# interfacez_r2_2.net
KiCad netlist of a schematic drawn in EAGLE
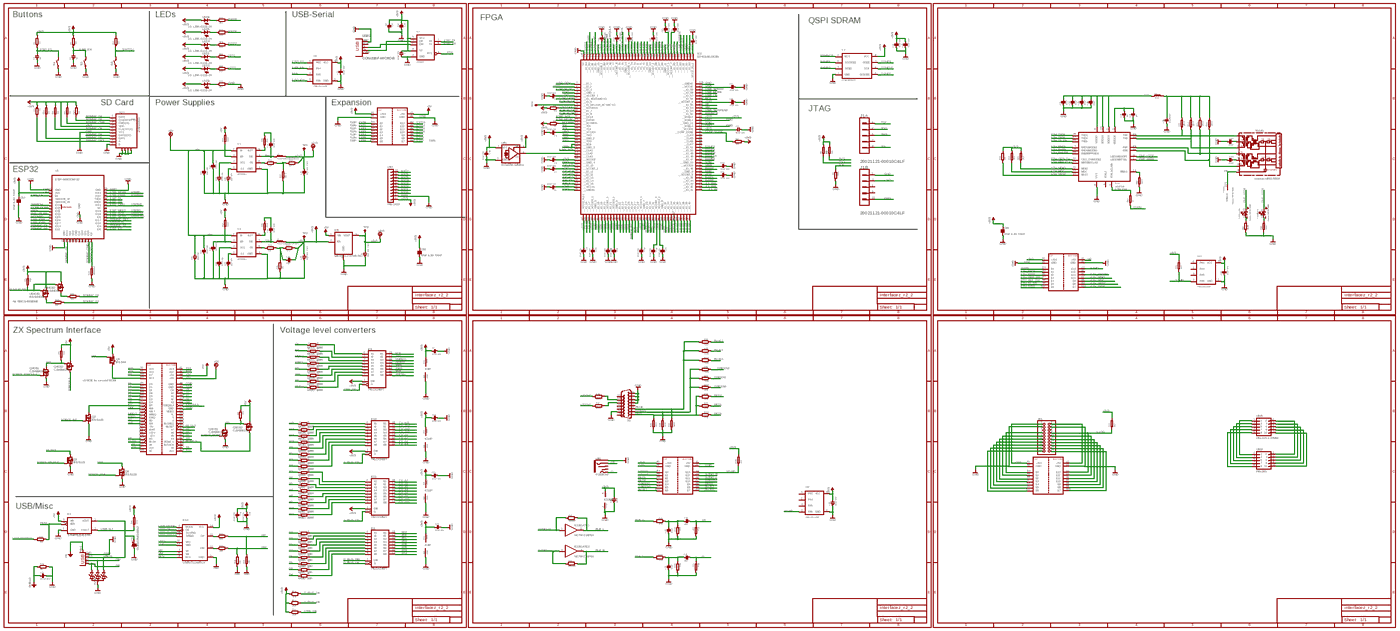
[diagram p0: schematic, sheet 1, overview]
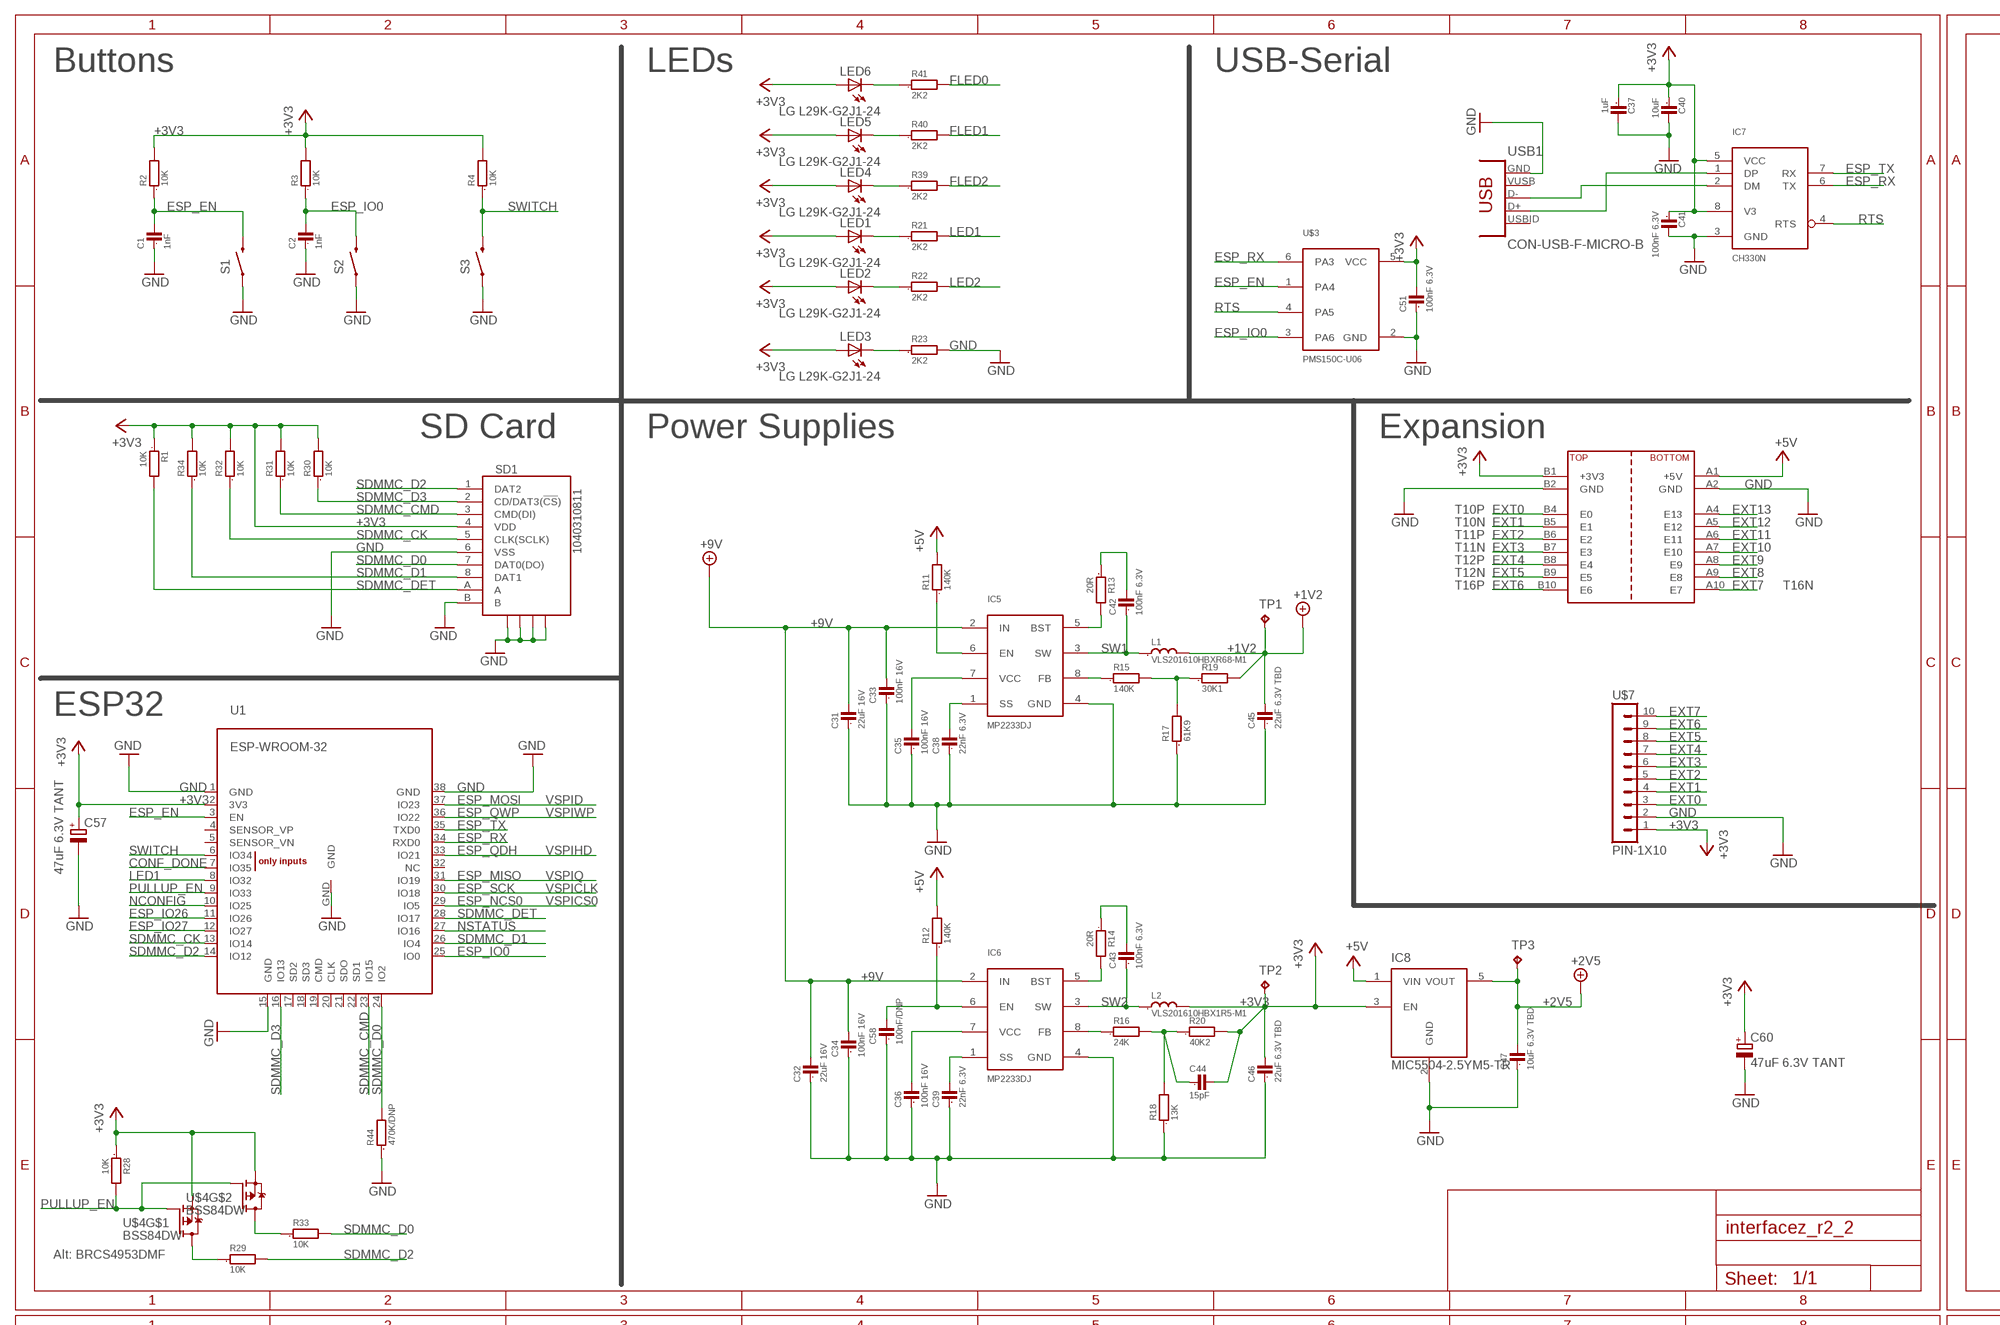
[diagram p1: schematic, sheet 1, part 1 of 8]
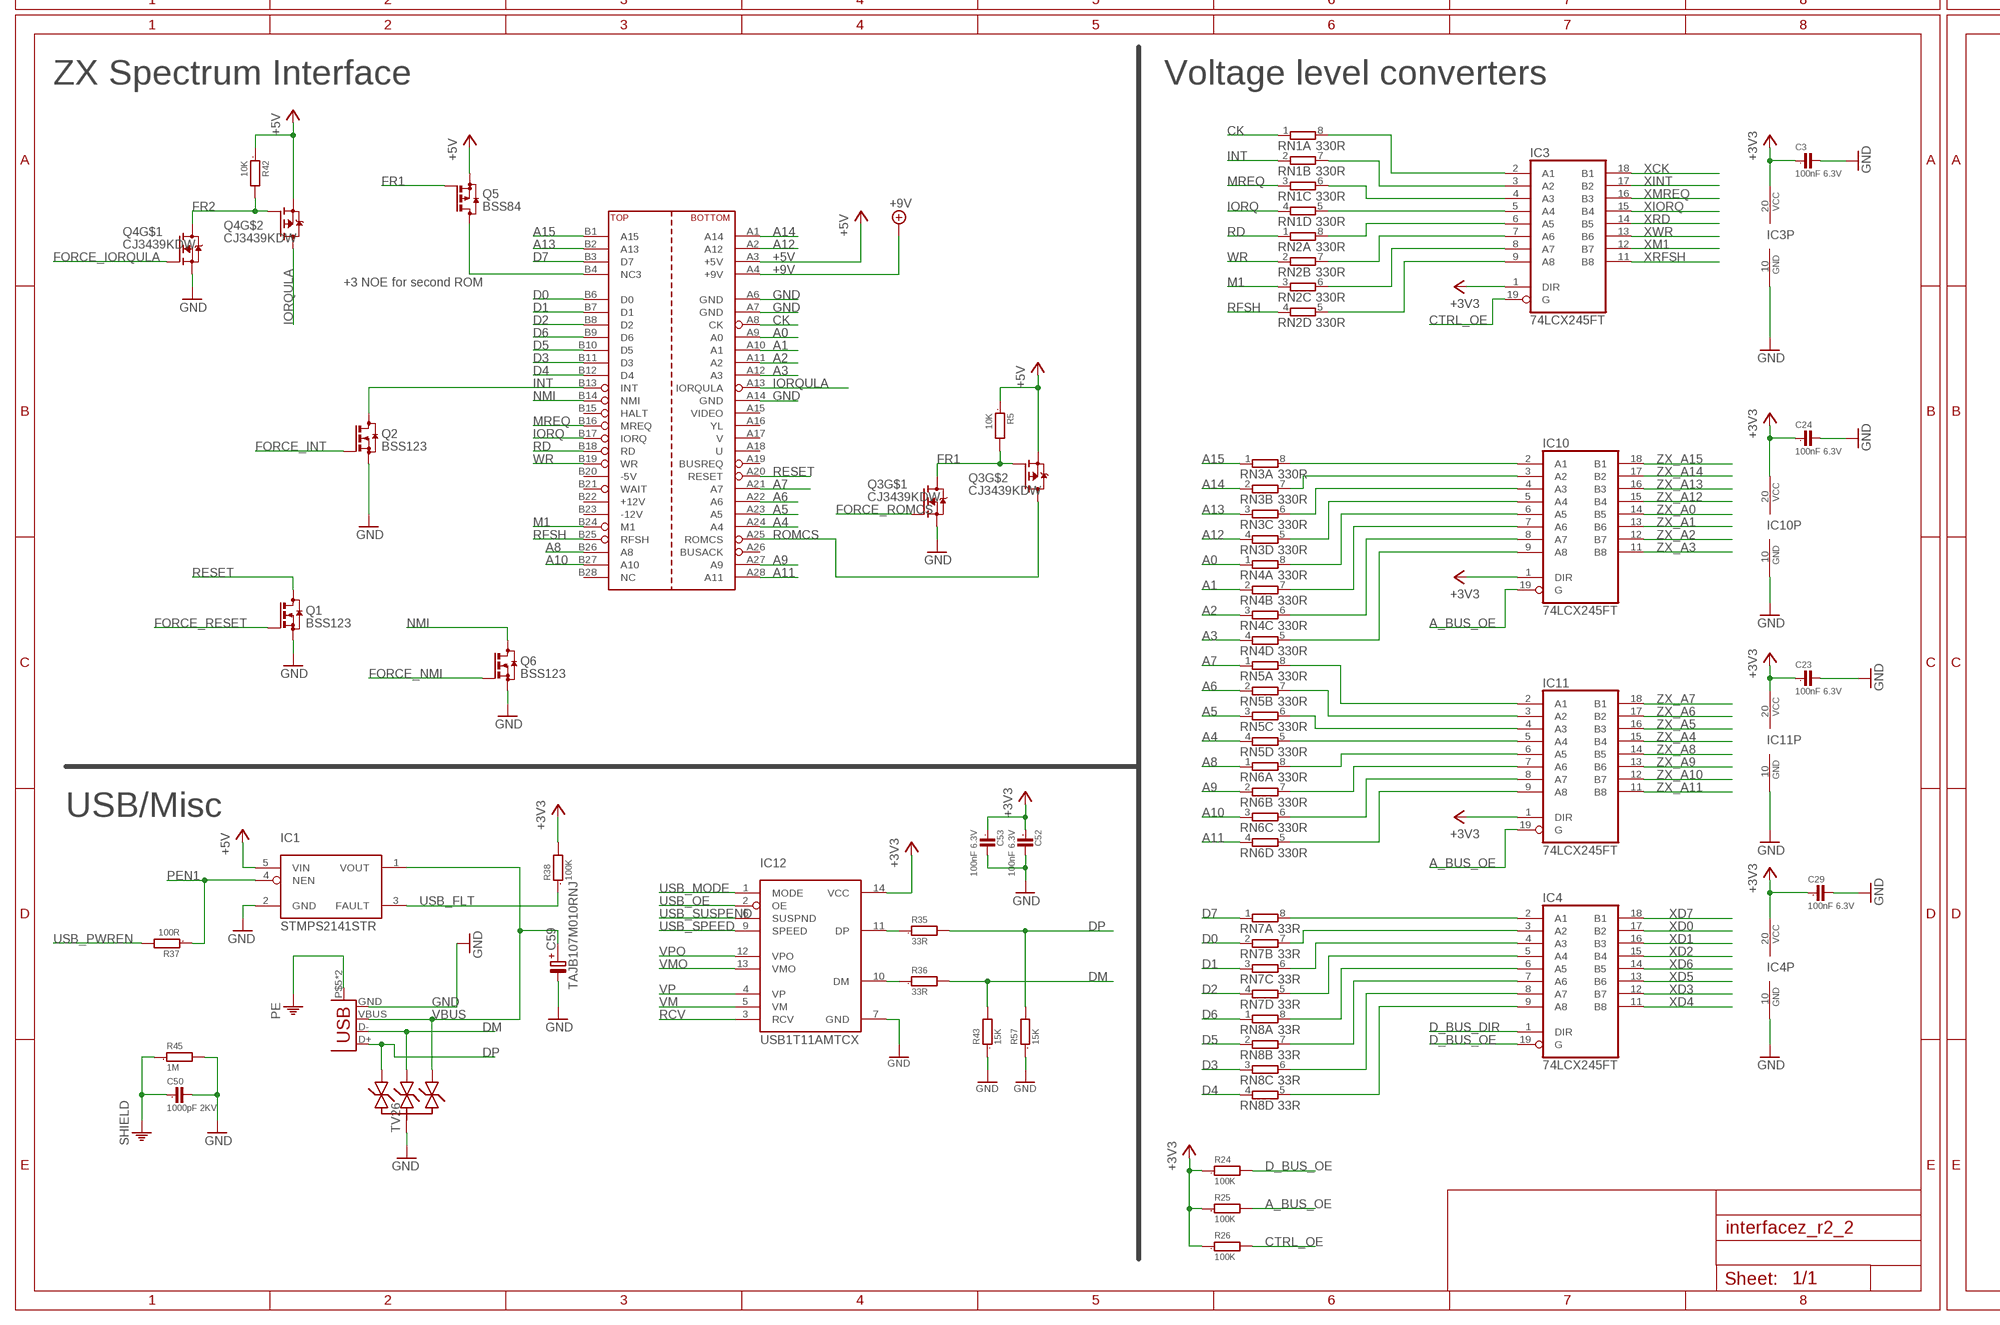
[diagram p2: schematic, sheet 1, part 2 of 8]
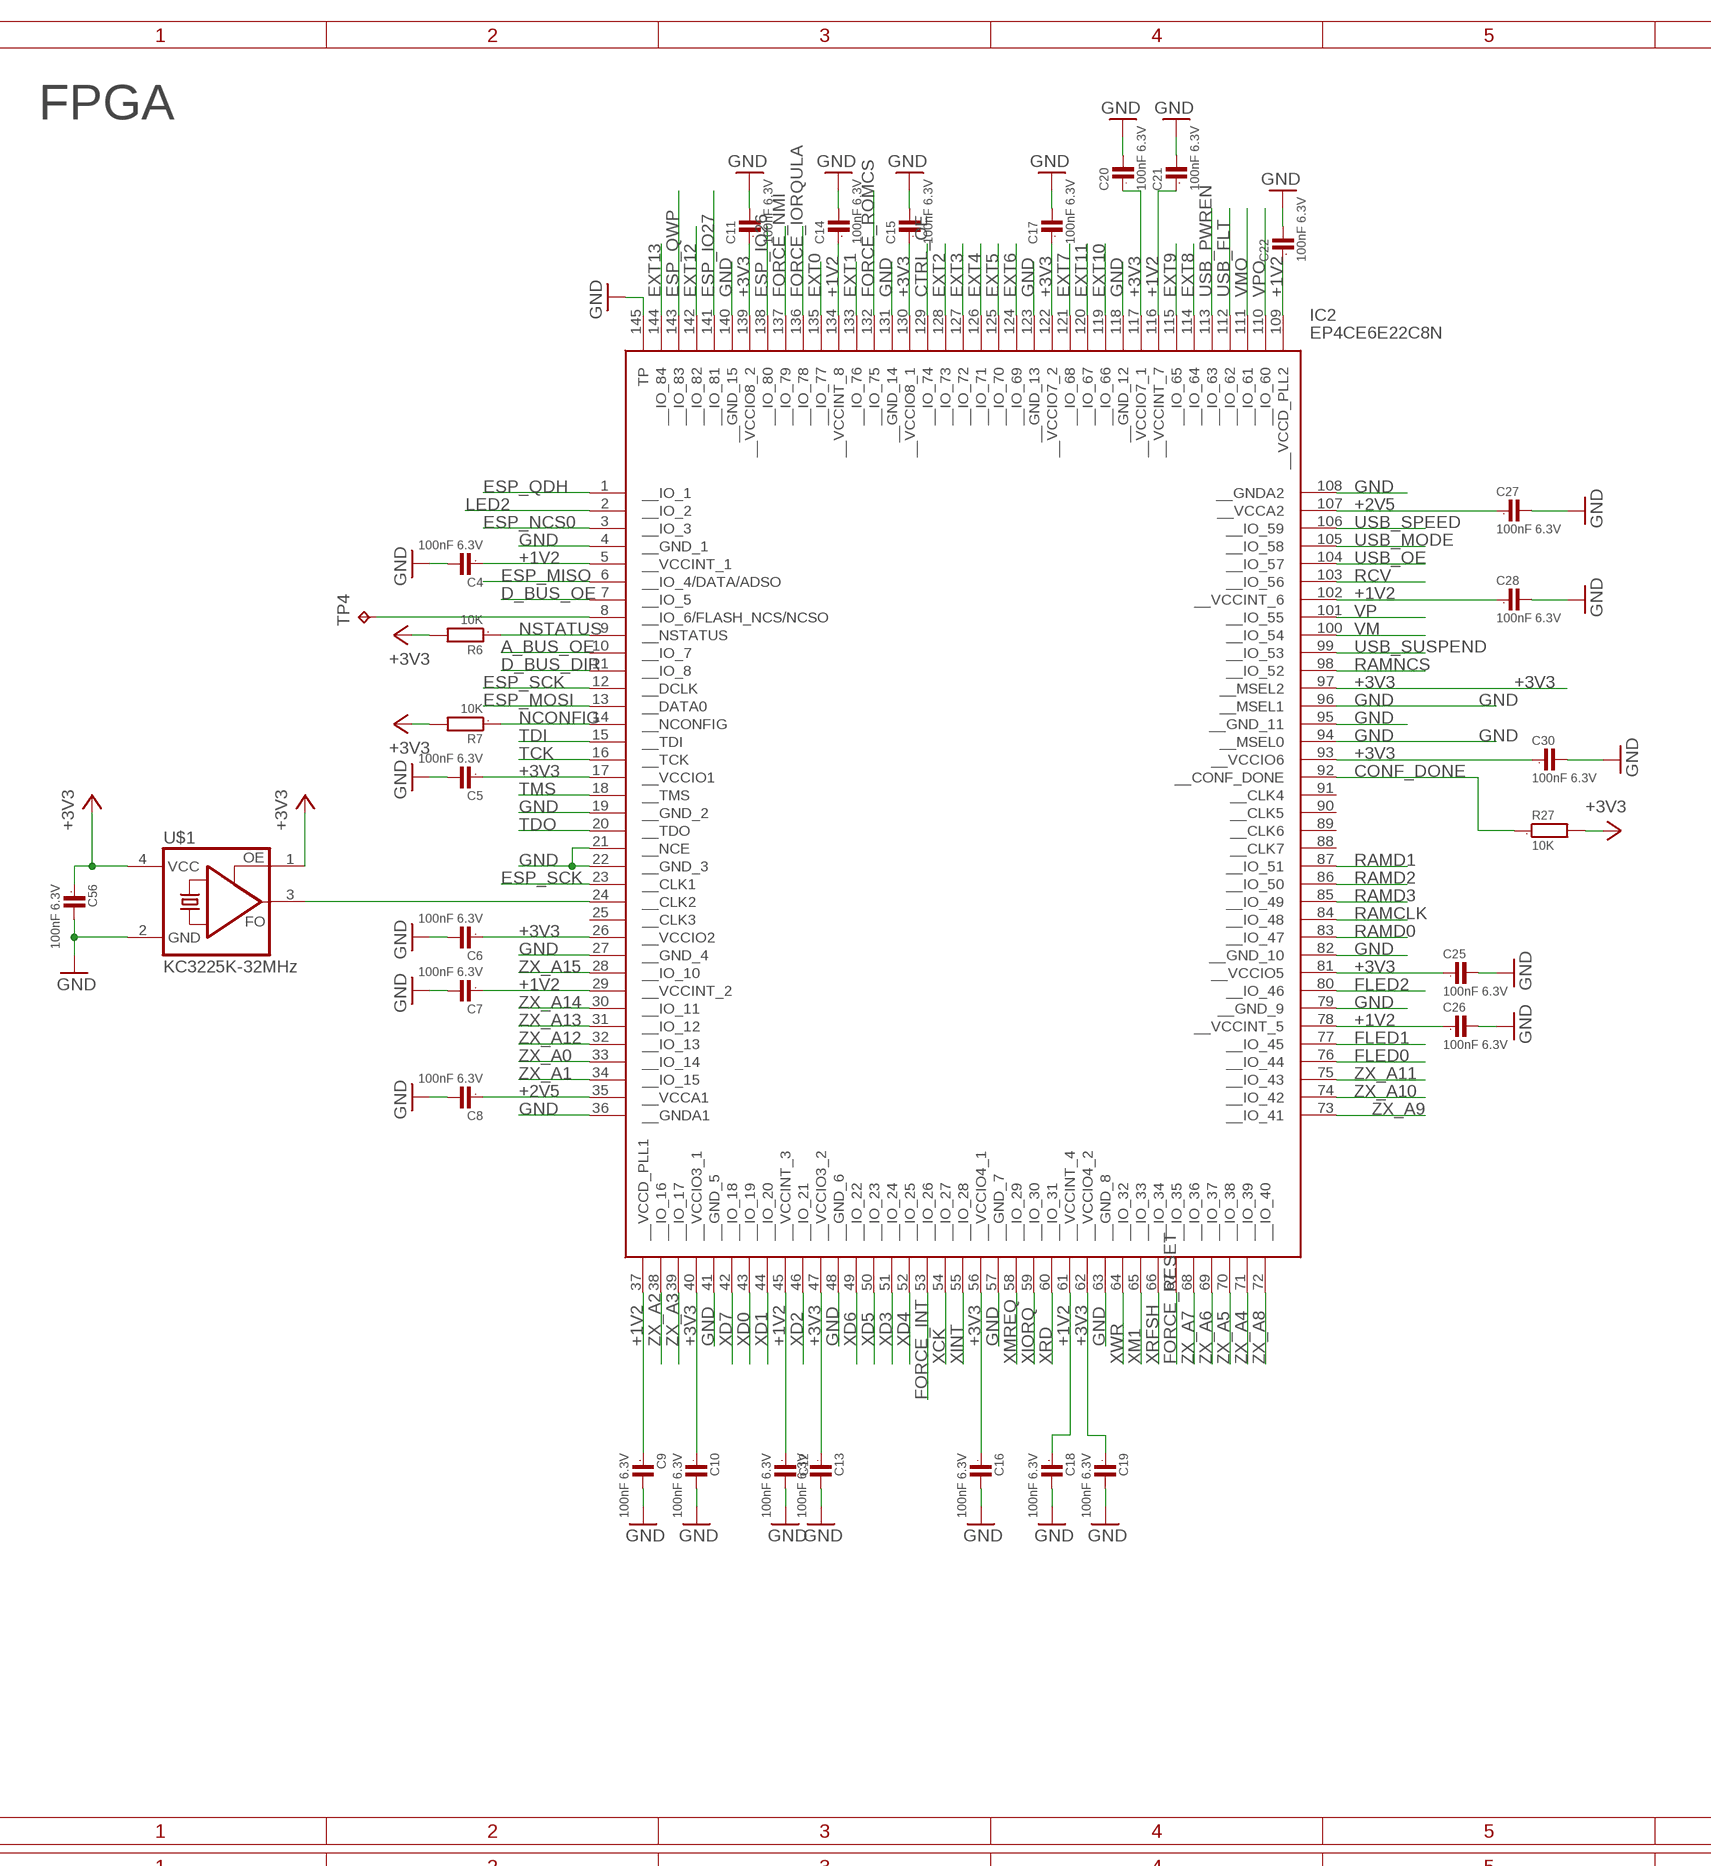
[diagram p3: schematic, sheet 1, part 3 of 8]
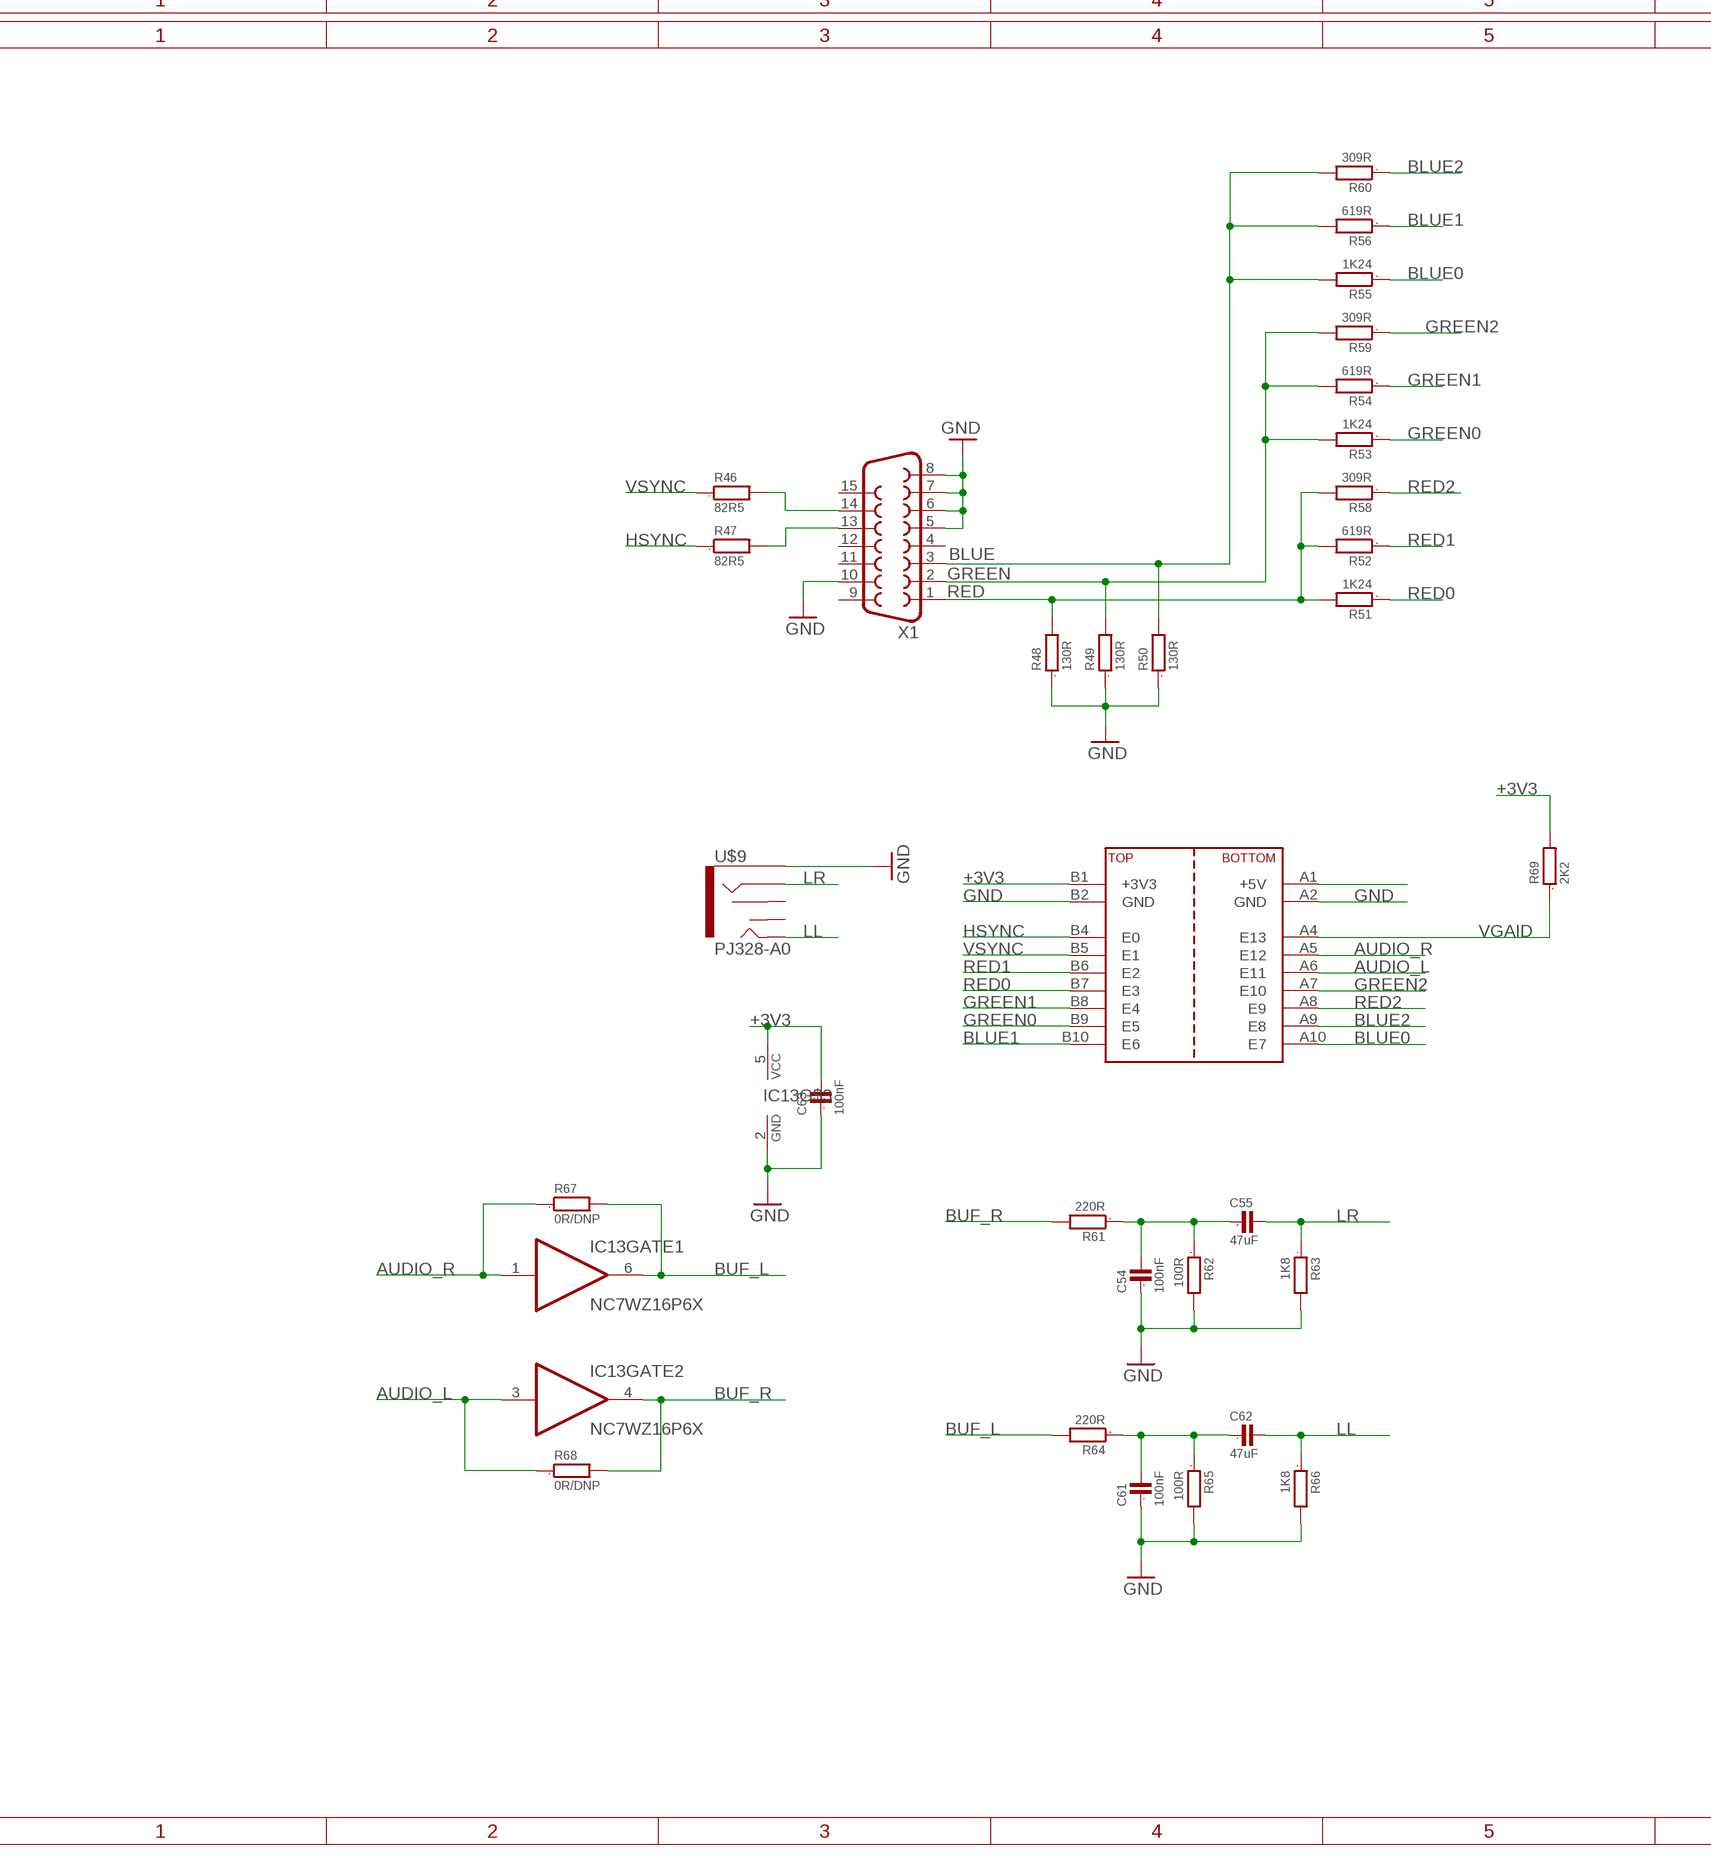
[diagram p4: schematic, sheet 1, part 4 of 8]
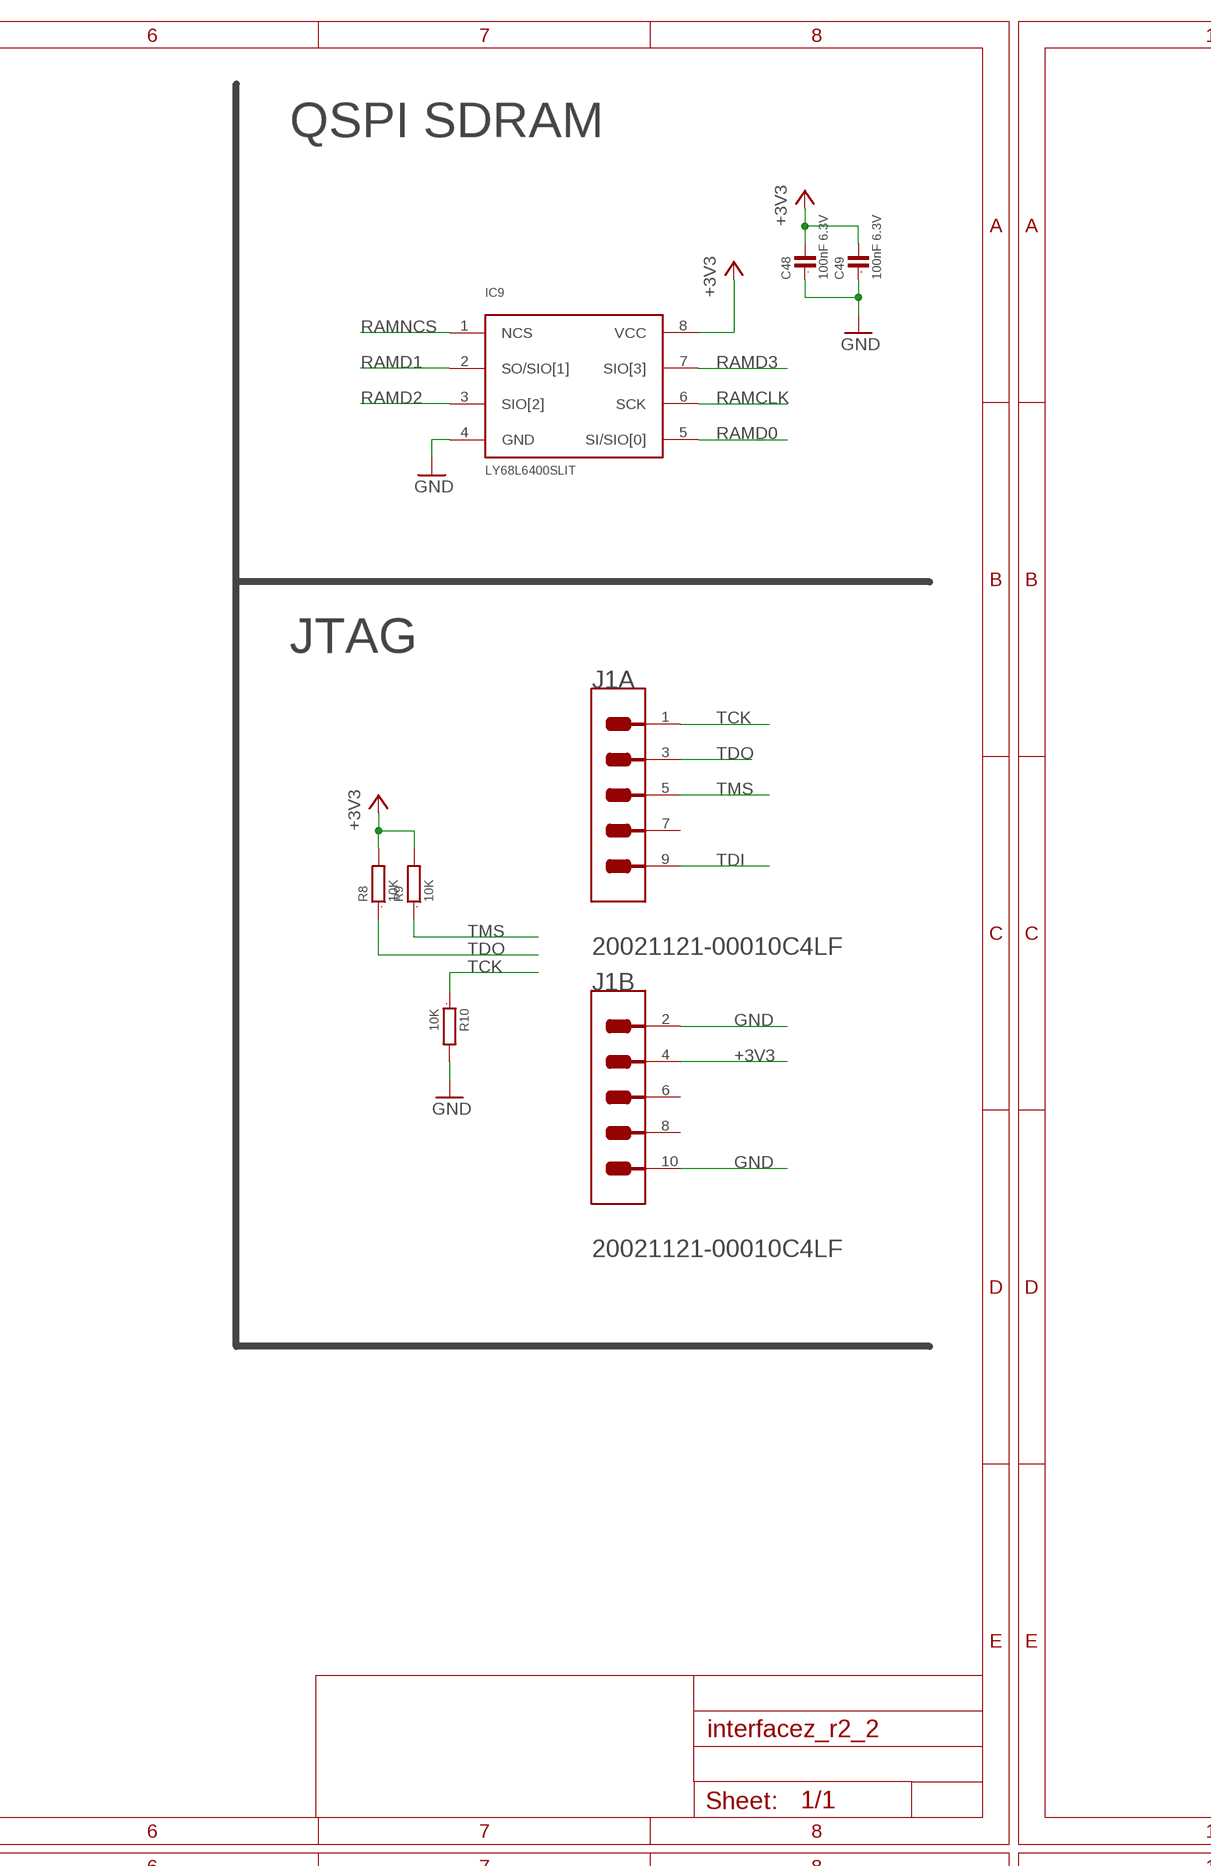
[diagram p5: schematic, sheet 1, part 5 of 8]
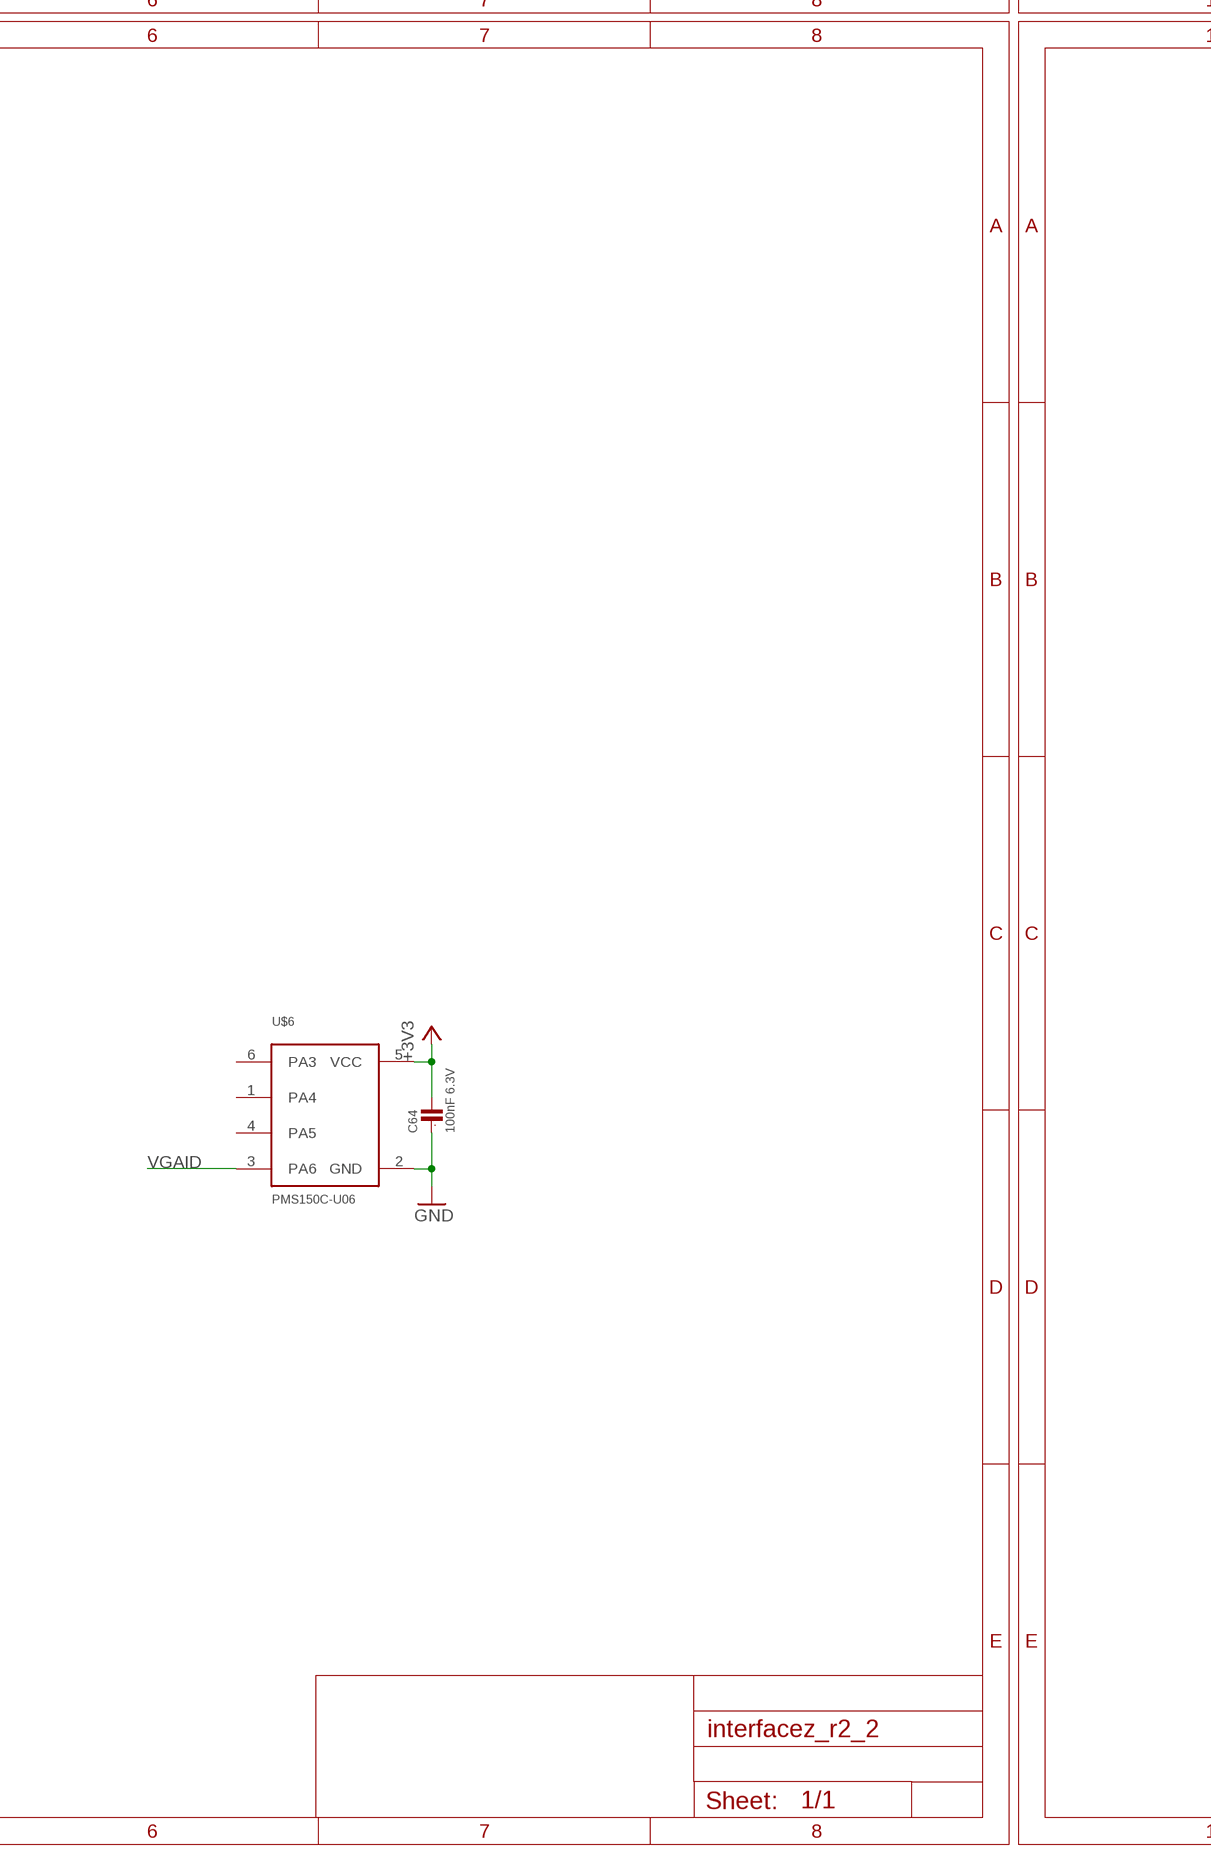
[diagram p6: schematic, sheet 1, part 6 of 8]
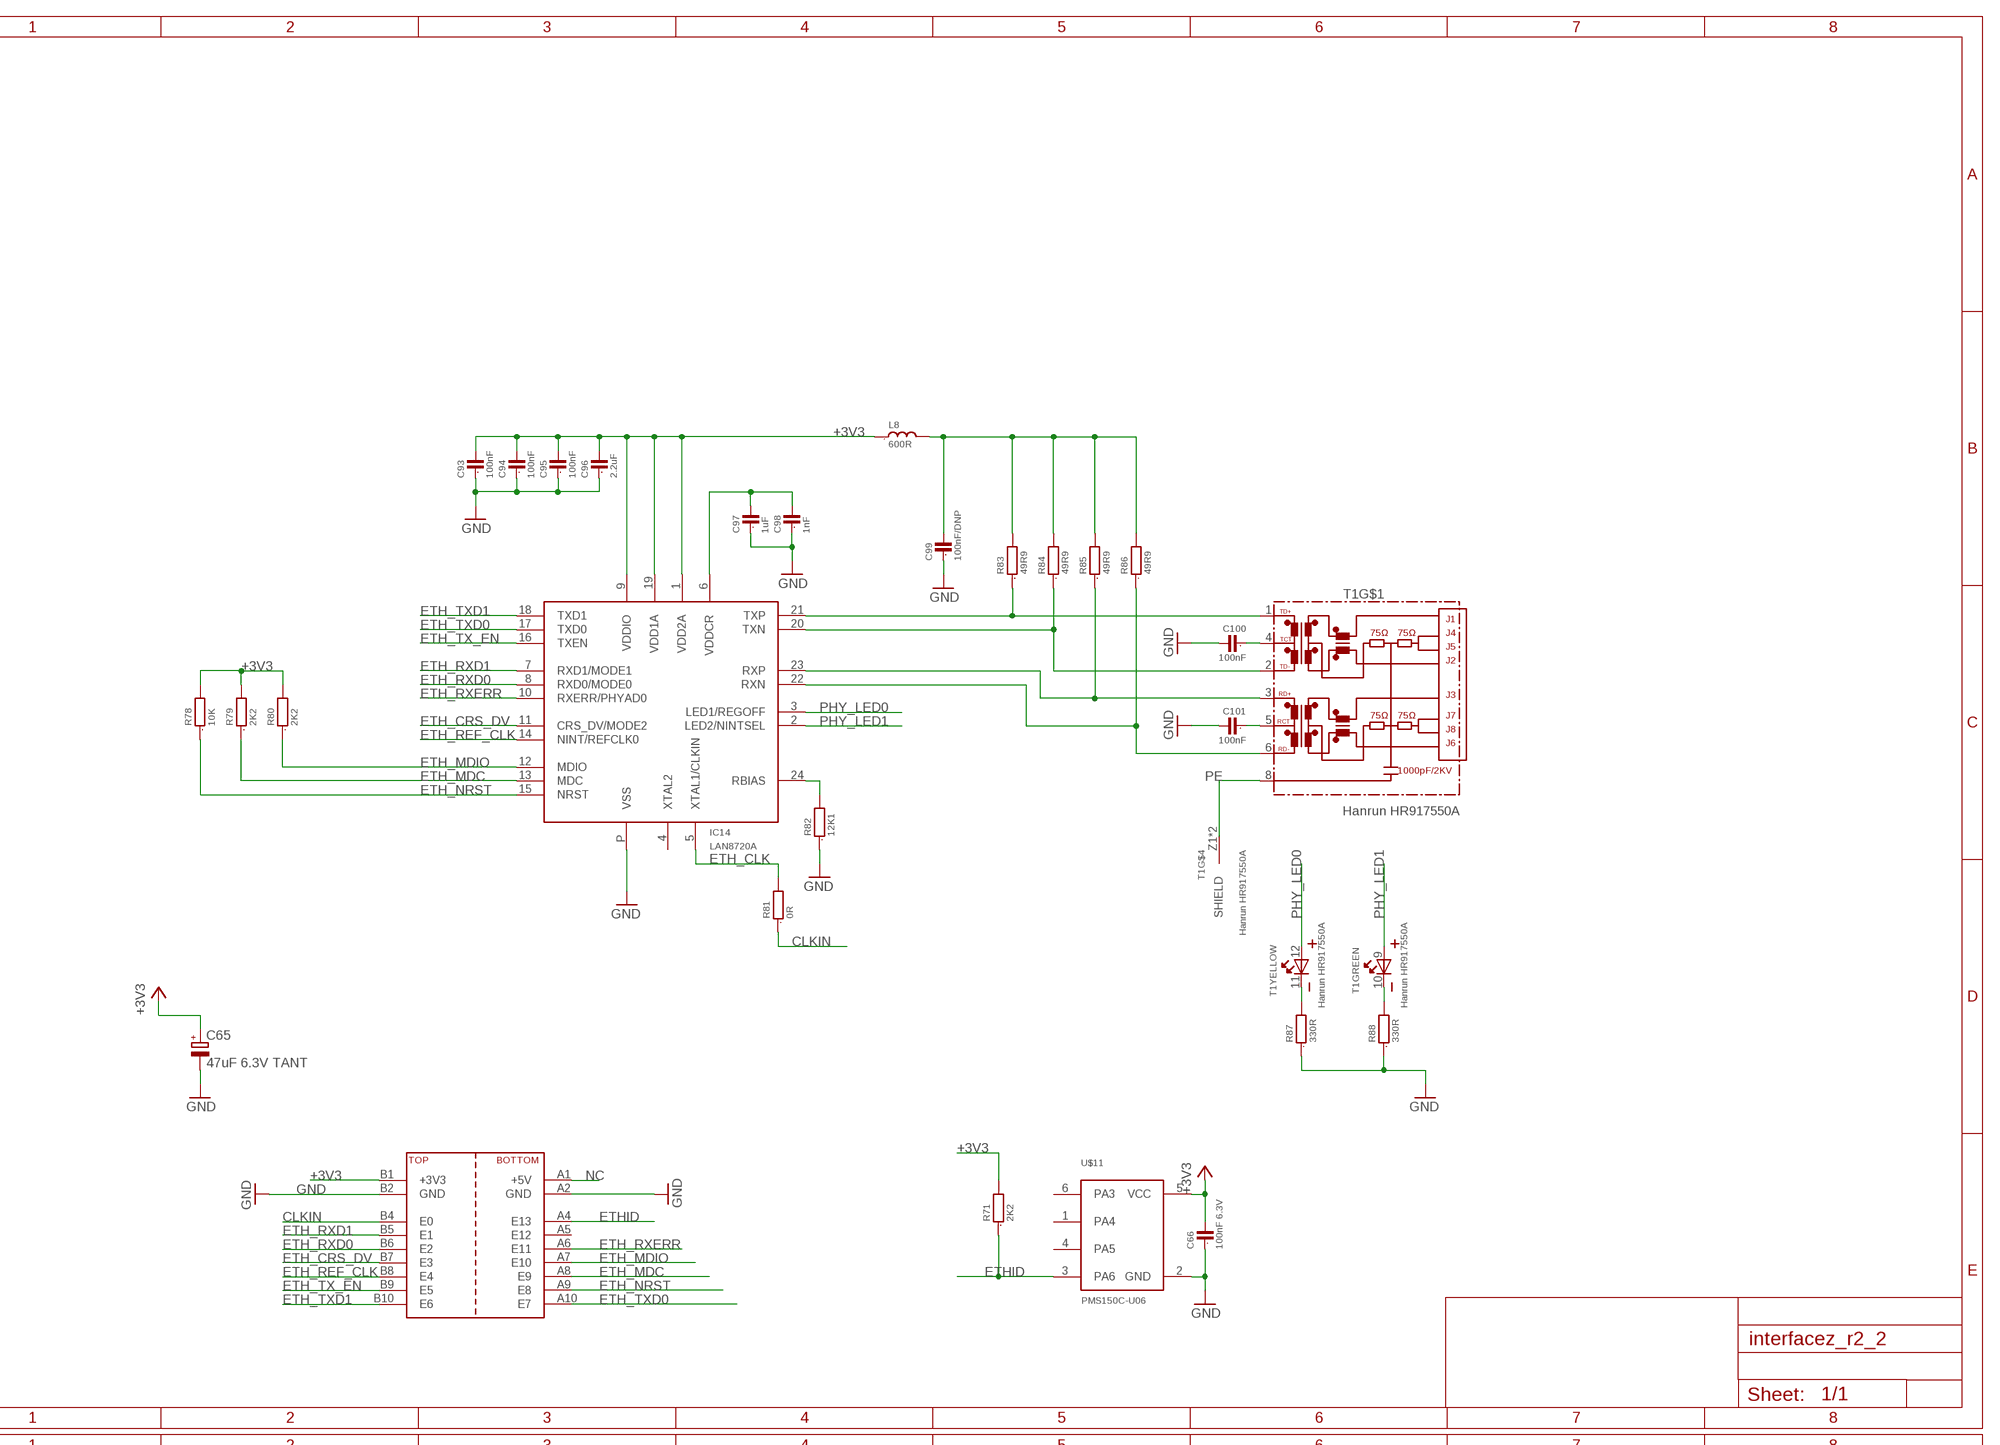
[diagram p7: schematic, sheet 1, part 7 of 8]
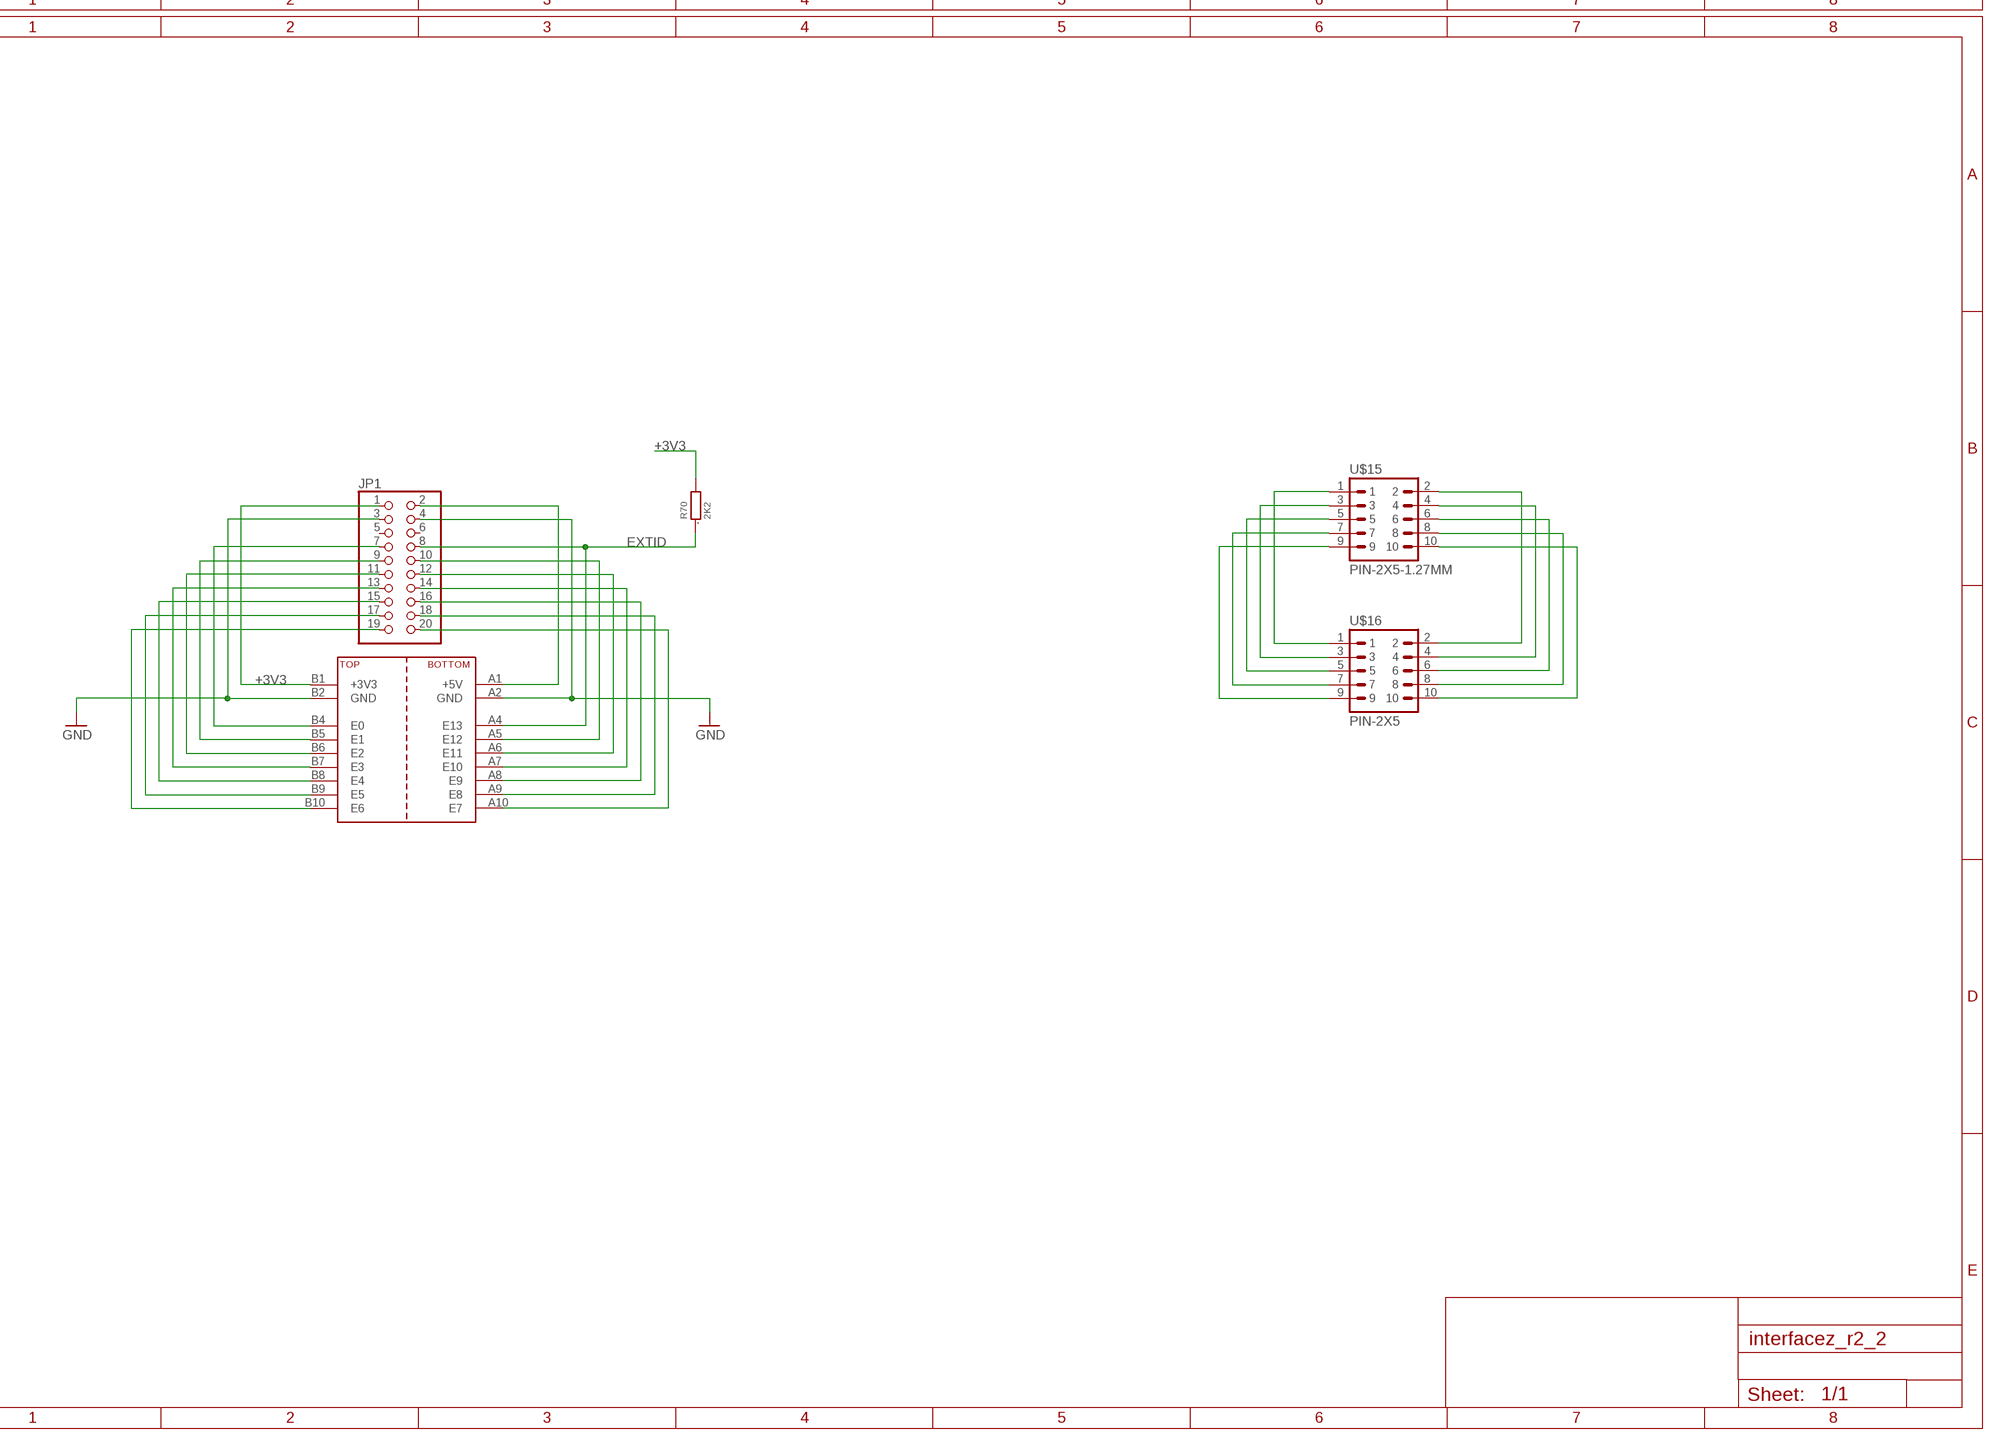
[diagram p8: schematic, sheet 1, part 8 of 8]

(export (version "E")
  (design (tool "Eeschema 10.0.6"))
  (components
    (comp (ref "C1")
      (value "1nF")
      (footprint "eagle-import:0603")
      (libsource (lib "eagle-import") (part "C0603"))
    )
    (comp (ref "C2")
      (value "1nF")
      (footprint "eagle-import:0603")
      (libsource (lib "eagle-import") (part "C0603"))
    )
    (comp (ref "C3")
      (value "100nF 6.3V")
      (footprint "eagle-import:0603")
      (libsource (lib "eagle-import") (part "C0603"))
    )
    (comp (ref "C4")
      (value "100nF 6.3V")
      (footprint "eagle-import:0603")
      (libsource (lib "eagle-import") (part "C0603"))
    )
    (comp (ref "C5")
      (value "100nF 6.3V")
      (footprint "eagle-import:0603")
      (libsource (lib "eagle-import") (part "C0603"))
    )
    (comp (ref "C6")
      (value "100nF 6.3V")
      (footprint "eagle-import:0603")
      (libsource (lib "eagle-import") (part "C0603"))
    )
    (comp (ref "C7")
      (value "100nF 6.3V")
      (footprint "eagle-import:0603")
      (libsource (lib "eagle-import") (part "C0603"))
    )
    (comp (ref "C8")
      (value "100nF 6.3V")
      (footprint "eagle-import:0603")
      (libsource (lib "eagle-import") (part "C0603"))
    )
    (comp (ref "C9")
      (value "100nF 6.3V")
      (footprint "eagle-import:0603")
      (libsource (lib "eagle-import") (part "C0603"))
    )
    (comp (ref "C10")
      (value "100nF 6.3V")
      (footprint "eagle-import:0603")
      (libsource (lib "eagle-import") (part "C0603"))
    )
    (comp (ref "C11")
      (value "100nF 6.3V")
      (footprint "eagle-import:0603")
      (libsource (lib "eagle-import") (part "C0603"))
    )
    (comp (ref "C12")
      (value "100nF 6.3V")
      (footprint "eagle-import:0603")
      (libsource (lib "eagle-import") (part "C0603"))
    )
    (comp (ref "C13")
      (value "100nF 6.3V")
      (footprint "eagle-import:0603")
      (libsource (lib "eagle-import") (part "C0603"))
    )
    (comp (ref "C14")
      (value "100nF 6.3V")
      (footprint "eagle-import:0603")
      (libsource (lib "eagle-import") (part "C0603"))
    )
    (comp (ref "C15")
      (value "100nF 6.3V")
      (footprint "eagle-import:0603")
      (libsource (lib "eagle-import") (part "C0603"))
    )
    (comp (ref "C16")
      (value "100nF 6.3V")
      (footprint "eagle-import:0603")
      (libsource (lib "eagle-import") (part "C0603"))
    )
    (comp (ref "C17")
      (value "100nF 6.3V")
      (footprint "eagle-import:0603")
      (libsource (lib "eagle-import") (part "C0603"))
    )
    (comp (ref "C18")
      (value "100nF 6.3V")
      (footprint "eagle-import:0603")
      (libsource (lib "eagle-import") (part "C0603"))
    )
    (comp (ref "C19")
      (value "100nF 6.3V")
      (footprint "eagle-import:0603")
      (libsource (lib "eagle-import") (part "C0603"))
    )
    (comp (ref "C20")
      (value "100nF 6.3V")
      (footprint "eagle-import:0603")
      (libsource (lib "eagle-import") (part "C0603"))
    )
    (comp (ref "C21")
      (value "100nF 6.3V")
      (footprint "eagle-import:0603")
      (libsource (lib "eagle-import") (part "C0603"))
    )
    (comp (ref "C22")
      (value "100nF 6.3V")
      (footprint "eagle-import:0603")
      (libsource (lib "eagle-import") (part "C0603"))
    )
    (comp (ref "C23")
      (value "100nF 6.3V")
      (footprint "eagle-import:0603")
      (libsource (lib "eagle-import") (part "C0603"))
    )
    (comp (ref "C24")
      (value "100nF 6.3V")
      (footprint "eagle-import:0603")
      (libsource (lib "eagle-import") (part "C0603"))
    )
    (comp (ref "C25")
      (value "100nF 6.3V")
      (footprint "eagle-import:0603")
      (libsource (lib "eagle-import") (part "C0603"))
    )
    (comp (ref "C26")
      (value "100nF 6.3V")
      (footprint "eagle-import:0603")
      (libsource (lib "eagle-import") (part "C0603"))
    )
    (comp (ref "C27")
      (value "100nF 6.3V")
      (footprint "eagle-import:0603")
      (libsource (lib "eagle-import") (part "C0603"))
    )
    (comp (ref "C28")
      (value "100nF 6.3V")
      (footprint "eagle-import:0603")
      (libsource (lib "eagle-import") (part "C0603"))
    )
    (comp (ref "C29")
      (value "100nF 6.3V")
      (footprint "eagle-import:0603")
      (libsource (lib "eagle-import") (part "C0603"))
    )
    (comp (ref "C30")
      (value "100nF 6.3V")
      (footprint "eagle-import:0603")
      (libsource (lib "eagle-import") (part "C0603"))
    )
    (comp (ref "C31")
      (value "22uF 16V")
      (footprint "eagle-import:1210")
      (libsource (lib "eagle-import") (part "C1210"))
    )
    (comp (ref "C32")
      (value "22uF 16V")
      (footprint "eagle-import:1210")
      (libsource (lib "eagle-import") (part "C1210"))
    )
    (comp (ref "C33")
      (value "100nF 16V")
      (footprint "eagle-import:0603")
      (libsource (lib "eagle-import") (part "C0603"))
    )
    (comp (ref "C34")
      (value "100nF 16V")
      (footprint "eagle-import:0603")
      (libsource (lib "eagle-import") (part "C0603"))
    )
    (comp (ref "C35")
      (value "100nF 16V")
      (footprint "eagle-import:0603")
      (libsource (lib "eagle-import") (part "C0603"))
    )
    (comp (ref "C36")
      (value "100nF 16V")
      (footprint "eagle-import:0603")
      (libsource (lib "eagle-import") (part "C0603"))
    )
    (comp (ref "C37")
      (value "1uF")
      (footprint "eagle-import:0603")
      (libsource (lib "eagle-import") (part "C0603"))
    )
    (comp (ref "C38")
      (value "22nF 6.3V")
      (footprint "eagle-import:0603")
      (libsource (lib "eagle-import") (part "C0603"))
    )
    (comp (ref "C39")
      (value "22nF 6.3V")
      (footprint "eagle-import:0603")
      (libsource (lib "eagle-import") (part "C0603"))
    )
    (comp (ref "C40")
      (value "10uF")
      (footprint "eagle-import:0603")
      (libsource (lib "eagle-import") (part "C0603"))
    )
    (comp (ref "C41")
      (value "100nF 6.3V")
      (footprint "eagle-import:0603")
      (libsource (lib "eagle-import") (part "C0603"))
    )
    (comp (ref "C42")
      (value "100nF 6.3V")
      (footprint "eagle-import:0603")
      (libsource (lib "eagle-import") (part "C0603"))
    )
    (comp (ref "C43")
      (value "100nF 6.3V")
      (footprint "eagle-import:0603")
      (libsource (lib "eagle-import") (part "C0603"))
    )
    (comp (ref "C44")
      (value "15pF")
      (footprint "eagle-import:0603")
      (libsource (lib "eagle-import") (part "C0603"))
    )
    (comp (ref "C45")
      (value "22uF 6.3V TBD")
      (footprint "eagle-import:0805")
      (libsource (lib "eagle-import") (part "C0805"))
    )
    (comp (ref "C46")
      (value "22uF 6.3V TBD")
      (footprint "eagle-import:0805")
      (libsource (lib "eagle-import") (part "C0805"))
    )
    (comp (ref "C47")
      (value "10uF 6.3V TBD")
      (footprint "eagle-import:0805")
      (libsource (lib "eagle-import") (part "C0805"))
    )
    (comp (ref "C48")
      (value "100nF 6.3V")
      (footprint "eagle-import:0603")
      (libsource (lib "eagle-import") (part "C0603"))
    )
    (comp (ref "C49")
      (value "100nF 6.3V")
      (footprint "eagle-import:0603")
      (libsource (lib "eagle-import") (part "C0603"))
    )
    (comp (ref "C50")
      (value "1000pF 2KV")
      (footprint "eagle-import:1210")
      (libsource (lib "eagle-import") (part "C1210"))
    )
    (comp (ref "C51")
      (value "100nF 6.3V")
      (footprint "eagle-import:0603")
      (libsource (lib "eagle-import") (part "C0603"))
    )
    (comp (ref "C52")
      (value "100nF 6.3V")
      (footprint "eagle-import:0603")
      (libsource (lib "eagle-import") (part "C0603"))
    )
    (comp (ref "C53")
      (value "100nF 6.3V")
      (footprint "eagle-import:0603")
      (libsource (lib "eagle-import") (part "C0603"))
    )
    (comp (ref "C54")
      (value "100nF")
      (footprint "eagle-import:0603")
      (libsource (lib "eagle-import") (part "C0603"))
    )
    (comp (ref "C55")
      (value "47uF")
      (footprint "eagle-import:1206")
      (libsource (lib "eagle-import") (part "C1206"))
    )
    (comp (ref "C56")
      (value "100nF 6.3V")
      (footprint "eagle-import:0603")
      (libsource (lib "eagle-import") (part "C0603"))
    )
    (comp (ref "C57")
      (value "47uF 6.3V TANT")
      (footprint "eagle-import:TANT_CASE_A")
      (libsource (lib "eagle-import") (part "TANT_CASE_A"))
    )
    (comp (ref "C58")
      (value "100nF/DNP")
      (footprint "eagle-import:0603")
      (libsource (lib "eagle-import") (part "C0603"))
    )
    (comp (ref "C59")
      (value "TAJB107M010RNJ")
      (footprint "eagle-import:TE-B-3528")
      (libsource (lib "eagle-import") (part "C-PR-SMD-TE-B"))
    )
    (comp (ref "C60")
      (value "47uF 6.3V TANT")
      (footprint "eagle-import:TANT_CASE_A")
      (libsource (lib "eagle-import") (part "TANT_CASE_A"))
    )
    (comp (ref "C61")
      (value "100nF")
      (footprint "eagle-import:0603")
      (libsource (lib "eagle-import") (part "C0603"))
    )
    (comp (ref "C62")
      (value "47uF")
      (footprint "eagle-import:1206")
      (libsource (lib "eagle-import") (part "C1206"))
    )
    (comp (ref "C63")
      (value "100nF")
      (footprint "eagle-import:0603")
      (libsource (lib "eagle-import") (part "C0603"))
    )
    (comp (ref "C64")
      (value "100nF 6.3V")
      (footprint "eagle-import:0603")
      (libsource (lib "eagle-import") (part "C0603"))
    )
    (comp (ref "C65")
      (value "47uF 6.3V TANT")
      (footprint "eagle-import:TANT_CASE_A")
      (libsource (lib "eagle-import") (part "TANT_CASE_A"))
    )
    (comp (ref "C66")
      (value "100nF 6.3V")
      (footprint "eagle-import:0603")
      (libsource (lib "eagle-import") (part "C0603"))
    )
    (comp (ref "C93")
      (value "100nF")
      (footprint "eagle-import:0603")
      (libsource (lib "eagle-import") (part "C0603"))
    )
    (comp (ref "C94")
      (value "100nF")
      (footprint "eagle-import:0603")
      (libsource (lib "eagle-import") (part "C0603"))
    )
    (comp (ref "C95")
      (value "100nF")
      (footprint "eagle-import:0603")
      (libsource (lib "eagle-import") (part "C0603"))
    )
    (comp (ref "C96")
      (value "2.2uF")
      (footprint "eagle-import:0805")
      (libsource (lib "eagle-import") (part "C0805"))
    )
    (comp (ref "C97")
      (value "1uF")
      (footprint "eagle-import:0603")
      (libsource (lib "eagle-import") (part "C0603"))
    )
    (comp (ref "C98")
      (value "1nF")
      (footprint "eagle-import:0603")
      (libsource (lib "eagle-import") (part "C0603"))
    )
    (comp (ref "C99")
      (value "100nF/DNP")
      (footprint "eagle-import:0603")
      (libsource (lib "eagle-import") (part "C0603"))
    )
    (comp (ref "C100")
      (value "100nF")
      (footprint "eagle-import:0603")
      (libsource (lib "eagle-import") (part "C0603"))
    )
    (comp (ref "C101")
      (value "100nF")
      (footprint "eagle-import:0603")
      (libsource (lib "eagle-import") (part "C0603"))
    )
    (comp (ref "CONN1")
      (value "ZX_EDGE_DAUGHTERBOARD")
      (footprint "eagle-import:ZX-EDGE-DAUGHTERBOARD")
      (libsource (lib "eagle-import") (part "ZX_EDGE_DAUGHTERBOARD"))
    )
    (comp (ref "IC1")
      (value "STMPS2141STR")
      (footprint "eagle-import:SOT23-5L")
      (libsource (lib "eagle-import") (part "STMPS2141STR"))
    )
    (comp (ref "IC2")
      (value "EP4CE6E22C8N")
      (footprint "eagle-import:QFP50P2200X2200X165-145N")
      (fields (field (name "MOUSER_PART_NUMBER") "989-EP4CE6E22C8N"))
      (libsource (lib "eagle-import") (part "EP4CE6E22C8N"))
    )
    (comp (ref "IC3")
      (value "74LCX245FT")
      (footprint "eagle-import:TSSOP20")
      (libsource (lib "eagle-import") (part "74245"))
    )
    (comp (ref "IC4")
      (value "74LCX245FT")
      (footprint "eagle-import:TSSOP20")
      (libsource (lib "eagle-import") (part "74245"))
    )
    (comp (ref "IC5")
      (value "MP2233DJ")
      (footprint "eagle-import:SOT23-8L")
      (libsource (lib "eagle-import") (part "MP2233DJ"))
    )
    (comp (ref "IC6")
      (value "MP2233DJ")
      (footprint "eagle-import:SOT23-8L")
      (libsource (lib "eagle-import") (part "MP2233DJ"))
    )
    (comp (ref "IC7")
      (value "CH330N")
      (footprint "eagle-import:SOIC8")
      (libsource (lib "eagle-import") (part "CH330N"))
    )
    (comp (ref "IC8")
      (value "MIC5504-2.5YM5-TR")
      (footprint "eagle-import:SOT23-5L")
      (libsource (lib "eagle-import") (part "MIC550X"))
    )
    (comp (ref "IC9")
      (value "LY68L6400SLIT")
      (footprint "eagle-import:SOIC8")
      (libsource (lib "eagle-import") (part "LY68L6400SLIT"))
    )
    (comp (ref "IC10")
      (value "74LCX245FT")
      (footprint "eagle-import:TSSOP20")
      (libsource (lib "eagle-import") (part "74245"))
    )
    (comp (ref "IC11")
      (value "74LCX245FT")
      (footprint "eagle-import:TSSOP20")
      (libsource (lib "eagle-import") (part "74245"))
    )
    (comp (ref "IC12")
      (value "USB1T11AMTCX")
      (footprint "eagle-import:TSSOP14")
      (libsource (lib "eagle-import") (part "USB1TMTCX11A"))
    )
    (comp (ref "IC13")
      (value "NC7WZ16P6X")
      (footprint "eagle-import:SC70-6")
      (libsource (lib "eagle-import") (part "NC7WZ07P6X"))
    )
    (comp (ref "IC14")
      (value "LAN8720A")
      (footprint "eagle-import:QFN24_4MM_X_4MM")
      (libsource (lib "eagle-import") (part "LAN8720A"))
    )
    (comp (ref "J1")
      (value "AMPHENOL_ICC_-_FCI_20021121-00010C4LFAMPHENOL_ICC_-_FCI_20021121-00010C4LF_0_0")
      (footprint "eagle-import:AMPHENOL_ICC_-_FCI_20021121-00010C4LF_0")
      (fields
        (field (name "DIGIKEY_PART_NUMBER") "609-3695-1-ND")
        (field (name "MF") "Amphenol ICC / FCI")
        (field (name "MOUSER_PART_NUMBER") "649-202112100010C4LF")
      )
      (libsource (lib "eagle-import") (part "AMPHENOL_ICC_-_FCI_20021121-00010C4LFAMPHENOL_ICC_-_FCI_20021121-00010C4LF_0_0"))
    )
    (comp (ref "JP1")
      (value "PINHD-2X10")
      (footprint "eagle-import:2X10")
      (libsource (lib "eagle-import") (part "PINHD-2X10"))
    )
    (comp (ref "L1")
      (value "VLS201610HBXR68-M1")
      (footprint "eagle-import:IND_0806")
      (libsource (lib "eagle-import") (part "VLS201610HBXR68-M1"))
    )
    (comp (ref "L2")
      (value "VLS201610HBX1R5-M1")
      (footprint "eagle-import:IND_0806")
      (libsource (lib "eagle-import") (part "VLS201610HBX1R5-M1"))
    )
    (comp (ref "L8")
      (value "600R")
      (footprint "eagle-import:0805")
      (libsource (lib "eagle-import") (part "L0805"))
    )
    (comp (ref "LED1")
      (value "LG L29K-G2J1-24")
      (footprint "eagle-import:LED-603")
      (libsource (lib "eagle-import") (part "LED-0603"))
    )
    (comp (ref "LED2")
      (value "LG L29K-G2J1-24")
      (footprint "eagle-import:LED-603")
      (libsource (lib "eagle-import") (part "LED-0603"))
    )
    (comp (ref "LED3")
      (value "LG L29K-G2J1-24")
      (footprint "eagle-import:LED-603")
      (libsource (lib "eagle-import") (part "LED-0603"))
    )
    (comp (ref "LED4")
      (value "LG L29K-G2J1-24")
      (footprint "eagle-import:LED-603")
      (libsource (lib "eagle-import") (part "LED-0603"))
    )
    (comp (ref "LED5")
      (value "LG L29K-G2J1-24")
      (footprint "eagle-import:LED-603")
      (libsource (lib "eagle-import") (part "LED-0603"))
    )
    (comp (ref "LED6")
      (value "LG L29K-G2J1-24")
      (footprint "eagle-import:LED-603")
      (libsource (lib "eagle-import") (part "LED-0603"))
    )
    (comp (ref "Q1")
      (value "BSS123")
      (footprint "eagle-import:SOT23")
      (libsource (lib "eagle-import") (part "BSS123"))
    )
    (comp (ref "Q2")
      (value "BSS123")
      (footprint "eagle-import:SOT23")
      (libsource (lib "eagle-import") (part "BSS123"))
    )
    (comp (ref "Q3")
      (value "CJ3439KDW")
      (footprint "eagle-import:SC70-6")
      (libsource (lib "eagle-import") (part "CJ3439KDW"))
    )
    (comp (ref "Q4")
      (value "CJ3439KDW")
      (footprint "eagle-import:SC70-6")
      (libsource (lib "eagle-import") (part "CJ3439KDW"))
    )
    (comp (ref "Q5")
      (value "BSS84")
      (footprint "eagle-import:SOT23")
      (libsource (lib "eagle-import") (part "BSS84"))
    )
    (comp (ref "Q6")
      (value "BSS123")
      (footprint "eagle-import:SOT23")
      (libsource (lib "eagle-import") (part "BSS123"))
    )
    (comp (ref "R1")
      (value "10K")
      (footprint "eagle-import:0603")
      (libsource (lib "eagle-import") (part "R0603"))
    )
    (comp (ref "R2")
      (value "10K")
      (footprint "eagle-import:0603")
      (libsource (lib "eagle-import") (part "R0603"))
    )
    (comp (ref "R3")
      (value "10K")
      (footprint "eagle-import:0603")
      (libsource (lib "eagle-import") (part "R0603"))
    )
    (comp (ref "R4")
      (value "10K")
      (footprint "eagle-import:0603")
      (libsource (lib "eagle-import") (part "R0603"))
    )
    (comp (ref "R5")
      (value "10K")
      (footprint "eagle-import:0603")
      (libsource (lib "eagle-import") (part "R0603"))
    )
    (comp (ref "R6")
      (value "10K")
      (footprint "eagle-import:0603")
      (libsource (lib "eagle-import") (part "R0603"))
    )
    (comp (ref "R7")
      (value "10K")
      (footprint "eagle-import:0603")
      (libsource (lib "eagle-import") (part "R0603"))
    )
    (comp (ref "R8")
      (value "10K")
      (footprint "eagle-import:0603")
      (libsource (lib "eagle-import") (part "R0603"))
    )
    (comp (ref "R9")
      (value "10K")
      (footprint "eagle-import:0603")
      (libsource (lib "eagle-import") (part "R0603"))
    )
    (comp (ref "R10")
      (value "10K")
      (footprint "eagle-import:0603")
      (libsource (lib "eagle-import") (part "R0603"))
    )
    (comp (ref "R11")
      (value "140K")
      (footprint "eagle-import:0603")
      (libsource (lib "eagle-import") (part "R0603"))
    )
    (comp (ref "R12")
      (value "140K")
      (footprint "eagle-import:0603")
      (libsource (lib "eagle-import") (part "R0603"))
    )
    (comp (ref "R13")
      (value "20R")
      (footprint "eagle-import:0603")
      (libsource (lib "eagle-import") (part "R0603"))
    )
    (comp (ref "R14")
      (value "20R")
      (footprint "eagle-import:0603")
      (libsource (lib "eagle-import") (part "R0603"))
    )
    (comp (ref "R15")
      (value "140K")
      (footprint "eagle-import:0603")
      (libsource (lib "eagle-import") (part "R0603"))
    )
    (comp (ref "R16")
      (value "24K")
      (footprint "eagle-import:0603")
      (libsource (lib "eagle-import") (part "R0603"))
    )
    (comp (ref "R17")
      (value "61K9")
      (footprint "eagle-import:0603")
      (libsource (lib "eagle-import") (part "R0603"))
    )
    (comp (ref "R18")
      (value "13K")
      (footprint "eagle-import:0603")
      (libsource (lib "eagle-import") (part "R0603"))
    )
    (comp (ref "R19")
      (value "30K1")
      (footprint "eagle-import:0603")
      (libsource (lib "eagle-import") (part "R0603"))
    )
    (comp (ref "R20")
      (value "40K2")
      (footprint "eagle-import:0603")
      (libsource (lib "eagle-import") (part "R0603"))
    )
    (comp (ref "R21")
      (value "2K2")
      (footprint "eagle-import:0603")
      (libsource (lib "eagle-import") (part "R0603"))
    )
    (comp (ref "R22")
      (value "2K2")
      (footprint "eagle-import:0603")
      (libsource (lib "eagle-import") (part "R0603"))
    )
    (comp (ref "R23")
      (value "2K2")
      (footprint "eagle-import:0603")
      (libsource (lib "eagle-import") (part "R0603"))
    )
    (comp (ref "R24")
      (value "100K")
      (footprint "eagle-import:0603")
      (libsource (lib "eagle-import") (part "R0603"))
    )
    (comp (ref "R25")
      (value "100K")
      (footprint "eagle-import:0603")
      (libsource (lib "eagle-import") (part "R0603"))
    )
    (comp (ref "R26")
      (value "100K")
      (footprint "eagle-import:0603")
      (libsource (lib "eagle-import") (part "R0603"))
    )
    (comp (ref "R27")
      (value "10K")
      (footprint "eagle-import:0603")
      (libsource (lib "eagle-import") (part "R0603"))
    )
    (comp (ref "R28")
      (value "10K")
      (footprint "eagle-import:0603")
      (libsource (lib "eagle-import") (part "R0603"))
    )
    (comp (ref "R29")
      (value "10K")
      (footprint "eagle-import:0603")
      (libsource (lib "eagle-import") (part "R0603"))
    )
    (comp (ref "R30")
      (value "10K")
      (footprint "eagle-import:0603")
      (libsource (lib "eagle-import") (part "R0603"))
    )
    (comp (ref "R31")
      (value "10K")
      (footprint "eagle-import:0603")
      (libsource (lib "eagle-import") (part "R0603"))
    )
    (comp (ref "R32")
      (value "10K")
      (footprint "eagle-import:0603")
      (libsource (lib "eagle-import") (part "R0603"))
    )
    (comp (ref "R33")
      (value "10K")
      (footprint "eagle-import:0603")
      (libsource (lib "eagle-import") (part "R0603"))
    )
    (comp (ref "R34")
      (value "10K")
      (footprint "eagle-import:0603")
      (libsource (lib "eagle-import") (part "R0603"))
    )
    (comp (ref "R35")
      (value "33R")
      (footprint "eagle-import:0603")
      (libsource (lib "eagle-import") (part "R0603"))
    )
    (comp (ref "R36")
      (value "33R")
      (footprint "eagle-import:0603")
      (libsource (lib "eagle-import") (part "R0603"))
    )
    (comp (ref "R37")
      (value "100R")
      (footprint "eagle-import:0603")
      (libsource (lib "eagle-import") (part "R0603"))
    )
    (comp (ref "R38")
      (value "100K")
      (footprint "eagle-import:0603")
      (libsource (lib "eagle-import") (part "R0603"))
    )
    (comp (ref "R39")
      (value "2K2")
      (footprint "eagle-import:0603")
      (libsource (lib "eagle-import") (part "R0603"))
    )
    (comp (ref "R40")
      (value "2K2")
      (footprint "eagle-import:0603")
      (libsource (lib "eagle-import") (part "R0603"))
    )
    (comp (ref "R41")
      (value "2K2")
      (footprint "eagle-import:0603")
      (libsource (lib "eagle-import") (part "R0603"))
    )
    (comp (ref "R42")
      (value "10K")
      (footprint "eagle-import:0603")
      (libsource (lib "eagle-import") (part "R0603"))
    )
    (comp (ref "R43")
      (value "15K")
      (footprint "eagle-import:0603")
      (libsource (lib "eagle-import") (part "R0603"))
    )
    (comp (ref "R44")
      (value "470K/DNP")
      (footprint "eagle-import:0603")
      (libsource (lib "eagle-import") (part "R0603"))
    )
    (comp (ref "R45")
      (value "1M")
      (footprint "eagle-import:0805")
      (libsource (lib "eagle-import") (part "R0805"))
    )
    (comp (ref "R46")
      (value "82R5")
      (footprint "eagle-import:0603")
      (libsource (lib "eagle-import") (part "R0603"))
    )
    (comp (ref "R47")
      (value "82R5")
      (footprint "eagle-import:0603")
      (libsource (lib "eagle-import") (part "R0603"))
    )
    (comp (ref "R48")
      (value "130R")
      (footprint "eagle-import:0603")
      (libsource (lib "eagle-import") (part "R0603"))
    )
    (comp (ref "R49")
      (value "130R")
      (footprint "eagle-import:0603")
      (libsource (lib "eagle-import") (part "R0603"))
    )
    (comp (ref "R50")
      (value "130R")
      (footprint "eagle-import:0603")
      (libsource (lib "eagle-import") (part "R0603"))
    )
    (comp (ref "R51")
      (value "1K24")
      (footprint "eagle-import:0603")
      (libsource (lib "eagle-import") (part "R0603"))
    )
    (comp (ref "R52")
      (value "619R")
      (footprint "eagle-import:0603")
      (libsource (lib "eagle-import") (part "R0603"))
    )
    (comp (ref "R53")
      (value "1K24")
      (footprint "eagle-import:0603")
      (libsource (lib "eagle-import") (part "R0603"))
    )
    (comp (ref "R54")
      (value "619R")
      (footprint "eagle-import:0603")
      (libsource (lib "eagle-import") (part "R0603"))
    )
    (comp (ref "R55")
      (value "1K24")
      (footprint "eagle-import:0603")
      (libsource (lib "eagle-import") (part "R0603"))
    )
    (comp (ref "R56")
      (value "619R")
      (footprint "eagle-import:0603")
      (libsource (lib "eagle-import") (part "R0603"))
    )
    (comp (ref "R57")
      (value "15K")
      (footprint "eagle-import:0603")
      (libsource (lib "eagle-import") (part "R0603"))
    )
    (comp (ref "R58")
      (value "309R")
      (footprint "eagle-import:0603")
      (libsource (lib "eagle-import") (part "R0603"))
    )
    (comp (ref "R59")
      (value "309R")
      (footprint "eagle-import:0603")
      (libsource (lib "eagle-import") (part "R0603"))
    )
    (comp (ref "R60")
      (value "309R")
      (footprint "eagle-import:0603")
      (libsource (lib "eagle-import") (part "R0603"))
    )
    (comp (ref "R61")
      (value "220R")
      (footprint "eagle-import:0603")
      (libsource (lib "eagle-import") (part "R0603"))
    )
    (comp (ref "R62")
      (value "100R")
      (footprint "eagle-import:0603")
      (libsource (lib "eagle-import") (part "R0603"))
    )
    (comp (ref "R63")
      (value "1K8")
      (footprint "eagle-import:0603")
      (libsource (lib "eagle-import") (part "R0603"))
    )
    (comp (ref "R64")
      (value "220R")
      (footprint "eagle-import:0603")
      (libsource (lib "eagle-import") (part "R0603"))
    )
    (comp (ref "R65")
      (value "100R")
      (footprint "eagle-import:0603")
      (libsource (lib "eagle-import") (part "R0603"))
    )
    (comp (ref "R66")
      (value "1K8")
      (footprint "eagle-import:0603")
      (libsource (lib "eagle-import") (part "R0603"))
    )
    (comp (ref "R67")
      (value "0R/DNP")
      (footprint "eagle-import:0603")
      (libsource (lib "eagle-import") (part "R0603"))
    )
    (comp (ref "R68")
      (value "0R/DNP")
      (footprint "eagle-import:0603")
      (libsource (lib "eagle-import") (part "R0603"))
    )
    (comp (ref "R69")
      (value "2K2")
      (footprint "eagle-import:0603")
      (libsource (lib "eagle-import") (part "R0603"))
    )
    (comp (ref "R70")
      (value "2K2")
      (footprint "eagle-import:0603")
      (libsource (lib "eagle-import") (part "R0603"))
    )
    (comp (ref "R71")
      (value "2K2")
      (footprint "eagle-import:0603")
      (libsource (lib "eagle-import") (part "R0603"))
    )
    (comp (ref "R78")
      (value "10K")
      (footprint "eagle-import:0603")
      (libsource (lib "eagle-import") (part "R0603"))
    )
    (comp (ref "R79")
      (value "2K2")
      (footprint "eagle-import:0603")
      (libsource (lib "eagle-import") (part "R0603"))
    )
    (comp (ref "R80")
      (value "2K2")
      (footprint "eagle-import:0603")
      (libsource (lib "eagle-import") (part "R0603"))
    )
    (comp (ref "R81")
      (value "0R")
      (footprint "eagle-import:0603")
      (libsource (lib "eagle-import") (part "R0603"))
    )
    (comp (ref "R82")
      (value "12K1")
      (footprint "eagle-import:0603")
      (libsource (lib "eagle-import") (part "R0603"))
    )
    (comp (ref "R83")
      (value "49R9")
      (footprint "eagle-import:0603")
      (libsource (lib "eagle-import") (part "R0603"))
    )
    (comp (ref "R84")
      (value "49R9")
      (footprint "eagle-import:0603")
      (libsource (lib "eagle-import") (part "R0603"))
    )
    (comp (ref "R85")
      (value "49R9")
      (footprint "eagle-import:0603")
      (libsource (lib "eagle-import") (part "R0603"))
    )
    (comp (ref "R86")
      (value "49R9")
      (footprint "eagle-import:0603")
      (libsource (lib "eagle-import") (part "R0603"))
    )
    (comp (ref "R87")
      (value "330R")
      (footprint "eagle-import:0603")
      (libsource (lib "eagle-import") (part "R0603"))
    )
    (comp (ref "R88")
      (value "330R")
      (footprint "eagle-import:0603")
      (libsource (lib "eagle-import") (part "R0603"))
    )
    (comp (ref "RN1")
      (value "330R")
      (footprint "eagle-import:EXB28V")
      (libsource (lib "eagle-import") (part "4R-NEXB28V"))
    )
    (comp (ref "RN2")
      (value "330R")
      (footprint "eagle-import:EXB28V")
      (libsource (lib "eagle-import") (part "4R-NEXB28V"))
    )
    (comp (ref "RN3")
      (value "330R")
      (footprint "eagle-import:EXB28V")
      (libsource (lib "eagle-import") (part "4R-NEXB28V"))
    )
    (comp (ref "RN4")
      (value "330R")
      (footprint "eagle-import:EXB28V")
      (libsource (lib "eagle-import") (part "4R-NEXB28V"))
    )
    (comp (ref "RN5")
      (value "330R")
      (footprint "eagle-import:EXB28V")
      (libsource (lib "eagle-import") (part "4R-NEXB28V"))
    )
    (comp (ref "RN6")
      (value "330R")
      (footprint "eagle-import:EXB28V")
      (libsource (lib "eagle-import") (part "4R-NEXB28V"))
    )
    (comp (ref "RN7")
      (value "33R")
      (footprint "eagle-import:EXB28V")
      (libsource (lib "eagle-import") (part "4R-NEXB28V"))
    )
    (comp (ref "RN8")
      (value "33R")
      (footprint "eagle-import:EXB28V")
      (libsource (lib "eagle-import") (part "4R-NEXB28V"))
    )
    (comp (ref "S1")
      (value "SWITCHES_SMD-4")
      (footprint "eagle-import:TACTILE_SWITCH_TALL")
      (libsource (lib "eagle-import") (part "SWITCHES_SMD-4"))
    )
    (comp (ref "S2")
      (value "SWITCHES_SMD-4")
      (footprint "eagle-import:TACTILE_SWITCH_TALL")
      (libsource (lib "eagle-import") (part "SWITCHES_SMD-4"))
    )
    (comp (ref "S3")
      (value "SWITCHES_SMD-4")
      (footprint "eagle-import:TACTILE_SWITCH_TALL")
      (libsource (lib "eagle-import") (part "SWITCHES_SMD-4"))
    )
    (comp (ref "SD1")
      (value "1040310811")
      (footprint "eagle-import:1040310811")
      (libsource (lib "eagle-import") (part "1040310811"))
    )
    (comp (ref "T1")
      (value "Hanrun HR917550A")
      (footprint "eagle-import:HR13550A")
      (libsource (lib "eagle-import") (part "HR913550A"))
    )
    (comp (ref "TP1")
      (value "TPTP12R")
      (footprint "eagle-import:TP12R")
      (libsource (lib "eagle-import") (part "TPTP12R"))
    )
    (comp (ref "TP2")
      (value "TPTP12R")
      (footprint "eagle-import:TP12R")
      (libsource (lib "eagle-import") (part "TPTP12R"))
    )
    (comp (ref "TP3")
      (value "TPTP12R")
      (footprint "eagle-import:TP12R")
      (libsource (lib "eagle-import") (part "TPTP12R"))
    )
    (comp (ref "TP4")
      (value "TPTP08R")
      (footprint "eagle-import:TP08R")
      (libsource (lib "eagle-import") (part "TPTP08R"))
    )
    (comp (ref "TV26")
      (value "SP0503BAHT")
      (footprint "eagle-import:SP0503")
      (libsource (lib "eagle-import") (part "SP0503BAHT"))
    )
    (comp (ref "U$1")
      (value "KC3225K-32MHz")
      (footprint "eagle-import:KC3225K")
      (libsource (lib "eagle-import") (part "KC3225K"))
    )
    (comp (ref "U$2")
      (value "INTERFACEZ_EDGEDAUGHTER")
      (footprint "eagle-import:INTERFACEZ_EXPANSION_DAUGHTERCARD")
      (libsource (lib "eagle-import") (part "INTERFACEZ_EDGEDAUGHTER"))
    )
    (comp (ref "U$3")
      (value "PMS150C-U06")
      (footprint "eagle-import:SOT23-6")
      (libsource (lib "eagle-import") (part "PMS150C-U06"))
    )
    (comp (ref "U$4")
      (value "BSS84DW")
      (footprint "eagle-import:SOT363_INFINEON")
      (libsource (lib "eagle-import") (part "BSS84DW"))
    )
    (comp (ref "U$5")
      (value "INTERFACEZ_EDGEDAUGHTER")
      (footprint "eagle-import:INTERFACEZ_EXPANSION_DAUGHTERCARD")
      (libsource (lib "eagle-import") (part "INTERFACEZ_EDGEDAUGHTER"))
    )
    (comp (ref "U$6")
      (value "PMS150C-U06")
      (footprint "eagle-import:SOT23-6")
      (libsource (lib "eagle-import") (part "PMS150C-U06"))
    )
    (comp (ref "U$7")
      (value "PIN-1X10")
      (footprint "eagle-import:PIN-1X10")
      (libsource (lib "eagle-import") (part "PIN-1X10"))
    )
    (comp (ref "U$8")
      (value "INTERFACEZ_EDGEDAUGHTER")
      (footprint "eagle-import:INTERFACEZ_EXPANSION_DAUGHTERCARD")
      (libsource (lib "eagle-import") (part "INTERFACEZ_EDGEDAUGHTER"))
    )
    (comp (ref "U$9")
      (value "PJ328-A0")
      (footprint "eagle-import:PJ328A0")
      (libsource (lib "eagle-import") (part "PJ328-A0"))
    )
    (comp (ref "U$10")
      (value "INTERFACEZ_EDGEDAUGHTER")
      (footprint "eagle-import:INTERFACEZ_EXPANSION_DAUGHTERCARD")
      (libsource (lib "eagle-import") (part "INTERFACEZ_EDGEDAUGHTER"))
    )
    (comp (ref "U$11")
      (value "PMS150C-U06")
      (footprint "eagle-import:SOT23-6")
      (libsource (lib "eagle-import") (part "PMS150C-U06"))
    )
    (comp (ref "U$15")
      (value "PIN-2X5-1.27MM")
      (footprint "eagle-import:PIN-2X5-1.27")
      (libsource (lib "eagle-import") (part "PIN-2X5-1.27MM"))
    )
    (comp (ref "U$16")
      (value "PIN-2X5")
      (footprint "eagle-import:PIN-2X5")
      (libsource (lib "eagle-import") (part "PIN-2X5"))
    )
    (comp (ref "U1")
      (value "ESP-WROOM-32")
      (footprint "eagle-import:ESP-WROOM-32")
      (libsource (lib "eagle-import") (part "ESP-WROOM-32"))
    )
    (comp (ref "USB1")
      (value "CON-USB-F-MICRO-B")
      (footprint "eagle-import:CONN_USB_MICRO-B")
      (libsource (lib "eagle-import") (part "CON-USB-F-MICRO-B"))
    )
    (comp (ref "USB2")
      (value "USB-A-H")
      (footprint "eagle-import:USB-A-H")
      (libsource (lib "eagle-import") (part "USB-A-H"))
    )
    (comp (ref "X1")
      (value "F15HDH")
      (footprint "eagle-import:HDF15H")
      (libsource (lib "eagle-import") (part "F15HDH"))
    )
  )
  (nets
    (net (code "1") (name "+1V2") (class "Default")
      (node (ref "C12") (pin "1") (pinfunction "1_1") (pintype "passive"))
      (node (ref "C14") (pin "1") (pinfunction "1_1") (pintype "passive"))
      (node (ref "C18") (pin "1") (pinfunction "1_1") (pintype "passive"))
      (node (ref "C21") (pin "1") (pinfunction "1_1") (pintype "passive"))
      (node (ref "C22") (pin "1") (pinfunction "1_1") (pintype "passive"))
      (node (ref "C26") (pin "1") (pinfunction "1_1") (pintype "passive"))
      (node (ref "C28") (pin "1") (pinfunction "1_1") (pintype "passive"))
      (node (ref "C4") (pin "1") (pinfunction "1_1") (pintype "passive"))
      (node (ref "C45") (pin "2") (pinfunction "2_2") (pintype "passive"))
      (node (ref "C7") (pin "1") (pinfunction "1_1") (pintype "passive"))
      (node (ref "C9") (pin "1") (pinfunction "1_1") (pintype "passive"))
      (node (ref "IC2") (pin "102") (pinfunction "__VCCINT_6_102") (pintype "power_in"))
      (node (ref "IC2") (pin "109") (pinfunction "__VCCD_PLL2_109") (pintype "power_in"))
      (node (ref "IC2") (pin "116") (pinfunction "__VCCINT_7_116") (pintype "power_in"))
      (node (ref "IC2") (pin "134") (pinfunction "__VCCINT_8_134") (pintype "power_in"))
      (node (ref "IC2") (pin "29") (pinfunction "__VCCINT_2_29") (pintype "power_in"))
      (node (ref "IC2") (pin "37") (pinfunction "__VCCD_PLL1_37") (pintype "power_in"))
      (node (ref "IC2") (pin "45") (pinfunction "__VCCINT_3_45") (pintype "power_in"))
      (node (ref "IC2") (pin "5") (pinfunction "__VCCINT_1_5") (pintype "power_in"))
      (node (ref "IC2") (pin "61") (pinfunction "__VCCINT_4_61") (pintype "power_in"))
      (node (ref "IC2") (pin "78") (pinfunction "__VCCINT_5_78") (pintype "power_in"))
      (node (ref "L1") (pin "P$2") (pinfunction "2_P$2") (pintype "passive"))
      (node (ref "R19") (pin "2") (pinfunction "2_2") (pintype "passive"))
      (node (ref "TP1") (pin "TP") (pinfunction "TP_TP") (pintype "input"))
    )
    (net (code "2") (name "+2V5") (class "Default")
      (node (ref "C27") (pin "1") (pinfunction "1_1") (pintype "passive"))
      (node (ref "C47") (pin "2") (pinfunction "2_2") (pintype "passive"))
      (node (ref "C8") (pin "1") (pinfunction "1_1") (pintype "passive"))
      (node (ref "IC2") (pin "107") (pinfunction "__VCCA2_107") (pintype "power_in"))
      (node (ref "IC2") (pin "35") (pinfunction "__VCCA1_35") (pintype "power_in"))
      (node (ref "IC8") (pin "5") (pinfunction "VOUT_5") (pintype "power_in"))
      (node (ref "TP3") (pin "TP") (pinfunction "TP_TP") (pintype "input"))
    )
    (net (code "3") (name "+3V3") (class "Default")
      (node (ref "C10") (pin "1") (pinfunction "1_1") (pintype "passive"))
      (node (ref "C11") (pin "1") (pinfunction "1_1") (pintype "passive"))
      (node (ref "C13") (pin "1") (pinfunction "1_1") (pintype "passive"))
      (node (ref "C15") (pin "1") (pinfunction "1_1") (pintype "passive"))
      (node (ref "C16") (pin "1") (pinfunction "1_1") (pintype "passive"))
      (node (ref "C17") (pin "1") (pinfunction "1_1") (pintype "passive"))
      (node (ref "C19") (pin "1") (pinfunction "1_1") (pintype "passive"))
      (node (ref "C20") (pin "1") (pinfunction "1_1") (pintype "passive"))
      (node (ref "C23") (pin "1") (pinfunction "1_1") (pintype "passive"))
      (node (ref "C24") (pin "1") (pinfunction "1_1") (pintype "passive"))
      (node (ref "C25") (pin "1") (pinfunction "1_1") (pintype "passive"))
      (node (ref "C29") (pin "1") (pinfunction "1_1") (pintype "passive"))
      (node (ref "C3") (pin "1") (pinfunction "1_1") (pintype "passive"))
      (node (ref "C30") (pin "1") (pinfunction "1_1") (pintype "passive"))
      (node (ref "C37") (pin "1") (pinfunction "1_1") (pintype "passive"))
      (node (ref "C40") (pin "1") (pinfunction "1_1") (pintype "passive"))
      (node (ref "C41") (pin "1") (pinfunction "1_1") (pintype "passive"))
      (node (ref "C44") (pin "2") (pinfunction "2_2") (pintype "passive"))
      (node (ref "C46") (pin "2") (pinfunction "2_2") (pintype "passive"))
      (node (ref "C48") (pin "2") (pinfunction "2_2") (pintype "passive"))
      (node (ref "C49") (pin "2") (pinfunction "2_2") (pintype "passive"))
      (node (ref "C5") (pin "1") (pinfunction "1_1") (pintype "passive"))
      (node (ref "C51") (pin "2") (pinfunction "2_2") (pintype "passive"))
      (node (ref "C52") (pin "1") (pinfunction "1_1") (pintype "passive"))
      (node (ref "C53") (pin "1") (pinfunction "1_1") (pintype "passive"))
      (node (ref "C56") (pin "1") (pinfunction "1_1") (pintype "passive"))
      (node (ref "C57") (pin "PLUS") (pinfunction "+_PLUS") (pintype "passive"))
      (node (ref "C6") (pin "1") (pinfunction "1_1") (pintype "passive"))
      (node (ref "C60") (pin "PLUS") (pinfunction "+_PLUS") (pintype "passive"))
      (node (ref "C63") (pin "2") (pinfunction "2_2") (pintype "passive"))
      (node (ref "C64") (pin "2") (pinfunction "2_2") (pintype "passive"))
      (node (ref "C65") (pin "PLUS") (pinfunction "+_PLUS") (pintype "passive"))
      (node (ref "C66") (pin "2") (pinfunction "2_2") (pintype "passive"))
      (node (ref "C93") (pin "2") (pinfunction "2_2") (pintype "passive"))
      (node (ref "C94") (pin "2") (pinfunction "2_2") (pintype "passive"))
      (node (ref "C95") (pin "2") (pinfunction "2_2") (pintype "passive"))
      (node (ref "C96") (pin "2") (pinfunction "2_2") (pintype "passive"))
      (node (ref "IC10") (pin "1") (pinfunction "DIR_1") (pintype "input"))
      (node (ref "IC10") (pin "20") (pinfunction "VCC_20") (pintype "power_in"))
      (node (ref "IC11") (pin "1") (pinfunction "DIR_1") (pintype "input"))
      (node (ref "IC11") (pin "20") (pinfunction "VCC_20") (pintype "power_in"))
      (node (ref "IC12") (pin "14") (pinfunction "VCC_14") (pintype "power_in"))
      (node (ref "IC13") (pin "5") (pinfunction "VCC_5") (pintype "power_in"))
      (node (ref "IC14") (pin "1") (pinfunction "VDD2A_1") (pintype "bidirectional"))
      (node (ref "IC14") (pin "19") (pinfunction "VDD1A_19") (pintype "bidirectional"))
      (node (ref "IC14") (pin "9") (pinfunction "VDDIO_9") (pintype "bidirectional"))
      (node (ref "IC2") (pin "117") (pinfunction "__VCCIO7_1_117") (pintype "power_in"))
      (node (ref "IC2") (pin "122") (pinfunction "__VCCIO7_2_122") (pintype "power_in"))
      (node (ref "IC2") (pin "130") (pinfunction "__VCCIO8_1_130") (pintype "power_in"))
      (node (ref "IC2") (pin "139") (pinfunction "__VCCIO8_2_139") (pintype "power_in"))
      (node (ref "IC2") (pin "17") (pinfunction "__VCCIO1_17") (pintype "power_in"))
      (node (ref "IC2") (pin "26") (pinfunction "__VCCIO2_26") (pintype "power_in"))
      (node (ref "IC2") (pin "40") (pinfunction "__VCCIO3_1_40") (pintype "power_in"))
      (node (ref "IC2") (pin "47") (pinfunction "__VCCIO3_2_47") (pintype "power_in"))
      (node (ref "IC2") (pin "56") (pinfunction "__VCCIO4_1_56") (pintype "power_in"))
      (node (ref "IC2") (pin "62") (pinfunction "__VCCIO4_2_62") (pintype "power_in"))
      (node (ref "IC2") (pin "81") (pinfunction "__VCCIO5_81") (pintype "power_in"))
      (node (ref "IC2") (pin "93") (pinfunction "__VCCIO6_93") (pintype "power_in"))
      (node (ref "IC2") (pin "97") (pinfunction "__MSEL2_97") (pintype "bidirectional"))
      (node (ref "IC3") (pin "1") (pinfunction "DIR_1") (pintype "input"))
      (node (ref "IC3") (pin "20") (pinfunction "VCC_20") (pintype "power_in"))
      (node (ref "IC4") (pin "20") (pinfunction "VCC_20") (pintype "power_in"))
      (node (ref "IC7") (pin "5") (pinfunction "VCC_5") (pintype "power_in"))
      (node (ref "IC7") (pin "8") (pinfunction "V3_8") (pintype "passive"))
      (node (ref "IC8") (pin "3") (pinfunction "EN_3") (pintype "input"))
      (node (ref "IC9") (pin "8") (pinfunction "VCC_8") (pintype "power_in"))
      (node (ref "J1") (pin "4") (pinfunction "4_4") (pintype "passive"))
      (node (ref "JP1") (pin "1") (pinfunction "1_1") (pintype "passive"))
      (node (ref "L2") (pin "P$2") (pinfunction "2_P$2") (pintype "passive"))
      (node (ref "L8") (pin "1") (pinfunction "1_1") (pintype "passive"))
      (node (ref "LED1") (pin "A") (pinfunction "A_A") (pintype "passive"))
      (node (ref "LED2") (pin "A") (pinfunction "A_A") (pintype "passive"))
      (node (ref "LED3") (pin "A") (pinfunction "A_A") (pintype "passive"))
      (node (ref "LED4") (pin "A") (pinfunction "A_A") (pintype "passive"))
      (node (ref "LED5") (pin "A") (pinfunction "A_A") (pintype "passive"))
      (node (ref "LED6") (pin "A") (pinfunction "A_A") (pintype "passive"))
      (node (ref "R1") (pin "1") (pinfunction "1_1") (pintype "passive"))
      (node (ref "R2") (pin "2") (pinfunction "2_2") (pintype "passive"))
      (node (ref "R20") (pin "2") (pinfunction "2_2") (pintype "passive"))
      (node (ref "R24") (pin "1") (pinfunction "1_1") (pintype "passive"))
      (node (ref "R25") (pin "1") (pinfunction "1_1") (pintype "passive"))
      (node (ref "R26") (pin "1") (pinfunction "1_1") (pintype "passive"))
      (node (ref "R27") (pin "2") (pinfunction "2_2") (pintype "passive"))
      (node (ref "R28") (pin "1") (pinfunction "1_1") (pintype "passive"))
      (node (ref "R3") (pin "2") (pinfunction "2_2") (pintype "passive"))
      (node (ref "R30") (pin "2") (pinfunction "2_2") (pintype "passive"))
      (node (ref "R31") (pin "2") (pinfunction "2_2") (pintype "passive"))
      (node (ref "R32") (pin "2") (pinfunction "2_2") (pintype "passive"))
      (node (ref "R34") (pin "2") (pinfunction "2_2") (pintype "passive"))
      (node (ref "R38") (pin "2") (pinfunction "2_2") (pintype "passive"))
      (node (ref "R4") (pin "2") (pinfunction "2_2") (pintype "passive"))
      (node (ref "R6") (pin "2") (pinfunction "2_2") (pintype "passive"))
      (node (ref "R69") (pin "2") (pinfunction "2_2") (pintype "passive"))
      (node (ref "R7") (pin "2") (pinfunction "2_2") (pintype "passive"))
      (node (ref "R70") (pin "2") (pinfunction "2_2") (pintype "passive"))
      (node (ref "R71") (pin "2") (pinfunction "2_2") (pintype "passive"))
      (node (ref "R78") (pin "2") (pinfunction "2_2") (pintype "passive"))
      (node (ref "R79") (pin "2") (pinfunction "2_2") (pintype "passive"))
      (node (ref "R8") (pin "2") (pinfunction "2_2") (pintype "passive"))
      (node (ref "R80") (pin "2") (pinfunction "2_2") (pintype "passive"))
      (node (ref "R9") (pin "2") (pinfunction "2_2") (pintype "passive"))
      (node (ref "SD1") (pin "4") (pinfunction "VDD_4") (pintype "power_in"))
      (node (ref "TP2") (pin "TP") (pinfunction "TP_TP") (pintype "input"))
      (node (ref "U$1") (pin "1") (pinfunction "OE_1") (pintype "input"))
      (node (ref "U$1") (pin "4") (pinfunction "VCC_4") (pintype "power_in"))
      (node (ref "U$10") (pin "B1") (pinfunction "+3V3_B1") (pintype "power_in"))
      (node (ref "U$11") (pin "5") (pinfunction "VCC_5") (pintype "power_in"))
      (node (ref "U$2") (pin "B1") (pinfunction "+3V3_B1") (pintype "power_in"))
      (node (ref "U$3") (pin "5") (pinfunction "VCC_5") (pintype "power_in"))
      (node (ref "U$4") (pin "1") (pinfunction "S_1") (pintype "passive"))
      (node (ref "U$4") (pin "4") (pinfunction "S_4") (pintype "passive"))
      (node (ref "U$5") (pin "B1") (pinfunction "+3V3_B1") (pintype "power_in"))
      (node (ref "U$6") (pin "5") (pinfunction "VCC_5") (pintype "power_in"))
      (node (ref "U$7") (pin "1") (pinfunction "1_1") (pintype "passive"))
      (node (ref "U$8") (pin "B1") (pinfunction "+3V3_B1") (pintype "power_in"))
      (node (ref "U1") (pin "2") (pinfunction "3V3_2") (pintype "bidirectional"))
    )
    (net (code "4") (name "+5V") (class "Default")
      (node (ref "CONN1") (pin "A3") (pinfunction "+5V_A3") (pintype "power_in"))
      (node (ref "IC1") (pin "5") (pinfunction "VIN_5") (pintype "power_in"))
      (node (ref "IC8") (pin "1") (pinfunction "VIN_1") (pintype "power_in"))
      (node (ref "Q3") (pin "4") (pinfunction "S_4") (pintype "passive"))
      (node (ref "Q4") (pin "4") (pinfunction "S_4") (pintype "passive"))
      (node (ref "Q5") (pin "2") (pinfunction "S_2") (pintype "passive"))
      (node (ref "R11") (pin "2") (pinfunction "2_2") (pintype "passive"))
      (node (ref "R12") (pin "2") (pinfunction "2_2") (pintype "passive"))
      (node (ref "R42") (pin "1") (pinfunction "1_1") (pintype "passive"))
      (node (ref "R5") (pin "1") (pinfunction "1_1") (pintype "passive"))
      (node (ref "U$5") (pin "A1") (pinfunction "+5V_A1") (pintype "power_in"))
    )
    (net (code "5") (name "+9V") (class "Default")
      (node (ref "C31") (pin "2") (pinfunction "2_2") (pintype "passive"))
      (node (ref "C32") (pin "2") (pinfunction "2_2") (pintype "passive"))
      (node (ref "C33") (pin "2") (pinfunction "2_2") (pintype "passive"))
      (node (ref "C34") (pin "2") (pinfunction "2_2") (pintype "passive"))
      (node (ref "CONN1") (pin "A4") (pinfunction "+9V_A4") (pintype "power_in"))
      (node (ref "IC5") (pin "2") (pinfunction "IN_2") (pintype "power_in"))
      (node (ref "IC6") (pin "2") (pinfunction "IN_2") (pintype "power_in"))
    )
    (net (code "6") (name "/+12V") (class "Default")
      (node (ref "CONN1") (pin "B22") (pinfunction "+12V_B22") (pintype "power_in"))
    )
    (net (code "7") (name "/-5V") (class "Default")
      (node (ref "CONN1") (pin "B20") (pinfunction "-5V_B20") (pintype "power_in"))
    )
    (net (code "8") (name "/-12V") (class "Default")
      (node (ref "CONN1") (pin "B23") (pinfunction "-12V_B23") (pintype "power_in"))
    )
    (net (code "9") (name "/A0") (class "Default")
      (node (ref "CONN1") (pin "A9") (pinfunction "A0_A9") (pintype "bidirectional"))
      (node (ref "RN4") (pin "1") (pinfunction "1_1") (pintype "passive"))
    )
    (net (code "10") (name "/A1") (class "Default")
      (node (ref "CONN1") (pin "A10") (pinfunction "A1_A10") (pintype "bidirectional"))
      (node (ref "RN4") (pin "2") (pinfunction "1_2") (pintype "passive"))
    )
    (net (code "11") (name "/A2") (class "Default")
      (node (ref "CONN1") (pin "A11") (pinfunction "A2_A11") (pintype "bidirectional"))
      (node (ref "RN4") (pin "3") (pinfunction "1_3") (pintype "passive"))
    )
    (net (code "12") (name "/A3") (class "Default")
      (node (ref "CONN1") (pin "A12") (pinfunction "A3_A12") (pintype "bidirectional"))
      (node (ref "RN4") (pin "4") (pinfunction "1_4") (pintype "passive"))
    )
    (net (code "13") (name "/A4") (class "Default")
      (node (ref "CONN1") (pin "A24") (pinfunction "A4_A24") (pintype "bidirectional"))
      (node (ref "RN5") (pin "4") (pinfunction "1_4") (pintype "passive"))
    )
    (net (code "14") (name "/A5") (class "Default")
      (node (ref "CONN1") (pin "A23") (pinfunction "A5_A23") (pintype "bidirectional"))
      (node (ref "RN5") (pin "3") (pinfunction "1_3") (pintype "passive"))
    )
    (net (code "15") (name "/A6") (class "Default")
      (node (ref "CONN1") (pin "A22") (pinfunction "A6_A22") (pintype "bidirectional"))
      (node (ref "RN5") (pin "2") (pinfunction "1_2") (pintype "passive"))
    )
    (net (code "16") (name "/A7") (class "Default")
      (node (ref "CONN1") (pin "A21") (pinfunction "A7_A21") (pintype "bidirectional"))
      (node (ref "RN5") (pin "1") (pinfunction "1_1") (pintype "passive"))
    )
    (net (code "17") (name "/A8") (class "Default")
      (node (ref "CONN1") (pin "B26") (pinfunction "A8_B26") (pintype "bidirectional"))
      (node (ref "RN6") (pin "1") (pinfunction "1_1") (pintype "passive"))
    )
    (net (code "18") (name "/A9") (class "Default")
      (node (ref "CONN1") (pin "A27") (pinfunction "A9_A27") (pintype "bidirectional"))
      (node (ref "RN6") (pin "2") (pinfunction "1_2") (pintype "passive"))
    )
    (net (code "19") (name "/A10") (class "Default")
      (node (ref "CONN1") (pin "B27") (pinfunction "A10_B27") (pintype "bidirectional"))
      (node (ref "RN6") (pin "3") (pinfunction "1_3") (pintype "passive"))
    )
    (net (code "20") (name "/A11") (class "Default")
      (node (ref "CONN1") (pin "A28") (pinfunction "A11_A28") (pintype "bidirectional"))
      (node (ref "RN6") (pin "4") (pinfunction "1_4") (pintype "passive"))
    )
    (net (code "21") (name "/A12") (class "Default")
      (node (ref "CONN1") (pin "A2") (pinfunction "A12_A2") (pintype "bidirectional"))
      (node (ref "RN3") (pin "4") (pinfunction "1_4") (pintype "passive"))
    )
    (net (code "22") (name "/A13") (class "Default")
      (node (ref "CONN1") (pin "B2") (pinfunction "A13_B2") (pintype "bidirectional"))
      (node (ref "RN3") (pin "3") (pinfunction "1_3") (pintype "passive"))
    )
    (net (code "23") (name "/A14") (class "Default")
      (node (ref "CONN1") (pin "A1") (pinfunction "A14_A1") (pintype "bidirectional"))
      (node (ref "RN3") (pin "2") (pinfunction "1_2") (pintype "passive"))
    )
    (net (code "24") (name "/A15") (class "Default")
      (node (ref "CONN1") (pin "B1") (pinfunction "A15_B1") (pintype "bidirectional"))
      (node (ref "RN3") (pin "1") (pinfunction "1_1") (pintype "passive"))
    )
    (net (code "25") (name "/AUDIO_L") (class "Default")
      (node (ref "IC13") (pin "3") (pinfunction "I_3") (pintype "input"))
      (node (ref "R68") (pin "1") (pinfunction "1_1") (pintype "passive"))
      (node (ref "U$8") (pin "A6") (pinfunction "E11_A6") (pintype "bidirectional"))
    )
    (net (code "26") (name "/AUDIO_R") (class "Default")
      (node (ref "IC13") (pin "1") (pinfunction "I_1") (pintype "input"))
      (node (ref "R67") (pin "1") (pinfunction "1_1") (pintype "passive"))
      (node (ref "U$8") (pin "A5") (pinfunction "E12_A5") (pintype "bidirectional"))
    )
    (net (code "27") (name "/A_BUS_OE") (class "Default")
      (node (ref "IC10") (pin "19") (pinfunction "G_19") (pintype "input"))
      (node (ref "IC11") (pin "19") (pinfunction "G_19") (pintype "input"))
      (node (ref "IC2") (pin "10") (pinfunction "__IO_7_10") (pintype "bidirectional"))
      (node (ref "R25") (pin "2") (pinfunction "2_2") (pintype "passive"))
    )
    (net (code "28") (name "/BLUE") (class "Default")
      (node (ref "R50") (pin "2") (pinfunction "2_2") (pintype "passive"))
      (node (ref "R55") (pin "2") (pinfunction "2_2") (pintype "passive"))
      (node (ref "R56") (pin "2") (pinfunction "2_2") (pintype "passive"))
      (node (ref "R60") (pin "2") (pinfunction "2_2") (pintype "passive"))
      (node (ref "X1") (pin "3") (pinfunction "3_3") (pintype "passive"))
    )
    (net (code "29") (name "/BLUE0") (class "Default")
      (node (ref "R55") (pin "1") (pinfunction "1_1") (pintype "passive"))
      (node (ref "U$8") (pin "A10") (pinfunction "E7_A10") (pintype "bidirectional"))
    )
    (net (code "30") (name "/BLUE1") (class "Default")
      (node (ref "R56") (pin "1") (pinfunction "1_1") (pintype "passive"))
      (node (ref "U$8") (pin "B10") (pinfunction "E6_B10") (pintype "bidirectional"))
    )
    (net (code "31") (name "/BLUE2") (class "Default")
      (node (ref "R60") (pin "1") (pinfunction "1_1") (pintype "passive"))
      (node (ref "U$8") (pin "A9") (pinfunction "E8_A9") (pintype "bidirectional"))
    )
    (net (code "32") (name "/BUF_L") (class "Default")
      (node (ref "IC13") (pin "6") (pinfunction "O_6") (pintype "tri_state"))
      (node (ref "R64") (pin "2") (pinfunction "2_2") (pintype "passive"))
      (node (ref "R67") (pin "2") (pinfunction "2_2") (pintype "passive"))
    )
    (net (code "33") (name "/BUF_R") (class "Default")
      (node (ref "IC13") (pin "4") (pinfunction "O_4") (pintype "tri_state"))
      (node (ref "R61") (pin "2") (pinfunction "2_2") (pintype "passive"))
      (node (ref "R68") (pin "2") (pinfunction "2_2") (pintype "passive"))
    )
    (net (code "34") (name "/CK") (class "Default")
      (node (ref "CONN1") (pin "A8") (pinfunction "CK_A8") (pintype "bidirectional"))
      (node (ref "RN1") (pin "1") (pinfunction "1_1") (pintype "passive"))
    )
    (net (code "35") (name "/CLKIN") (class "Default")
      (node (ref "R81") (pin "1") (pinfunction "1_1") (pintype "passive"))
      (node (ref "U$10") (pin "B4") (pinfunction "E0_B4") (pintype "bidirectional"))
    )
    (net (code "36") (name "/CONF_DONE") (class "Default")
      (node (ref "IC2") (pin "92") (pinfunction "__CONF_DONE_92") (pintype "bidirectional"))
      (node (ref "R27") (pin "1") (pinfunction "1_1") (pintype "passive"))
      (node (ref "U1") (pin "7") (pinfunction "IO35_7") (pintype "input"))
    )
    (net (code "37") (name "/CTRL_OE") (class "Default")
      (node (ref "IC2") (pin "129") (pinfunction "__IO_74_129") (pintype "bidirectional"))
      (node (ref "IC3") (pin "19") (pinfunction "G_19") (pintype "input"))
      (node (ref "R26") (pin "2") (pinfunction "2_2") (pintype "passive"))
    )
    (net (code "38") (name "/D0") (class "Default")
      (node (ref "CONN1") (pin "B6") (pinfunction "D0_B6") (pintype "bidirectional"))
      (node (ref "RN7") (pin "2") (pinfunction "1_2") (pintype "passive"))
    )
    (net (code "39") (name "/D1") (class "Default")
      (node (ref "CONN1") (pin "B7") (pinfunction "D1_B7") (pintype "bidirectional"))
      (node (ref "RN7") (pin "3") (pinfunction "1_3") (pintype "passive"))
    )
    (net (code "40") (name "/D2") (class "Default")
      (node (ref "CONN1") (pin "B8") (pinfunction "D2_B8") (pintype "bidirectional"))
      (node (ref "RN7") (pin "4") (pinfunction "1_4") (pintype "passive"))
    )
    (net (code "41") (name "/D3") (class "Default")
      (node (ref "CONN1") (pin "B11") (pinfunction "D3_B11") (pintype "bidirectional"))
      (node (ref "RN8") (pin "3") (pinfunction "1_3") (pintype "passive"))
    )
    (net (code "42") (name "/D4") (class "Default")
      (node (ref "CONN1") (pin "B12") (pinfunction "D4_B12") (pintype "bidirectional"))
      (node (ref "RN8") (pin "4") (pinfunction "1_4") (pintype "passive"))
    )
    (net (code "43") (name "/D5") (class "Default")
      (node (ref "CONN1") (pin "B10") (pinfunction "D5_B10") (pintype "bidirectional"))
      (node (ref "RN8") (pin "2") (pinfunction "1_2") (pintype "passive"))
    )
    (net (code "44") (name "/D6") (class "Default")
      (node (ref "CONN1") (pin "B9") (pinfunction "D6_B9") (pintype "bidirectional"))
      (node (ref "RN8") (pin "1") (pinfunction "1_1") (pintype "passive"))
    )
    (net (code "45") (name "/D7") (class "Default")
      (node (ref "CONN1") (pin "B3") (pinfunction "D7_B3") (pintype "bidirectional"))
      (node (ref "RN7") (pin "1") (pinfunction "1_1") (pintype "passive"))
    )
    (net (code "46") (name "/DM") (class "Default")
      (node (ref "R36") (pin "2") (pinfunction "2_2") (pintype "passive"))
      (node (ref "R43") (pin "2") (pinfunction "2_2") (pintype "passive"))
      (node (ref "TV26") (pin "3") (pinfunction "B_3") (pintype "bidirectional"))
      (node (ref "USB2") (pin "D-") (pinfunction "D-_D-") (pintype "bidirectional"))
    )
    (net (code "47") (name "/DP") (class "Default")
      (node (ref "R35") (pin "2") (pinfunction "2_2") (pintype "passive"))
      (node (ref "R57") (pin "2") (pinfunction "2_2") (pintype "passive"))
      (node (ref "TV26") (pin "2") (pinfunction "A_2") (pintype "bidirectional"))
      (node (ref "USB2") (pin "D+") (pinfunction "D+_D+") (pintype "bidirectional"))
    )
    (net (code "48") (name "/D_BUS_DIR") (class "Default")
      (node (ref "IC2") (pin "11") (pinfunction "__IO_8_11") (pintype "bidirectional"))
      (node (ref "IC4") (pin "1") (pinfunction "DIR_1") (pintype "input"))
    )
    (net (code "49") (name "/D_BUS_OE") (class "Default")
      (node (ref "IC2") (pin "7") (pinfunction "__IO_5_7") (pintype "bidirectional"))
      (node (ref "IC4") (pin "19") (pinfunction "G_19") (pintype "input"))
      (node (ref "R24") (pin "2") (pinfunction "2_2") (pintype "passive"))
    )
    (net (code "50") (name "/ESP_EN") (class "Default")
      (node (ref "C1") (pin "2") (pinfunction "2_2") (pintype "passive"))
      (node (ref "R2") (pin "1") (pinfunction "1_1") (pintype "passive"))
      (node (ref "S1") (pin "B2") (pinfunction "2_B2") (pintype "passive"))
      (node (ref "U$3") (pin "1") (pinfunction "PA4_1") (pintype "passive"))
      (node (ref "U1") (pin "3") (pinfunction "EN_3") (pintype "bidirectional"))
    )
    (net (code "51") (name "/ESP_IO0") (class "Default")
      (node (ref "C2") (pin "2") (pinfunction "2_2") (pintype "passive"))
      (node (ref "R3") (pin "1") (pinfunction "1_1") (pintype "passive"))
      (node (ref "S2") (pin "B2") (pinfunction "2_B2") (pintype "passive"))
      (node (ref "U$3") (pin "3") (pinfunction "PA6_3") (pintype "passive"))
      (node (ref "U1") (pin "25") (pinfunction "IO0_25") (pintype "bidirectional"))
    )
    (net (code "52") (name "/ESP_IO26") (class "Default")
      (node (ref "IC2") (pin "138") (pinfunction "__IO_80_138") (pintype "bidirectional"))
      (node (ref "U1") (pin "11") (pinfunction "IO26_11") (pintype "bidirectional"))
    )
    (net (code "53") (name "/ESP_IO27") (class "Default")
      (node (ref "IC2") (pin "141") (pinfunction "__IO_81_141") (pintype "bidirectional"))
      (node (ref "U1") (pin "12") (pinfunction "IO27_12") (pintype "bidirectional"))
    )
    (net (code "54") (name "/ESP_MISO") (class "Default")
      (node (ref "IC2") (pin "6") (pinfunction "__IO_4/DATA/ADSO_6") (pintype "bidirectional"))
      (node (ref "U1") (pin "31") (pinfunction "IO19_31") (pintype "bidirectional"))
    )
    (net (code "55") (name "/ESP_MOSI") (class "Default")
      (node (ref "IC2") (pin "13") (pinfunction "__DATA0_13") (pintype "bidirectional"))
      (node (ref "U1") (pin "37") (pinfunction "IO23_37") (pintype "bidirectional"))
    )
    (net (code "56") (name "/ESP_NCS0") (class "Default")
      (node (ref "IC2") (pin "3") (pinfunction "__IO_3_3") (pintype "bidirectional"))
      (node (ref "U1") (pin "29") (pinfunction "IO5_29") (pintype "bidirectional"))
    )
    (net (code "57") (name "/ESP_QDH") (class "Default")
      (node (ref "IC2") (pin "1") (pinfunction "__IO_1_1") (pintype "bidirectional"))
      (node (ref "U1") (pin "33") (pinfunction "IO21_33") (pintype "bidirectional"))
    )
    (net (code "58") (name "/ESP_QWP") (class "Default")
      (node (ref "IC2") (pin "143") (pinfunction "__IO_83_143") (pintype "bidirectional"))
      (node (ref "U1") (pin "36") (pinfunction "IO22_36") (pintype "bidirectional"))
    )
    (net (code "59") (name "/ESP_RX") (class "Default")
      (node (ref "IC7") (pin "6") (pinfunction "TX_6") (pintype "output"))
      (node (ref "U$3") (pin "6") (pinfunction "PA3_6") (pintype "passive"))
      (node (ref "U1") (pin "34") (pinfunction "RXD0_34") (pintype "bidirectional"))
    )
    (net (code "60") (name "/ESP_SCK") (class "Default")
      (node (ref "IC2") (pin "12") (pinfunction "__DCLK_12") (pintype "input"))
      (node (ref "IC2") (pin "23") (pinfunction "__CLK1_23") (pintype "input"))
      (node (ref "U1") (pin "30") (pinfunction "IO18_30") (pintype "bidirectional"))
    )
    (net (code "61") (name "/ESP_TX") (class "Default")
      (node (ref "IC7") (pin "7") (pinfunction "RX_7") (pintype "input"))
      (node (ref "U1") (pin "35") (pinfunction "TXD0_35") (pintype "bidirectional"))
    )
    (net (code "62") (name "/ETHID") (class "Default")
      (node (ref "R71") (pin "1") (pinfunction "1_1") (pintype "passive"))
      (node (ref "U$10") (pin "A4") (pinfunction "E13_A4") (pintype "bidirectional"))
      (node (ref "U$11") (pin "3") (pinfunction "PA6_3") (pintype "passive"))
    )
    (net (code "63") (name "/ETH_CLK") (class "Default")
      (node (ref "IC14") (pin "5") (pinfunction "XTAL1/CLKIN_5") (pintype "bidirectional"))
      (node (ref "R81") (pin "2") (pinfunction "2_2") (pintype "passive"))
    )
    (net (code "64") (name "/ETH_CRS_DV") (class "Default")
      (node (ref "IC14") (pin "11") (pinfunction "CRS_DV/MODE2_11") (pintype "bidirectional"))
      (node (ref "U$10") (pin "B7") (pinfunction "E3_B7") (pintype "bidirectional"))
    )
    (net (code "65") (name "/ETH_MDC") (class "Default")
      (node (ref "IC14") (pin "13") (pinfunction "MDC_13") (pintype "bidirectional"))
      (node (ref "R79") (pin "1") (pinfunction "1_1") (pintype "passive"))
      (node (ref "U$10") (pin "A8") (pinfunction "E9_A8") (pintype "bidirectional"))
    )
    (net (code "66") (name "/ETH_MDIO") (class "Default")
      (node (ref "IC14") (pin "12") (pinfunction "MDIO_12") (pintype "bidirectional"))
      (node (ref "R80") (pin "1") (pinfunction "1_1") (pintype "passive"))
      (node (ref "U$10") (pin "A7") (pinfunction "E10_A7") (pintype "bidirectional"))
    )
    (net (code "67") (name "/ETH_NRST") (class "Default")
      (node (ref "IC14") (pin "15") (pinfunction "NRST_15") (pintype "bidirectional"))
      (node (ref "R78") (pin "1") (pinfunction "1_1") (pintype "passive"))
      (node (ref "U$10") (pin "A9") (pinfunction "E8_A9") (pintype "bidirectional"))
    )
    (net (code "68") (name "/ETH_REF_CLK") (class "Default")
      (node (ref "IC14") (pin "14") (pinfunction "NINT/REFCLK0_14") (pintype "bidirectional"))
      (node (ref "U$10") (pin "B8") (pinfunction "E4_B8") (pintype "bidirectional"))
    )
    (net (code "69") (name "/ETH_RXD0") (class "Default")
      (node (ref "IC14") (pin "8") (pinfunction "RXD0/MODE0_8") (pintype "bidirectional"))
      (node (ref "U$10") (pin "B6") (pinfunction "E2_B6") (pintype "bidirectional"))
    )
    (net (code "70") (name "/ETH_RXD1") (class "Default")
      (node (ref "IC14") (pin "7") (pinfunction "RXD1/MODE1_7") (pintype "bidirectional"))
      (node (ref "U$10") (pin "B5") (pinfunction "E1_B5") (pintype "bidirectional"))
    )
    (net (code "71") (name "/ETH_RXERR") (class "Default")
      (node (ref "IC14") (pin "10") (pinfunction "RXERR/PHYAD0_10") (pintype "bidirectional"))
      (node (ref "U$10") (pin "A6") (pinfunction "E11_A6") (pintype "bidirectional"))
    )
    (net (code "72") (name "/ETH_TXD0") (class "Default")
      (node (ref "IC14") (pin "17") (pinfunction "TXD0_17") (pintype "bidirectional"))
      (node (ref "U$10") (pin "A10") (pinfunction "E7_A10") (pintype "bidirectional"))
    )
    (net (code "73") (name "/ETH_TXD1") (class "Default")
      (node (ref "IC14") (pin "18") (pinfunction "TXD1_18") (pintype "bidirectional"))
      (node (ref "U$10") (pin "B10") (pinfunction "E6_B10") (pintype "bidirectional"))
    )
    (net (code "74") (name "/ETH_TX_EN") (class "Default")
      (node (ref "IC14") (pin "16") (pinfunction "TXEN_16") (pintype "bidirectional"))
      (node (ref "U$10") (pin "B9") (pinfunction "E5_B9") (pintype "bidirectional"))
    )
    (net (code "75") (name "/EXT0") (class "Default")
      (node (ref "IC2") (pin "135") (pinfunction "__IO_77_135") (pintype "bidirectional"))
      (node (ref "U$5") (pin "B4") (pinfunction "E0_B4") (pintype "bidirectional"))
      (node (ref "U$7") (pin "3") (pinfunction "3_3") (pintype "passive"))
    )
    (net (code "76") (name "/EXT1") (class "Default")
      (node (ref "IC2") (pin "133") (pinfunction "__IO_76_133") (pintype "bidirectional"))
      (node (ref "U$5") (pin "B5") (pinfunction "E1_B5") (pintype "bidirectional"))
      (node (ref "U$7") (pin "4") (pinfunction "4_4") (pintype "passive"))
    )
    (net (code "77") (name "/EXT2") (class "Default")
      (node (ref "IC2") (pin "128") (pinfunction "__IO_73_128") (pintype "bidirectional"))
      (node (ref "U$5") (pin "B6") (pinfunction "E2_B6") (pintype "bidirectional"))
      (node (ref "U$7") (pin "5") (pinfunction "5_5") (pintype "passive"))
    )
    (net (code "78") (name "/EXT3") (class "Default")
      (node (ref "IC2") (pin "127") (pinfunction "__IO_72_127") (pintype "bidirectional"))
      (node (ref "U$5") (pin "B7") (pinfunction "E3_B7") (pintype "bidirectional"))
      (node (ref "U$7") (pin "6") (pinfunction "6_6") (pintype "passive"))
    )
    (net (code "79") (name "/EXT4") (class "Default")
      (node (ref "IC2") (pin "126") (pinfunction "__IO_71_126") (pintype "bidirectional"))
      (node (ref "U$5") (pin "B8") (pinfunction "E4_B8") (pintype "bidirectional"))
      (node (ref "U$7") (pin "7") (pinfunction "7_7") (pintype "passive"))
    )
    (net (code "80") (name "/EXT5") (class "Default")
      (node (ref "IC2") (pin "125") (pinfunction "__IO_70_125") (pintype "bidirectional"))
      (node (ref "U$5") (pin "B9") (pinfunction "E5_B9") (pintype "bidirectional"))
      (node (ref "U$7") (pin "8") (pinfunction "8_8") (pintype "passive"))
    )
    (net (code "81") (name "/EXT6") (class "Default")
      (node (ref "IC2") (pin "124") (pinfunction "__IO_69_124") (pintype "bidirectional"))
      (node (ref "U$5") (pin "B10") (pinfunction "E6_B10") (pintype "bidirectional"))
      (node (ref "U$7") (pin "9") (pinfunction "9_9") (pintype "passive"))
    )
    (net (code "82") (name "/EXT7") (class "Default")
      (node (ref "IC2") (pin "121") (pinfunction "__IO_68_121") (pintype "bidirectional"))
      (node (ref "U$5") (pin "A10") (pinfunction "E7_A10") (pintype "bidirectional"))
      (node (ref "U$7") (pin "10") (pinfunction "10_10") (pintype "passive"))
    )
    (net (code "83") (name "/EXT8") (class "Default")
      (node (ref "IC2") (pin "114") (pinfunction "__IO_64_114") (pintype "bidirectional"))
      (node (ref "U$5") (pin "A9") (pinfunction "E8_A9") (pintype "bidirectional"))
    )
    (net (code "84") (name "/EXT9") (class "Default")
      (node (ref "IC2") (pin "115") (pinfunction "__IO_65_115") (pintype "bidirectional"))
      (node (ref "U$5") (pin "A8") (pinfunction "E9_A8") (pintype "bidirectional"))
    )
    (net (code "85") (name "/EXT10") (class "Default")
      (node (ref "IC2") (pin "119") (pinfunction "__IO_66_119") (pintype "bidirectional"))
      (node (ref "U$5") (pin "A7") (pinfunction "E10_A7") (pintype "bidirectional"))
    )
    (net (code "86") (name "/EXT11") (class "Default")
      (node (ref "IC2") (pin "120") (pinfunction "__IO_67_120") (pintype "bidirectional"))
      (node (ref "U$5") (pin "A6") (pinfunction "E11_A6") (pintype "bidirectional"))
    )
    (net (code "87") (name "/EXT12") (class "Default")
      (node (ref "IC2") (pin "142") (pinfunction "__IO_82_142") (pintype "bidirectional"))
      (node (ref "U$5") (pin "A5") (pinfunction "E12_A5") (pintype "bidirectional"))
    )
    (net (code "88") (name "/EXT13") (class "Default")
      (node (ref "IC2") (pin "144") (pinfunction "__IO_84_144") (pintype "bidirectional"))
      (node (ref "U$5") (pin "A4") (pinfunction "E13_A4") (pintype "bidirectional"))
    )
    (net (code "89") (name "/EXTID") (class "Default")
      (node (ref "JP1") (pin "8") (pinfunction "8_8") (pintype "passive"))
      (node (ref "R70") (pin "1") (pinfunction "1_1") (pintype "passive"))
      (node (ref "U$2") (pin "A4") (pinfunction "E13_A4") (pintype "bidirectional"))
    )
    (net (code "90") (name "/FLED0") (class "Default")
      (node (ref "IC2") (pin "76") (pinfunction "__IO_44_76") (pintype "bidirectional"))
      (node (ref "R41") (pin "2") (pinfunction "2_2") (pintype "passive"))
    )
    (net (code "91") (name "/FLED1") (class "Default")
      (node (ref "IC2") (pin "77") (pinfunction "__IO_45_77") (pintype "bidirectional"))
      (node (ref "R40") (pin "2") (pinfunction "2_2") (pintype "passive"))
    )
    (net (code "92") (name "/FLED2") (class "Default")
      (node (ref "IC2") (pin "80") (pinfunction "__IO_46_80") (pintype "bidirectional"))
      (node (ref "R39") (pin "2") (pinfunction "2_2") (pintype "passive"))
    )
    (net (code "93") (name "/FORCE_INT") (class "Default")
      (node (ref "IC2") (pin "53") (pinfunction "__IO_26_53") (pintype "bidirectional"))
      (node (ref "Q2") (pin "1") (pinfunction "G_1") (pintype "passive"))
    )
    (net (code "94") (name "/FORCE_IORQULA") (class "Default")
      (node (ref "IC2") (pin "136") (pinfunction "__IO_78_136") (pintype "bidirectional"))
      (node (ref "Q4") (pin "2") (pinfunction "G_2") (pintype "passive"))
    )
    (net (code "95") (name "/FORCE_NMI") (class "Default")
      (node (ref "IC2") (pin "137") (pinfunction "__IO_79_137") (pintype "bidirectional"))
      (node (ref "Q6") (pin "1") (pinfunction "G_1") (pintype "passive"))
    )
    (net (code "96") (name "/FORCE_RESET") (class "Default")
      (node (ref "IC2") (pin "67") (pinfunction "__IO_35_67") (pintype "bidirectional"))
      (node (ref "Q1") (pin "1") (pinfunction "G_1") (pintype "passive"))
    )
    (net (code "97") (name "/FORCE_ROMCS") (class "Default")
      (node (ref "IC2") (pin "132") (pinfunction "__IO_75_132") (pintype "bidirectional"))
      (node (ref "Q3") (pin "2") (pinfunction "G_2") (pintype "passive"))
    )
    (net (code "98") (name "/FR1") (class "Default")
      (node (ref "Q3") (pin "5") (pinfunction "G_5") (pintype "passive"))
      (node (ref "Q3") (pin "6") (pinfunction "D_6") (pintype "passive"))
      (node (ref "Q5") (pin "1") (pinfunction "G_1") (pintype "passive"))
      (node (ref "R5") (pin "2") (pinfunction "2_2") (pintype "passive"))
    )
    (net (code "99") (name "/FR2") (class "Default")
      (node (ref "Q4") (pin "5") (pinfunction "G_5") (pintype "passive"))
      (node (ref "Q4") (pin "6") (pinfunction "D_6") (pintype "passive"))
      (node (ref "R42") (pin "2") (pinfunction "2_2") (pintype "passive"))
    )
    (net (code "100") (name "/GREEN") (class "Default")
      (node (ref "R49") (pin "2") (pinfunction "2_2") (pintype "passive"))
      (node (ref "R53") (pin "2") (pinfunction "2_2") (pintype "passive"))
      (node (ref "R54") (pin "2") (pinfunction "2_2") (pintype "passive"))
      (node (ref "R59") (pin "2") (pinfunction "2_2") (pintype "passive"))
      (node (ref "X1") (pin "2") (pinfunction "2_2") (pintype "passive"))
    )
    (net (code "101") (name "/GREEN0") (class "Default")
      (node (ref "R53") (pin "1") (pinfunction "1_1") (pintype "passive"))
      (node (ref "U$8") (pin "B9") (pinfunction "E5_B9") (pintype "bidirectional"))
    )
    (net (code "102") (name "/GREEN1") (class "Default")
      (node (ref "R54") (pin "1") (pinfunction "1_1") (pintype "passive"))
      (node (ref "U$8") (pin "B8") (pinfunction "E4_B8") (pintype "bidirectional"))
    )
    (net (code "103") (name "/GREEN2") (class "Default")
      (node (ref "R59") (pin "1") (pinfunction "1_1") (pintype "passive"))
      (node (ref "U$8") (pin "A7") (pinfunction "E10_A7") (pintype "bidirectional"))
    )
    (net (code "104") (name "/HSYNC") (class "Default")
      (node (ref "R47") (pin "1") (pinfunction "1_1") (pintype "passive"))
      (node (ref "U$8") (pin "B4") (pinfunction "E0_B4") (pintype "bidirectional"))
    )
    (net (code "105") (name "/INT") (class "Default")
      (node (ref "CONN1") (pin "B13") (pinfunction "INT_B13") (pintype "bidirectional"))
      (node (ref "Q2") (pin "3") (pinfunction "D_3") (pintype "passive"))
      (node (ref "RN1") (pin "2") (pinfunction "1_2") (pintype "passive"))
    )
    (net (code "106") (name "/IORQ") (class "Default")
      (node (ref "CONN1") (pin "B17") (pinfunction "IORQ_B17") (pintype "bidirectional"))
      (node (ref "RN1") (pin "4") (pinfunction "1_4") (pintype "passive"))
    )
    (net (code "107") (name "/IORQULA") (class "Default")
      (node (ref "CONN1") (pin "A13") (pinfunction "IORQULA_A13") (pintype "bidirectional"))
      (node (ref "Q4") (pin "3") (pinfunction "D_3") (pintype "passive"))
    )
    (net (code "108") (name "/LED1") (class "Default")
      (node (ref "R21") (pin "2") (pinfunction "2_2") (pintype "passive"))
      (node (ref "U1") (pin "8") (pinfunction "IO32_8") (pintype "bidirectional"))
    )
    (net (code "109") (name "/LED2") (class "Default")
      (node (ref "IC2") (pin "2") (pinfunction "__IO_2_2") (pintype "bidirectional"))
      (node (ref "R22") (pin "2") (pinfunction "2_2") (pintype "passive"))
    )
    (net (code "110") (name "/LL") (class "Default")
      (node (ref "C62") (pin "2") (pinfunction "2_2") (pintype "passive"))
      (node (ref "R66") (pin "1") (pinfunction "1_1") (pintype "passive"))
      (node (ref "U$9") (pin "2") (pinfunction "TIP_2") (pintype "bidirectional"))
    )
    (net (code "111") (name "/LR") (class "Default")
      (node (ref "C55") (pin "2") (pinfunction "2_2") (pintype "passive"))
      (node (ref "R63") (pin "1") (pinfunction "1_1") (pintype "passive"))
      (node (ref "U$9") (pin "3") (pinfunction "RING_3") (pintype "bidirectional"))
    )
    (net (code "112") (name "/M1") (class "Default")
      (node (ref "CONN1") (pin "B24") (pinfunction "M1_B24") (pintype "bidirectional"))
      (node (ref "RN2") (pin "3") (pinfunction "1_3") (pintype "passive"))
    )
    (net (code "113") (name "/MREQ") (class "Default")
      (node (ref "CONN1") (pin "B16") (pinfunction "MREQ_B16") (pintype "bidirectional"))
      (node (ref "RN1") (pin "3") (pinfunction "1_3") (pintype "passive"))
    )
    (net (code "114") (name "/NC") (class "Default")
      (node (ref "U$10") (pin "A1") (pinfunction "+5V_A1") (pintype "power_in"))
    )
    (net (code "115") (name "/NCONFIG") (class "Default")
      (node (ref "IC2") (pin "14") (pinfunction "__NCONFIG_14") (pintype "bidirectional"))
      (node (ref "R7") (pin "1") (pinfunction "1_1") (pintype "passive"))
      (node (ref "U1") (pin "10") (pinfunction "IO25_10") (pintype "bidirectional"))
    )
    (net (code "116") (name "/NMI") (class "Default")
      (node (ref "CONN1") (pin "B14") (pinfunction "NMI_B14") (pintype "bidirectional"))
      (node (ref "Q6") (pin "3") (pinfunction "D_3") (pintype "passive"))
    )
    (net (code "117") (name "/NSTATUS") (class "Default")
      (node (ref "IC2") (pin "9") (pinfunction "__NSTATUS_9") (pintype "bidirectional"))
      (node (ref "R6") (pin "1") (pinfunction "1_1") (pintype "passive"))
      (node (ref "U1") (pin "27") (pinfunction "IO16_27") (pintype "bidirectional"))
    )
    (net (code "118") (name "/PEN1") (class "Default")
      (node (ref "IC1") (pin "4") (pinfunction "NEN_4") (pintype "input"))
      (node (ref "R37") (pin "1") (pinfunction "1_1") (pintype "passive"))
    )
    (net (code "119") (name "/PHY_LED0") (class "Default")
      (node (ref "IC14") (pin "3") (pinfunction "LED1/REGOFF_3") (pintype "bidirectional"))
      (node (ref "T1") (pin "12") (pinfunction "A_12") (pintype "passive"))
    )
    (net (code "120") (name "/PHY_LED1") (class "Default")
      (node (ref "IC14") (pin "2") (pinfunction "LED2/NINTSEL_2") (pintype "bidirectional"))
      (node (ref "T1") (pin "9") (pinfunction "A_9") (pintype "passive"))
    )
    (net (code "121") (name "/PULLUP_EN") (class "Default")
      (node (ref "R28") (pin "2") (pinfunction "2_2") (pintype "passive"))
      (node (ref "U$4") (pin "2") (pinfunction "G_2") (pintype "passive"))
      (node (ref "U$4") (pin "5") (pinfunction "G_5") (pintype "passive"))
      (node (ref "U1") (pin "9") (pinfunction "IO33_9") (pintype "bidirectional"))
    )
    (net (code "122") (name "/RAMCLK") (class "Default")
      (node (ref "IC2") (pin "84") (pinfunction "__IO_48_84") (pintype "bidirectional"))
      (node (ref "IC9") (pin "6") (pinfunction "SCK_6") (pintype "input"))
    )
    (net (code "123") (name "/RAMD0") (class "Default")
      (node (ref "IC2") (pin "83") (pinfunction "__IO_47_83") (pintype "bidirectional"))
      (node (ref "IC9") (pin "5") (pinfunction "SI/SIO[0]_5") (pintype "bidirectional"))
    )
    (net (code "124") (name "/RAMD1") (class "Default")
      (node (ref "IC2") (pin "87") (pinfunction "__IO_51_87") (pintype "bidirectional"))
      (node (ref "IC9") (pin "2") (pinfunction "SO/SIO[1]_2") (pintype "bidirectional"))
    )
    (net (code "125") (name "/RAMD2") (class "Default")
      (node (ref "IC2") (pin "86") (pinfunction "__IO_50_86") (pintype "bidirectional"))
      (node (ref "IC9") (pin "3") (pinfunction "SIO[2]_3") (pintype "bidirectional"))
    )
    (net (code "126") (name "/RAMD3") (class "Default")
      (node (ref "IC2") (pin "85") (pinfunction "__IO_49_85") (pintype "bidirectional"))
      (node (ref "IC9") (pin "7") (pinfunction "SIO[3]_7") (pintype "bidirectional"))
    )
    (net (code "127") (name "/RAMNCS") (class "Default")
      (node (ref "IC2") (pin "98") (pinfunction "__IO_52_98") (pintype "bidirectional"))
      (node (ref "IC9") (pin "1") (pinfunction "NCS_1") (pintype "input"))
    )
    (net (code "128") (name "/RCV") (class "Default")
      (node (ref "IC12") (pin "3") (pinfunction "RCV_3") (pintype "output"))
      (node (ref "IC2") (pin "103") (pinfunction "__IO_56_103") (pintype "bidirectional"))
    )
    (net (code "129") (name "/RD") (class "Default")
      (node (ref "CONN1") (pin "B18") (pinfunction "RD_B18") (pintype "bidirectional"))
      (node (ref "RN2") (pin "1") (pinfunction "1_1") (pintype "passive"))
    )
    (net (code "130") (name "/RED") (class "Default")
      (node (ref "R48") (pin "2") (pinfunction "2_2") (pintype "passive"))
      (node (ref "R51") (pin "2") (pinfunction "2_2") (pintype "passive"))
      (node (ref "R52") (pin "2") (pinfunction "2_2") (pintype "passive"))
      (node (ref "R58") (pin "2") (pinfunction "2_2") (pintype "passive"))
      (node (ref "X1") (pin "1") (pinfunction "1_1") (pintype "passive"))
    )
    (net (code "131") (name "/RED0") (class "Default")
      (node (ref "R51") (pin "1") (pinfunction "1_1") (pintype "passive"))
      (node (ref "U$8") (pin "B7") (pinfunction "E3_B7") (pintype "bidirectional"))
    )
    (net (code "132") (name "/RED1") (class "Default")
      (node (ref "R52") (pin "1") (pinfunction "1_1") (pintype "passive"))
      (node (ref "U$8") (pin "B6") (pinfunction "E2_B6") (pintype "bidirectional"))
    )
    (net (code "133") (name "/RED2") (class "Default")
      (node (ref "R58") (pin "1") (pinfunction "1_1") (pintype "passive"))
      (node (ref "U$8") (pin "A8") (pinfunction "E9_A8") (pintype "bidirectional"))
    )
    (net (code "134") (name "/RESET") (class "Default")
      (node (ref "CONN1") (pin "A20") (pinfunction "RESET_A20") (pintype "bidirectional"))
      (node (ref "Q1") (pin "3") (pinfunction "D_3") (pintype "passive"))
    )
    (net (code "135") (name "/RFSH") (class "Default")
      (node (ref "CONN1") (pin "B25") (pinfunction "RFSH_B25") (pintype "bidirectional"))
      (node (ref "RN2") (pin "4") (pinfunction "1_4") (pintype "passive"))
    )
    (net (code "136") (name "/ROMCS") (class "Default")
      (node (ref "CONN1") (pin "A25") (pinfunction "ROMCS_A25") (pintype "bidirectional"))
      (node (ref "Q3") (pin "3") (pinfunction "D_3") (pintype "passive"))
    )
    (net (code "137") (name "/RTS") (class "Default")
      (node (ref "IC7") (pin "4") (pinfunction "RTS_4") (pintype "output"))
      (node (ref "U$3") (pin "4") (pinfunction "PA5_4") (pintype "passive"))
    )
    (net (code "138") (name "/SDMMC_CK") (class "Default")
      (node (ref "R32") (pin "1") (pinfunction "1_1") (pintype "passive"))
      (node (ref "SD1") (pin "5") (pinfunction "CLK(SCLK)_5") (pintype "input"))
      (node (ref "U1") (pin "13") (pinfunction "IO14_13") (pintype "bidirectional"))
    )
    (net (code "139") (name "/SDMMC_CMD") (class "Default")
      (node (ref "R31") (pin "1") (pinfunction "1_1") (pintype "passive"))
      (node (ref "SD1") (pin "3") (pinfunction "CMD(DI)_3") (pintype "bidirectional"))
      (node (ref "U1") (pin "23") (pinfunction "IO15_23") (pintype "bidirectional"))
    )
    (net (code "140") (name "/SDMMC_D0") (class "Default")
      (node (ref "R33") (pin "2") (pinfunction "2_2") (pintype "passive"))
      (node (ref "R44") (pin "2") (pinfunction "2_2") (pintype "passive"))
      (node (ref "SD1") (pin "7") (pinfunction "DAT0(DO)_7") (pintype "bidirectional"))
      (node (ref "U1") (pin "24") (pinfunction "IO2_24") (pintype "bidirectional"))
    )
    (net (code "141") (name "/SDMMC_D1") (class "Default")
      (node (ref "R34") (pin "1") (pinfunction "1_1") (pintype "passive"))
      (node (ref "SD1") (pin "8") (pinfunction "DAT1_8") (pintype "bidirectional"))
      (node (ref "U1") (pin "26") (pinfunction "IO4_26") (pintype "bidirectional"))
    )
    (net (code "142") (name "/SDMMC_D2") (class "Default")
      (node (ref "R29") (pin "2") (pinfunction "2_2") (pintype "passive"))
      (node (ref "SD1") (pin "1") (pinfunction "DAT2_1") (pintype "bidirectional"))
      (node (ref "U1") (pin "14") (pinfunction "IO12_14") (pintype "bidirectional"))
    )
    (net (code "143") (name "/SDMMC_D3") (class "Default")
      (node (ref "R30") (pin "1") (pinfunction "1_1") (pintype "passive"))
      (node (ref "SD1") (pin "2") (pinfunction "CD/DAT3(~{CS})_2") (pintype "bidirectional"))
      (node (ref "U1") (pin "16") (pinfunction "IO13_16") (pintype "bidirectional"))
    )
    (net (code "144") (name "/SDMMC_DET") (class "Default")
      (node (ref "R1") (pin "2") (pinfunction "2_2") (pintype "passive"))
      (node (ref "SD1") (pin "A") (pinfunction "A_A") (pintype "passive"))
      (node (ref "U1") (pin "28") (pinfunction "IO17_28") (pintype "bidirectional"))
    )
    (net (code "145") (name "/SW1") (class "Default")
      (node (ref "C42") (pin "1") (pinfunction "1_1") (pintype "passive"))
      (node (ref "IC5") (pin "3") (pinfunction "SW_3") (pintype "passive"))
      (node (ref "L1") (pin "P$1") (pinfunction "1_P$1") (pintype "passive"))
    )
    (net (code "146") (name "/SW2") (class "Default")
      (node (ref "C43") (pin "1") (pinfunction "1_1") (pintype "passive"))
      (node (ref "IC6") (pin "3") (pinfunction "SW_3") (pintype "passive"))
      (node (ref "L2") (pin "P$1") (pinfunction "1_P$1") (pintype "passive"))
    )
    (net (code "147") (name "/SWITCH") (class "Default")
      (node (ref "R4") (pin "1") (pinfunction "1_1") (pintype "passive"))
      (node (ref "S3") (pin "B2") (pinfunction "2_B2") (pintype "passive"))
      (node (ref "U1") (pin "6") (pinfunction "IO34_6") (pintype "input"))
    )
    (net (code "148") (name "/TCK") (class "Default")
      (node (ref "IC2") (pin "16") (pinfunction "__TCK_16") (pintype "bidirectional"))
      (node (ref "J1") (pin "1") (pinfunction "1_1") (pintype "passive"))
      (node (ref "R10") (pin "1") (pinfunction "1_1") (pintype "passive"))
    )
    (net (code "149") (name "/TDI") (class "Default")
      (node (ref "IC2") (pin "15") (pinfunction "__TDI_15") (pintype "bidirectional"))
      (node (ref "J1") (pin "9") (pinfunction "9_9") (pintype "passive"))
    )
    (net (code "150") (name "/TDO") (class "Default")
      (node (ref "IC2") (pin "20") (pinfunction "__TDO_20") (pintype "bidirectional"))
      (node (ref "J1") (pin "3") (pinfunction "3_3") (pintype "passive"))
      (node (ref "R8") (pin "1") (pinfunction "1_1") (pintype "passive"))
    )
    (net (code "151") (name "/TMS") (class "Default")
      (node (ref "IC2") (pin "18") (pinfunction "__TMS_18") (pintype "bidirectional"))
      (node (ref "J1") (pin "5") (pinfunction "5_5") (pintype "passive"))
      (node (ref "R9") (pin "1") (pinfunction "1_1") (pintype "passive"))
    )
    (net (code "152") (name "/USB_FLT") (class "Default")
      (node (ref "IC1") (pin "3") (pinfunction "FAULT_3") (pintype "output"))
      (node (ref "IC2") (pin "112") (pinfunction "__IO_62_112") (pintype "bidirectional"))
      (node (ref "R38") (pin "1") (pinfunction "1_1") (pintype "passive"))
    )
    (net (code "153") (name "/USB_MODE") (class "Default")
      (node (ref "IC12") (pin "1") (pinfunction "MODE_1") (pintype "input"))
      (node (ref "IC2") (pin "105") (pinfunction "__IO_58_105") (pintype "bidirectional"))
    )
    (net (code "154") (name "/USB_OE") (class "Default")
      (node (ref "IC12") (pin "2") (pinfunction "OE_2") (pintype "input"))
      (node (ref "IC2") (pin "104") (pinfunction "__IO_57_104") (pintype "bidirectional"))
    )
    (net (code "155") (name "/USB_PWREN") (class "Default")
      (node (ref "IC2") (pin "113") (pinfunction "__IO_63_113") (pintype "bidirectional"))
      (node (ref "R37") (pin "2") (pinfunction "2_2") (pintype "passive"))
    )
    (net (code "156") (name "/USB_SPEED") (class "Default")
      (node (ref "IC12") (pin "9") (pinfunction "SPEED_9") (pintype "input"))
      (node (ref "IC2") (pin "106") (pinfunction "__IO_59_106") (pintype "bidirectional"))
    )
    (net (code "157") (name "/USB_SUSPEND") (class "Default")
      (node (ref "IC12") (pin "6") (pinfunction "SUSPND_6") (pintype "input"))
      (node (ref "IC2") (pin "99") (pinfunction "__IO_53_99") (pintype "bidirectional"))
    )
    (net (code "158") (name "/VBUS") (class "Default")
      (node (ref "C59") (pin "+") (pinfunction "+_+") (pintype "passive"))
      (node (ref "IC1") (pin "1") (pinfunction "VOUT_1") (pintype "power_in"))
      (node (ref "TV26") (pin "4") (pinfunction "C_4") (pintype "bidirectional"))
      (node (ref "USB2") (pin "VBUS") (pinfunction "VBUS_VBUS") (pintype "bidirectional"))
    )
    (net (code "159") (name "/VGAID") (class "Default")
      (node (ref "R69") (pin "1") (pinfunction "1_1") (pintype "passive"))
      (node (ref "U$6") (pin "3") (pinfunction "PA6_3") (pintype "passive"))
      (node (ref "U$8") (pin "A4") (pinfunction "E13_A4") (pintype "bidirectional"))
    )
    (net (code "160") (name "/VM") (class "Default")
      (node (ref "IC12") (pin "5") (pinfunction "VM_5") (pintype "output"))
      (node (ref "IC2") (pin "100") (pinfunction "__IO_54_100") (pintype "bidirectional"))
    )
    (net (code "161") (name "/VMO") (class "Default")
      (node (ref "IC12") (pin "13") (pinfunction "VMO_13") (pintype "input"))
      (node (ref "IC2") (pin "111") (pinfunction "__IO_61_111") (pintype "bidirectional"))
    )
    (net (code "162") (name "/VP") (class "Default")
      (node (ref "IC12") (pin "4") (pinfunction "VP_4") (pintype "output"))
      (node (ref "IC2") (pin "101") (pinfunction "__IO_55_101") (pintype "bidirectional"))
    )
    (net (code "163") (name "/VPO") (class "Default")
      (node (ref "IC12") (pin "12") (pinfunction "VPO_12") (pintype "input"))
      (node (ref "IC2") (pin "110") (pinfunction "__IO_60_110") (pintype "bidirectional"))
    )
    (net (code "164") (name "/VSYNC") (class "Default")
      (node (ref "R46") (pin "1") (pinfunction "1_1") (pintype "passive"))
      (node (ref "U$8") (pin "B5") (pinfunction "E1_B5") (pintype "bidirectional"))
    )
    (net (code "165") (name "/WR") (class "Default")
      (node (ref "CONN1") (pin "B19") (pinfunction "WR_B19") (pintype "bidirectional"))
      (node (ref "RN2") (pin "2") (pinfunction "1_2") (pintype "passive"))
    )
    (net (code "166") (name "/XCK") (class "Default")
      (node (ref "IC2") (pin "54") (pinfunction "__IO_27_54") (pintype "bidirectional"))
      (node (ref "IC3") (pin "18") (pinfunction "B1_18") (pintype "bidirectional"))
    )
    (net (code "167") (name "/XD0") (class "Default")
      (node (ref "IC2") (pin "43") (pinfunction "__IO_19_43") (pintype "bidirectional"))
      (node (ref "IC4") (pin "17") (pinfunction "B2_17") (pintype "bidirectional"))
    )
    (net (code "168") (name "/XD1") (class "Default")
      (node (ref "IC2") (pin "44") (pinfunction "__IO_20_44") (pintype "bidirectional"))
      (node (ref "IC4") (pin "16") (pinfunction "B3_16") (pintype "bidirectional"))
    )
    (net (code "169") (name "/XD2") (class "Default")
      (node (ref "IC2") (pin "46") (pinfunction "__IO_21_46") (pintype "bidirectional"))
      (node (ref "IC4") (pin "15") (pinfunction "B4_15") (pintype "bidirectional"))
    )
    (net (code "170") (name "/XD3") (class "Default")
      (node (ref "IC2") (pin "51") (pinfunction "__IO_24_51") (pintype "bidirectional"))
      (node (ref "IC4") (pin "12") (pinfunction "B7_12") (pintype "bidirectional"))
    )
    (net (code "171") (name "/XD4") (class "Default")
      (node (ref "IC2") (pin "52") (pinfunction "__IO_25_52") (pintype "bidirectional"))
      (node (ref "IC4") (pin "11") (pinfunction "B8_11") (pintype "bidirectional"))
    )
    (net (code "172") (name "/XD5") (class "Default")
      (node (ref "IC2") (pin "50") (pinfunction "__IO_23_50") (pintype "bidirectional"))
      (node (ref "IC4") (pin "13") (pinfunction "B6_13") (pintype "bidirectional"))
    )
    (net (code "173") (name "/XD6") (class "Default")
      (node (ref "IC2") (pin "49") (pinfunction "__IO_22_49") (pintype "bidirectional"))
      (node (ref "IC4") (pin "14") (pinfunction "B5_14") (pintype "bidirectional"))
    )
    (net (code "174") (name "/XD7") (class "Default")
      (node (ref "IC2") (pin "42") (pinfunction "__IO_18_42") (pintype "bidirectional"))
      (node (ref "IC4") (pin "18") (pinfunction "B1_18") (pintype "bidirectional"))
    )
    (net (code "175") (name "/XINT") (class "Default")
      (node (ref "IC2") (pin "55") (pinfunction "__IO_28_55") (pintype "bidirectional"))
      (node (ref "IC3") (pin "17") (pinfunction "B2_17") (pintype "bidirectional"))
    )
    (net (code "176") (name "/XIORQ") (class "Default")
      (node (ref "IC2") (pin "59") (pinfunction "__IO_30_59") (pintype "bidirectional"))
      (node (ref "IC3") (pin "15") (pinfunction "B4_15") (pintype "bidirectional"))
    )
    (net (code "177") (name "/XM1") (class "Default")
      (node (ref "IC2") (pin "65") (pinfunction "__IO_33_65") (pintype "bidirectional"))
      (node (ref "IC3") (pin "12") (pinfunction "B7_12") (pintype "bidirectional"))
    )
    (net (code "178") (name "/XMREQ") (class "Default")
      (node (ref "IC2") (pin "58") (pinfunction "__IO_29_58") (pintype "bidirectional"))
      (node (ref "IC3") (pin "16") (pinfunction "B3_16") (pintype "bidirectional"))
    )
    (net (code "179") (name "/XRD") (class "Default")
      (node (ref "IC2") (pin "60") (pinfunction "__IO_31_60") (pintype "bidirectional"))
      (node (ref "IC3") (pin "14") (pinfunction "B5_14") (pintype "bidirectional"))
    )
    (net (code "180") (name "/XRFSH") (class "Default")
      (node (ref "IC2") (pin "66") (pinfunction "__IO_34_66") (pintype "bidirectional"))
      (node (ref "IC3") (pin "11") (pinfunction "B8_11") (pintype "bidirectional"))
    )
    (net (code "181") (name "/XWR") (class "Default")
      (node (ref "IC2") (pin "64") (pinfunction "__IO_32_64") (pintype "bidirectional"))
      (node (ref "IC3") (pin "13") (pinfunction "B6_13") (pintype "bidirectional"))
    )
    (net (code "182") (name "/ZX_A0") (class "Default")
      (node (ref "IC10") (pin "14") (pinfunction "B5_14") (pintype "bidirectional"))
      (node (ref "IC2") (pin "33") (pinfunction "__IO_14_33") (pintype "bidirectional"))
    )
    (net (code "183") (name "/ZX_A1") (class "Default")
      (node (ref "IC10") (pin "13") (pinfunction "B6_13") (pintype "bidirectional"))
      (node (ref "IC2") (pin "34") (pinfunction "__IO_15_34") (pintype "bidirectional"))
    )
    (net (code "184") (name "/ZX_A2") (class "Default")
      (node (ref "IC10") (pin "12") (pinfunction "B7_12") (pintype "bidirectional"))
      (node (ref "IC2") (pin "38") (pinfunction "__IO_16_38") (pintype "bidirectional"))
    )
    (net (code "185") (name "/ZX_A3") (class "Default")
      (node (ref "IC10") (pin "11") (pinfunction "B8_11") (pintype "bidirectional"))
      (node (ref "IC2") (pin "39") (pinfunction "__IO_17_39") (pintype "bidirectional"))
    )
    (net (code "186") (name "/ZX_A4") (class "Default")
      (node (ref "IC11") (pin "15") (pinfunction "B4_15") (pintype "bidirectional"))
      (node (ref "IC2") (pin "71") (pinfunction "__IO_39_71") (pintype "bidirectional"))
    )
    (net (code "187") (name "/ZX_A5") (class "Default")
      (node (ref "IC11") (pin "16") (pinfunction "B3_16") (pintype "bidirectional"))
      (node (ref "IC2") (pin "70") (pinfunction "__IO_38_70") (pintype "bidirectional"))
    )
    (net (code "188") (name "/ZX_A6") (class "Default")
      (node (ref "IC11") (pin "17") (pinfunction "B2_17") (pintype "bidirectional"))
      (node (ref "IC2") (pin "69") (pinfunction "__IO_37_69") (pintype "bidirectional"))
    )
    (net (code "189") (name "/ZX_A7") (class "Default")
      (node (ref "IC11") (pin "18") (pinfunction "B1_18") (pintype "bidirectional"))
      (node (ref "IC2") (pin "68") (pinfunction "__IO_36_68") (pintype "bidirectional"))
    )
    (net (code "190") (name "/ZX_A8") (class "Default")
      (node (ref "IC11") (pin "14") (pinfunction "B5_14") (pintype "bidirectional"))
      (node (ref "IC2") (pin "72") (pinfunction "__IO_40_72") (pintype "bidirectional"))
    )
    (net (code "191") (name "/ZX_A9") (class "Default")
      (node (ref "IC11") (pin "13") (pinfunction "B6_13") (pintype "bidirectional"))
      (node (ref "IC2") (pin "73") (pinfunction "__IO_41_73") (pintype "bidirectional"))
    )
    (net (code "192") (name "/ZX_A10") (class "Default")
      (node (ref "IC11") (pin "12") (pinfunction "B7_12") (pintype "bidirectional"))
      (node (ref "IC2") (pin "74") (pinfunction "__IO_42_74") (pintype "bidirectional"))
    )
    (net (code "193") (name "/ZX_A11") (class "Default")
      (node (ref "IC11") (pin "11") (pinfunction "B8_11") (pintype "bidirectional"))
      (node (ref "IC2") (pin "75") (pinfunction "__IO_43_75") (pintype "bidirectional"))
    )
    (net (code "194") (name "/ZX_A12") (class "Default")
      (node (ref "IC10") (pin "15") (pinfunction "B4_15") (pintype "bidirectional"))
      (node (ref "IC2") (pin "32") (pinfunction "__IO_13_32") (pintype "bidirectional"))
    )
    (net (code "195") (name "/ZX_A13") (class "Default")
      (node (ref "IC10") (pin "16") (pinfunction "B3_16") (pintype "bidirectional"))
      (node (ref "IC2") (pin "31") (pinfunction "__IO_12_31") (pintype "bidirectional"))
    )
    (net (code "196") (name "/ZX_A14") (class "Default")
      (node (ref "IC10") (pin "17") (pinfunction "B2_17") (pintype "bidirectional"))
      (node (ref "IC2") (pin "30") (pinfunction "__IO_11_30") (pintype "bidirectional"))
    )
    (net (code "197") (name "/ZX_A15") (class "Default")
      (node (ref "IC10") (pin "18") (pinfunction "B1_18") (pintype "bidirectional"))
      (node (ref "IC2") (pin "28") (pinfunction "__IO_10_28") (pintype "bidirectional"))
    )
    (net (code "198") (name "GND") (class "Default")
      (node (ref "C1") (pin "1") (pinfunction "1_1") (pintype "passive"))
      (node (ref "C10") (pin "2") (pinfunction "2_2") (pintype "passive"))
      (node (ref "C100") (pin "2") (pinfunction "2_2") (pintype "passive"))
      (node (ref "C101") (pin "2") (pinfunction "2_2") (pintype "passive"))
      (node (ref "C11") (pin "2") (pinfunction "2_2") (pintype "passive"))
      (node (ref "C12") (pin "2") (pinfunction "2_2") (pintype "passive"))
      (node (ref "C13") (pin "2") (pinfunction "2_2") (pintype "passive"))
      (node (ref "C14") (pin "2") (pinfunction "2_2") (pintype "passive"))
      (node (ref "C15") (pin "2") (pinfunction "2_2") (pintype "passive"))
      (node (ref "C16") (pin "2") (pinfunction "2_2") (pintype "passive"))
      (node (ref "C17") (pin "2") (pinfunction "2_2") (pintype "passive"))
      (node (ref "C18") (pin "2") (pinfunction "2_2") (pintype "passive"))
      (node (ref "C19") (pin "2") (pinfunction "2_2") (pintype "passive"))
      (node (ref "C2") (pin "1") (pinfunction "1_1") (pintype "passive"))
      (node (ref "C20") (pin "2") (pinfunction "2_2") (pintype "passive"))
      (node (ref "C21") (pin "2") (pinfunction "2_2") (pintype "passive"))
      (node (ref "C22") (pin "2") (pinfunction "2_2") (pintype "passive"))
      (node (ref "C23") (pin "2") (pinfunction "2_2") (pintype "passive"))
      (node (ref "C24") (pin "2") (pinfunction "2_2") (pintype "passive"))
      (node (ref "C25") (pin "2") (pinfunction "2_2") (pintype "passive"))
      (node (ref "C26") (pin "2") (pinfunction "2_2") (pintype "passive"))
      (node (ref "C27") (pin "2") (pinfunction "2_2") (pintype "passive"))
      (node (ref "C28") (pin "2") (pinfunction "2_2") (pintype "passive"))
      (node (ref "C29") (pin "2") (pinfunction "2_2") (pintype "passive"))
      (node (ref "C3") (pin "2") (pinfunction "2_2") (pintype "passive"))
      (node (ref "C30") (pin "2") (pinfunction "2_2") (pintype "passive"))
      (node (ref "C31") (pin "1") (pinfunction "1_1") (pintype "passive"))
      (node (ref "C32") (pin "1") (pinfunction "1_1") (pintype "passive"))
      (node (ref "C33") (pin "1") (pinfunction "1_1") (pintype "passive"))
      (node (ref "C34") (pin "1") (pinfunction "1_1") (pintype "passive"))
      (node (ref "C35") (pin "1") (pinfunction "1_1") (pintype "passive"))
      (node (ref "C36") (pin "1") (pinfunction "1_1") (pintype "passive"))
      (node (ref "C37") (pin "2") (pinfunction "2_2") (pintype "passive"))
      (node (ref "C38") (pin "1") (pinfunction "1_1") (pintype "passive"))
      (node (ref "C39") (pin "1") (pinfunction "1_1") (pintype "passive"))
      (node (ref "C4") (pin "2") (pinfunction "2_2") (pintype "passive"))
      (node (ref "C40") (pin "2") (pinfunction "2_2") (pintype "passive"))
      (node (ref "C41") (pin "2") (pinfunction "2_2") (pintype "passive"))
      (node (ref "C45") (pin "1") (pinfunction "1_1") (pintype "passive"))
      (node (ref "C46") (pin "1") (pinfunction "1_1") (pintype "passive"))
      (node (ref "C47") (pin "1") (pinfunction "1_1") (pintype "passive"))
      (node (ref "C48") (pin "1") (pinfunction "1_1") (pintype "passive"))
      (node (ref "C49") (pin "1") (pinfunction "1_1") (pintype "passive"))
      (node (ref "C5") (pin "2") (pinfunction "2_2") (pintype "passive"))
      (node (ref "C50") (pin "2") (pinfunction "2_2") (pintype "passive"))
      (node (ref "C51") (pin "1") (pinfunction "1_1") (pintype "passive"))
      (node (ref "C52") (pin "2") (pinfunction "2_2") (pintype "passive"))
      (node (ref "C53") (pin "2") (pinfunction "2_2") (pintype "passive"))
      (node (ref "C54") (pin "1") (pinfunction "1_1") (pintype "passive"))
      (node (ref "C56") (pin "2") (pinfunction "2_2") (pintype "passive"))
      (node (ref "C57") (pin "MINUS") (pinfunction "-_MINUS") (pintype "passive"))
      (node (ref "C58") (pin "1") (pinfunction "1_1") (pintype "passive"))
      (node (ref "C59") (pin "-") (pinfunction "-_-") (pintype "passive"))
      (node (ref "C6") (pin "2") (pinfunction "2_2") (pintype "passive"))
      (node (ref "C60") (pin "MINUS") (pinfunction "-_MINUS") (pintype "passive"))
      (node (ref "C61") (pin "1") (pinfunction "1_1") (pintype "passive"))
      (node (ref "C63") (pin "1") (pinfunction "1_1") (pintype "passive"))
      (node (ref "C64") (pin "1") (pinfunction "1_1") (pintype "passive"))
      (node (ref "C65") (pin "MINUS") (pinfunction "-_MINUS") (pintype "passive"))
      (node (ref "C66") (pin "1") (pinfunction "1_1") (pintype "passive"))
      (node (ref "C7") (pin "2") (pinfunction "2_2") (pintype "passive"))
      (node (ref "C8") (pin "2") (pinfunction "2_2") (pintype "passive"))
      (node (ref "C9") (pin "2") (pinfunction "2_2") (pintype "passive"))
      (node (ref "C93") (pin "1") (pinfunction "1_1") (pintype "passive"))
      (node (ref "C94") (pin "1") (pinfunction "1_1") (pintype "passive"))
      (node (ref "C95") (pin "1") (pinfunction "1_1") (pintype "passive"))
      (node (ref "C96") (pin "1") (pinfunction "1_1") (pintype "passive"))
      (node (ref "C97") (pin "1") (pinfunction "1_1") (pintype "passive"))
      (node (ref "C98") (pin "1") (pinfunction "1_1") (pintype "passive"))
      (node (ref "C99") (pin "1") (pinfunction "1_1") (pintype "passive"))
      (node (ref "CONN1") (pin "A14") (pinfunction "GND_A14") (pintype "power_in"))
      (node (ref "CONN1") (pin "A6") (pinfunction "GND_A6") (pintype "power_in"))
      (node (ref "CONN1") (pin "A7") (pinfunction "GND_A7") (pintype "power_in"))
      (node (ref "IC1") (pin "2") (pinfunction "GND_2") (pintype "power_in"))
      (node (ref "IC10") (pin "10") (pinfunction "GND_10") (pintype "power_in"))
      (node (ref "IC11") (pin "10") (pinfunction "GND_10") (pintype "power_in"))
      (node (ref "IC12") (pin "7") (pinfunction "GND_7") (pintype "power_in"))
      (node (ref "IC13") (pin "2") (pinfunction "GND_2") (pintype "power_in"))
      (node (ref "IC14") (pin "P") (pinfunction "VSS_P") (pintype "bidirectional"))
      (node (ref "IC2") (pin "108") (pinfunction "__GNDA2_108") (pintype "power_in"))
      (node (ref "IC2") (pin "118") (pinfunction "__GND_12_118") (pintype "power_in"))
      (node (ref "IC2") (pin "123") (pinfunction "__GND_13_123") (pintype "power_in"))
      (node (ref "IC2") (pin "131") (pinfunction "__GND_14_131") (pintype "power_in"))
      (node (ref "IC2") (pin "140") (pinfunction "__GND_15_140") (pintype "power_in"))
      (node (ref "IC2") (pin "145") (pinfunction "TP_145") (pintype "bidirectional"))
      (node (ref "IC2") (pin "19") (pinfunction "__GND_2_19") (pintype "power_in"))
      (node (ref "IC2") (pin "21") (pinfunction "__NCE_21") (pintype "bidirectional"))
      (node (ref "IC2") (pin "22") (pinfunction "__GND_3_22") (pintype "power_in"))
      (node (ref "IC2") (pin "27") (pinfunction "__GND_4_27") (pintype "power_in"))
      (node (ref "IC2") (pin "36") (pinfunction "__GNDA1_36") (pintype "power_in"))
      (node (ref "IC2") (pin "4") (pinfunction "__GND_1_4") (pintype "power_in"))
      (node (ref "IC2") (pin "41") (pinfunction "__GND_5_41") (pintype "power_in"))
      (node (ref "IC2") (pin "48") (pinfunction "__GND_6_48") (pintype "power_in"))
      (node (ref "IC2") (pin "57") (pinfunction "__GND_7_57") (pintype "power_in"))
      (node (ref "IC2") (pin "63") (pinfunction "__GND_8_63") (pintype "power_in"))
      (node (ref "IC2") (pin "79") (pinfunction "__GND_9_79") (pintype "power_in"))
      (node (ref "IC2") (pin "82") (pinfunction "__GND_10_82") (pintype "power_in"))
      (node (ref "IC2") (pin "94") (pinfunction "__MSEL0_94") (pintype "bidirectional"))
      (node (ref "IC2") (pin "95") (pinfunction "__GND_11_95") (pintype "power_in"))
      (node (ref "IC2") (pin "96") (pinfunction "__MSEL1_96") (pintype "bidirectional"))
      (node (ref "IC3") (pin "10") (pinfunction "GND_10") (pintype "power_in"))
      (node (ref "IC4") (pin "10") (pinfunction "GND_10") (pintype "power_in"))
      (node (ref "IC5") (pin "4") (pinfunction "GND_4") (pintype "power_in"))
      (node (ref "IC6") (pin "4") (pinfunction "GND_4") (pintype "power_in"))
      (node (ref "IC7") (pin "3") (pinfunction "GND_3") (pintype "power_in"))
      (node (ref "IC8") (pin "2") (pinfunction "GND_2") (pintype "power_in"))
      (node (ref "IC9") (pin "4") (pinfunction "GND_4") (pintype "power_in"))
      (node (ref "J1") (pin "10") (pinfunction "10_10") (pintype "passive"))
      (node (ref "J1") (pin "2") (pinfunction "2_2") (pintype "passive"))
      (node (ref "JP1") (pin "3") (pinfunction "3_3") (pintype "passive"))
      (node (ref "JP1") (pin "4") (pinfunction "4_4") (pintype "passive"))
      (node (ref "Q1") (pin "2") (pinfunction "S_2") (pintype "passive"))
      (node (ref "Q2") (pin "2") (pinfunction "S_2") (pintype "passive"))
      (node (ref "Q3") (pin "1") (pinfunction "S_1") (pintype "passive"))
      (node (ref "Q4") (pin "1") (pinfunction "S_1") (pintype "passive"))
      (node (ref "Q6") (pin "2") (pinfunction "S_2") (pintype "passive"))
      (node (ref "R10") (pin "2") (pinfunction "2_2") (pintype "passive"))
      (node (ref "R17") (pin "1") (pinfunction "1_1") (pintype "passive"))
      (node (ref "R18") (pin "1") (pinfunction "1_1") (pintype "passive"))
      (node (ref "R23") (pin "2") (pinfunction "2_2") (pintype "passive"))
      (node (ref "R43") (pin "1") (pinfunction "1_1") (pintype "passive"))
      (node (ref "R44") (pin "1") (pinfunction "1_1") (pintype "passive"))
      (node (ref "R45") (pin "2") (pinfunction "2_2") (pintype "passive"))
      (node (ref "R48") (pin "1") (pinfunction "1_1") (pintype "passive"))
      (node (ref "R49") (pin "1") (pinfunction "1_1") (pintype "passive"))
      (node (ref "R50") (pin "1") (pinfunction "1_1") (pintype "passive"))
      (node (ref "R57") (pin "1") (pinfunction "1_1") (pintype "passive"))
      (node (ref "R62") (pin "2") (pinfunction "2_2") (pintype "passive"))
      (node (ref "R63") (pin "2") (pinfunction "2_2") (pintype "passive"))
      (node (ref "R65") (pin "2") (pinfunction "2_2") (pintype "passive"))
      (node (ref "R66") (pin "2") (pinfunction "2_2") (pintype "passive"))
      (node (ref "R82") (pin "1") (pinfunction "1_1") (pintype "passive"))
      (node (ref "R87") (pin "1") (pinfunction "1_1") (pintype "passive"))
      (node (ref "R88") (pin "1") (pinfunction "1_1") (pintype "passive"))
      (node (ref "S1") (pin "A2") (pinfunction "1_A2") (pintype "passive"))
      (node (ref "S2") (pin "A2") (pinfunction "1_A2") (pintype "passive"))
      (node (ref "S3") (pin "A2") (pinfunction "1_A2") (pintype "passive"))
      (node (ref "SD1") (pin "6") (pinfunction "VSS_6") (pintype "power_in"))
      (node (ref "SD1") (pin "B") (pinfunction "B_B") (pintype "passive"))
      (node (ref "SD1") (pin "MNT1") (pinfunction "S1_MNT1") (pintype "passive"))
      (node (ref "SD1") (pin "MNT2") (pinfunction "S2_MNT2") (pintype "passive"))
      (node (ref "SD1") (pin "MNT3") (pinfunction "S3_MNT3") (pintype "passive"))
      (node (ref "SD1") (pin "MNT4") (pinfunction "S4_MNT4") (pintype "passive"))
      (node (ref "TV26") (pin "1") (pinfunction "COM_1") (pintype "bidirectional"))
      (node (ref "U$1") (pin "2") (pinfunction "GND_2") (pintype "power_in"))
      (node (ref "U$10") (pin "A2") (pinfunction "GND_A2") (pintype "power_in"))
      (node (ref "U$10") (pin "B2") (pinfunction "GND_B2") (pintype "power_in"))
      (node (ref "U$11") (pin "2") (pinfunction "GND_2") (pintype "power_in"))
      (node (ref "U$2") (pin "A2") (pinfunction "GND_A2") (pintype "power_in"))
      (node (ref "U$2") (pin "B2") (pinfunction "GND_B2") (pintype "power_in"))
      (node (ref "U$3") (pin "2") (pinfunction "GND_2") (pintype "power_in"))
      (node (ref "U$5") (pin "A2") (pinfunction "GND_A2") (pintype "power_in"))
      (node (ref "U$5") (pin "B2") (pinfunction "GND_B2") (pintype "power_in"))
      (node (ref "U$6") (pin "2") (pinfunction "GND_2") (pintype "power_in"))
      (node (ref "U$7") (pin "2") (pinfunction "2_2") (pintype "passive"))
      (node (ref "U$8") (pin "A2") (pinfunction "GND_A2") (pintype "power_in"))
      (node (ref "U$8") (pin "B2") (pinfunction "GND_B2") (pintype "power_in"))
      (node (ref "U$9") (pin "1") (pinfunction "SLEEVE_1") (pintype "bidirectional"))
      (node (ref "U1") (pin "1") (pinfunction "GND_1") (pintype "bidirectional"))
      (node (ref "U1") (pin "15") (pinfunction "GND_15") (pintype "bidirectional"))
      (node (ref "U1") (pin "38") (pinfunction "GND_38") (pintype "bidirectional"))
      (node (ref "U1") (pin "GND") (pinfunction "GND_GND") (pintype "bidirectional"))
      (node (ref "USB1") (pin "P5") (pinfunction "GND_P5") (pintype "bidirectional"))
      (node (ref "USB2") (pin "GND") (pinfunction "GND_GND") (pintype "bidirectional"))
      (node (ref "X1") (pin "10") (pinfunction "10_10") (pintype "passive"))
      (node (ref "X1") (pin "5") (pinfunction "5_5") (pintype "passive"))
      (node (ref "X1") (pin "6") (pinfunction "6_6") (pintype "passive"))
      (node (ref "X1") (pin "7") (pinfunction "7_7") (pintype "passive"))
      (node (ref "X1") (pin "8") (pinfunction "8_8") (pintype "passive"))
    )
    (net (code "199") (name "Net-(C42-Pad2)") (class "Default")
      (node (ref "C42") (pin "2") (pinfunction "2_2") (pintype "passive"))
      (node (ref "R13") (pin "1") (pinfunction "1_1") (pintype "passive"))
    )
    (net (code "200") (name "Net-(C43-Pad2)") (class "Default")
      (node (ref "C43") (pin "2") (pinfunction "2_2") (pintype "passive"))
      (node (ref "R14") (pin "1") (pinfunction "1_1") (pintype "passive"))
    )
    (net (code "201") (name "Net-(C44-Pad1)") (class "Default")
      (node (ref "C44") (pin "1") (pinfunction "1_1") (pintype "passive"))
      (node (ref "R16") (pin "2") (pinfunction "2_2") (pintype "passive"))
      (node (ref "R18") (pin "2") (pinfunction "2_2") (pintype "passive"))
      (node (ref "R20") (pin "1") (pinfunction "1_1") (pintype "passive"))
    )
    (net (code "202") (name "Net-(C54-Pad2)") (class "Default")
      (node (ref "C54") (pin "2") (pinfunction "2_2") (pintype "passive"))
      (node (ref "C55") (pin "1") (pinfunction "1_1") (pintype "passive"))
      (node (ref "R61") (pin "1") (pinfunction "1_1") (pintype "passive"))
      (node (ref "R62") (pin "1") (pinfunction "1_1") (pintype "passive"))
    )
    (net (code "203") (name "Net-(C61-Pad2)") (class "Default")
      (node (ref "C61") (pin "2") (pinfunction "2_2") (pintype "passive"))
      (node (ref "C62") (pin "1") (pinfunction "1_1") (pintype "passive"))
      (node (ref "R64") (pin "1") (pinfunction "1_1") (pintype "passive"))
      (node (ref "R65") (pin "1") (pinfunction "1_1") (pintype "passive"))
    )
    (net (code "204") (name "Net-(C99-Pad2)") (class "Default")
      (node (ref "C99") (pin "2") (pinfunction "2_2") (pintype "passive"))
      (node (ref "L8") (pin "2") (pinfunction "2_2") (pintype "passive"))
      (node (ref "R83") (pin "2") (pinfunction "2_2") (pintype "passive"))
      (node (ref "R84") (pin "2") (pinfunction "2_2") (pintype "passive"))
      (node (ref "R85") (pin "2") (pinfunction "2_2") (pintype "passive"))
      (node (ref "R86") (pin "2") (pinfunction "2_2") (pintype "passive"))
    )
    (net (code "205") (name "Net-(C100-Pad1)") (class "Default")
      (node (ref "C100") (pin "1") (pinfunction "1_1") (pintype "passive"))
      (node (ref "T1") (pin "4") (pinfunction "4_4") (pintype "bidirectional"))
    )
    (net (code "206") (name "Net-(C101-Pad1)") (class "Default")
      (node (ref "C101") (pin "1") (pinfunction "1_1") (pintype "passive"))
      (node (ref "T1") (pin "5") (pinfunction "5_5") (pintype "bidirectional"))
    )
    (net (code "207") (name "Net-(CONN1-NC3)") (class "Default")
      (node (ref "CONN1") (pin "B4") (pinfunction "NC3_B4") (pintype "passive"))
      (node (ref "Q5") (pin "3") (pinfunction "D_3") (pintype "passive"))
    )
    (net (code "208") (name "Net-(IC2-__CLK2)") (class "Default")
      (node (ref "IC2") (pin "24") (pinfunction "__CLK2_24") (pintype "input"))
      (node (ref "U$1") (pin "3") (pinfunction "FO_3") (pintype "output"))
    )
    (net (code "209") (name "Net-(IC2-__IO_6{slash}FLASH_NCS{slash}NCSO)") (class "Default")
      (node (ref "IC2") (pin "8") (pinfunction "__IO_6/FLASH_NCS/NCSO_8") (pintype "bidirectional"))
      (node (ref "TP4") (pin "TP") (pinfunction "TP_TP") (pintype "input"))
    )
    (net (code "210") (name "Net-(IC3A-A1)") (class "Default")
      (node (ref "IC3") (pin "2") (pinfunction "A1_2") (pintype "bidirectional"))
      (node (ref "RN1") (pin "8") (pinfunction "2_8") (pintype "passive"))
    )
    (net (code "211") (name "Net-(IC3A-A2)") (class "Default")
      (node (ref "IC3") (pin "3") (pinfunction "A2_3") (pintype "bidirectional"))
      (node (ref "RN1") (pin "7") (pinfunction "2_7") (pintype "passive"))
    )
    (net (code "212") (name "Net-(IC3A-A3)") (class "Default")
      (node (ref "IC3") (pin "4") (pinfunction "A3_4") (pintype "bidirectional"))
      (node (ref "RN1") (pin "6") (pinfunction "2_6") (pintype "passive"))
    )
    (net (code "213") (name "Net-(IC3A-A4)") (class "Default")
      (node (ref "IC3") (pin "5") (pinfunction "A4_5") (pintype "bidirectional"))
      (node (ref "RN1") (pin "5") (pinfunction "2_5") (pintype "passive"))
    )
    (net (code "214") (name "Net-(IC3A-A5)") (class "Default")
      (node (ref "IC3") (pin "6") (pinfunction "A5_6") (pintype "bidirectional"))
      (node (ref "RN2") (pin "8") (pinfunction "2_8") (pintype "passive"))
    )
    (net (code "215") (name "Net-(IC3A-A6)") (class "Default")
      (node (ref "IC3") (pin "7") (pinfunction "A6_7") (pintype "bidirectional"))
      (node (ref "RN2") (pin "7") (pinfunction "2_7") (pintype "passive"))
    )
    (net (code "216") (name "Net-(IC3A-A7)") (class "Default")
      (node (ref "IC3") (pin "8") (pinfunction "A7_8") (pintype "bidirectional"))
      (node (ref "RN2") (pin "6") (pinfunction "2_6") (pintype "passive"))
    )
    (net (code "217") (name "Net-(IC3A-A8)") (class "Default")
      (node (ref "IC3") (pin "9") (pinfunction "A8_9") (pintype "bidirectional"))
      (node (ref "RN2") (pin "5") (pinfunction "2_5") (pintype "passive"))
    )
    (net (code "218") (name "Net-(IC4A-A1)") (class "Default")
      (node (ref "IC4") (pin "2") (pinfunction "A1_2") (pintype "bidirectional"))
      (node (ref "RN7") (pin "8") (pinfunction "2_8") (pintype "passive"))
    )
    (net (code "219") (name "Net-(IC4A-A2)") (class "Default")
      (node (ref "IC4") (pin "3") (pinfunction "A2_3") (pintype "bidirectional"))
      (node (ref "RN7") (pin "7") (pinfunction "2_7") (pintype "passive"))
    )
    (net (code "220") (name "Net-(IC4A-A3)") (class "Default")
      (node (ref "IC4") (pin "4") (pinfunction "A3_4") (pintype "bidirectional"))
      (node (ref "RN7") (pin "6") (pinfunction "2_6") (pintype "passive"))
    )
    (net (code "221") (name "Net-(IC4A-A4)") (class "Default")
      (node (ref "IC4") (pin "5") (pinfunction "A4_5") (pintype "bidirectional"))
      (node (ref "RN7") (pin "5") (pinfunction "2_5") (pintype "passive"))
    )
    (net (code "222") (name "Net-(IC4A-A5)") (class "Default")
      (node (ref "IC4") (pin "6") (pinfunction "A5_6") (pintype "bidirectional"))
      (node (ref "RN8") (pin "8") (pinfunction "2_8") (pintype "passive"))
    )
    (net (code "223") (name "Net-(IC4A-A6)") (class "Default")
      (node (ref "IC4") (pin "7") (pinfunction "A6_7") (pintype "bidirectional"))
      (node (ref "RN8") (pin "7") (pinfunction "2_7") (pintype "passive"))
    )
    (net (code "224") (name "Net-(IC4A-A7)") (class "Default")
      (node (ref "IC4") (pin "8") (pinfunction "A7_8") (pintype "bidirectional"))
      (node (ref "RN8") (pin "6") (pinfunction "2_6") (pintype "passive"))
    )
    (net (code "225") (name "Net-(IC4A-A8)") (class "Default")
      (node (ref "IC4") (pin "9") (pinfunction "A8_9") (pintype "bidirectional"))
      (node (ref "RN8") (pin "5") (pinfunction "2_5") (pintype "passive"))
    )
    (net (code "226") (name "Net-(IC5-BST)") (class "Default")
      (node (ref "IC5") (pin "5") (pinfunction "BST_5") (pintype "passive"))
      (node (ref "R13") (pin "2") (pinfunction "2_2") (pintype "passive"))
    )
    (net (code "227") (name "Net-(IC5-EN)") (class "Default")
      (node (ref "IC5") (pin "6") (pinfunction "EN_6") (pintype "input"))
      (node (ref "R11") (pin "1") (pinfunction "1_1") (pintype "passive"))
    )
    (net (code "228") (name "Net-(IC5-FB)") (class "Default")
      (node (ref "IC5") (pin "8") (pinfunction "FB_8") (pintype "passive"))
      (node (ref "R15") (pin "1") (pinfunction "1_1") (pintype "passive"))
    )
    (net (code "229") (name "Net-(IC5-SS)") (class "Default")
      (node (ref "C38") (pin "2") (pinfunction "2_2") (pintype "passive"))
      (node (ref "IC5") (pin "1") (pinfunction "SS_1") (pintype "passive"))
    )
    (net (code "230") (name "Net-(IC5-VCC)") (class "Default")
      (node (ref "C35") (pin "2") (pinfunction "2_2") (pintype "passive"))
      (node (ref "IC5") (pin "7") (pinfunction "VCC_7") (pintype "passive"))
    )
    (net (code "231") (name "Net-(IC6-BST)") (class "Default")
      (node (ref "IC6") (pin "5") (pinfunction "BST_5") (pintype "passive"))
      (node (ref "R14") (pin "2") (pinfunction "2_2") (pintype "passive"))
    )
    (net (code "232") (name "Net-(IC6-EN)") (class "Default")
      (node (ref "C58") (pin "2") (pinfunction "2_2") (pintype "passive"))
      (node (ref "IC6") (pin "6") (pinfunction "EN_6") (pintype "input"))
      (node (ref "R12") (pin "1") (pinfunction "1_1") (pintype "passive"))
    )
    (net (code "233") (name "Net-(IC6-FB)") (class "Default")
      (node (ref "IC6") (pin "8") (pinfunction "FB_8") (pintype "passive"))
      (node (ref "R16") (pin "1") (pinfunction "1_1") (pintype "passive"))
    )
    (net (code "234") (name "Net-(IC6-SS)") (class "Default")
      (node (ref "C39") (pin "2") (pinfunction "2_2") (pintype "passive"))
      (node (ref "IC6") (pin "1") (pinfunction "SS_1") (pintype "passive"))
    )
    (net (code "235") (name "Net-(IC6-VCC)") (class "Default")
      (node (ref "C36") (pin "2") (pinfunction "2_2") (pintype "passive"))
      (node (ref "IC6") (pin "7") (pinfunction "VCC_7") (pintype "passive"))
    )
    (net (code "236") (name "Net-(IC7-DM)") (class "Default")
      (node (ref "IC7") (pin "2") (pinfunction "DM_2") (pintype "passive"))
      (node (ref "USB1") (pin "P2") (pinfunction "D-_P2") (pintype "bidirectional"))
    )
    (net (code "237") (name "Net-(IC7-DP)") (class "Default")
      (node (ref "IC7") (pin "1") (pinfunction "DP_1") (pintype "passive"))
      (node (ref "USB1") (pin "P3") (pinfunction "D+_P3") (pintype "bidirectional"))
    )
    (net (code "238") (name "Net-(IC10A-A1)") (class "Default")
      (node (ref "IC10") (pin "2") (pinfunction "A1_2") (pintype "bidirectional"))
      (node (ref "RN3") (pin "8") (pinfunction "2_8") (pintype "passive"))
    )
    (net (code "239") (name "Net-(IC10A-A2)") (class "Default")
      (node (ref "IC10") (pin "3") (pinfunction "A2_3") (pintype "bidirectional"))
      (node (ref "RN3") (pin "7") (pinfunction "2_7") (pintype "passive"))
    )
    (net (code "240") (name "Net-(IC10A-A3)") (class "Default")
      (node (ref "IC10") (pin "4") (pinfunction "A3_4") (pintype "bidirectional"))
      (node (ref "RN3") (pin "6") (pinfunction "2_6") (pintype "passive"))
    )
    (net (code "241") (name "Net-(IC10A-A4)") (class "Default")
      (node (ref "IC10") (pin "5") (pinfunction "A4_5") (pintype "bidirectional"))
      (node (ref "RN3") (pin "5") (pinfunction "2_5") (pintype "passive"))
    )
    (net (code "242") (name "Net-(IC10A-A5)") (class "Default")
      (node (ref "IC10") (pin "6") (pinfunction "A5_6") (pintype "bidirectional"))
      (node (ref "RN4") (pin "8") (pinfunction "2_8") (pintype "passive"))
    )
    (net (code "243") (name "Net-(IC10A-A6)") (class "Default")
      (node (ref "IC10") (pin "7") (pinfunction "A6_7") (pintype "bidirectional"))
      (node (ref "RN4") (pin "7") (pinfunction "2_7") (pintype "passive"))
    )
    (net (code "244") (name "Net-(IC10A-A7)") (class "Default")
      (node (ref "IC10") (pin "8") (pinfunction "A7_8") (pintype "bidirectional"))
      (node (ref "RN4") (pin "6") (pinfunction "2_6") (pintype "passive"))
    )
    (net (code "245") (name "Net-(IC10A-A8)") (class "Default")
      (node (ref "IC10") (pin "9") (pinfunction "A8_9") (pintype "bidirectional"))
      (node (ref "RN4") (pin "5") (pinfunction "2_5") (pintype "passive"))
    )
    (net (code "246") (name "Net-(IC11A-A1)") (class "Default")
      (node (ref "IC11") (pin "2") (pinfunction "A1_2") (pintype "bidirectional"))
      (node (ref "RN5") (pin "8") (pinfunction "2_8") (pintype "passive"))
    )
    (net (code "247") (name "Net-(IC11A-A2)") (class "Default")
      (node (ref "IC11") (pin "3") (pinfunction "A2_3") (pintype "bidirectional"))
      (node (ref "RN5") (pin "7") (pinfunction "2_7") (pintype "passive"))
    )
    (net (code "248") (name "Net-(IC11A-A3)") (class "Default")
      (node (ref "IC11") (pin "4") (pinfunction "A3_4") (pintype "bidirectional"))
      (node (ref "RN5") (pin "6") (pinfunction "2_6") (pintype "passive"))
    )
    (net (code "249") (name "Net-(IC11A-A4)") (class "Default")
      (node (ref "IC11") (pin "5") (pinfunction "A4_5") (pintype "bidirectional"))
      (node (ref "RN5") (pin "5") (pinfunction "2_5") (pintype "passive"))
    )
    (net (code "250") (name "Net-(IC11A-A5)") (class "Default")
      (node (ref "IC11") (pin "6") (pinfunction "A5_6") (pintype "bidirectional"))
      (node (ref "RN6") (pin "8") (pinfunction "2_8") (pintype "passive"))
    )
    (net (code "251") (name "Net-(IC11A-A6)") (class "Default")
      (node (ref "IC11") (pin "7") (pinfunction "A6_7") (pintype "bidirectional"))
      (node (ref "RN6") (pin "7") (pinfunction "2_7") (pintype "passive"))
    )
    (net (code "252") (name "Net-(IC11A-A7)") (class "Default")
      (node (ref "IC11") (pin "8") (pinfunction "A7_8") (pintype "bidirectional"))
      (node (ref "RN6") (pin "6") (pinfunction "2_6") (pintype "passive"))
    )
    (net (code "253") (name "Net-(IC11A-A8)") (class "Default")
      (node (ref "IC11") (pin "9") (pinfunction "A8_9") (pintype "bidirectional"))
      (node (ref "RN6") (pin "5") (pinfunction "2_5") (pintype "passive"))
    )
    (net (code "254") (name "Net-(IC12-DM)") (class "Default")
      (node (ref "IC12") (pin "10") (pinfunction "DM_10") (pintype "bidirectional"))
      (node (ref "R36") (pin "1") (pinfunction "1_1") (pintype "passive"))
    )
    (net (code "255") (name "Net-(IC12-DP)") (class "Default")
      (node (ref "IC12") (pin "11") (pinfunction "DP_11") (pintype "bidirectional"))
      (node (ref "R35") (pin "1") (pinfunction "1_1") (pintype "passive"))
    )
    (net (code "256") (name "Net-(IC14-RBIAS)") (class "Default")
      (node (ref "IC14") (pin "24") (pinfunction "RBIAS_24") (pintype "bidirectional"))
      (node (ref "R82") (pin "2") (pinfunction "2_2") (pintype "passive"))
    )
    (net (code "257") (name "Net-(IC14-RXN)") (class "Default")
      (node (ref "IC14") (pin "22") (pinfunction "RXN_22") (pintype "bidirectional"))
      (node (ref "R86") (pin "1") (pinfunction "1_1") (pintype "passive"))
      (node (ref "T1") (pin "6") (pinfunction "6_6") (pintype "bidirectional"))
    )
    (net (code "258") (name "Net-(IC14-RXP)") (class "Default")
      (node (ref "IC14") (pin "23") (pinfunction "RXP_23") (pintype "bidirectional"))
      (node (ref "R85") (pin "1") (pinfunction "1_1") (pintype "passive"))
      (node (ref "T1") (pin "3") (pinfunction "3_3") (pintype "bidirectional"))
    )
    (net (code "259") (name "Net-(IC14-TXN)") (class "Default")
      (node (ref "IC14") (pin "20") (pinfunction "TXN_20") (pintype "bidirectional"))
      (node (ref "R84") (pin "1") (pinfunction "1_1") (pintype "passive"))
      (node (ref "T1") (pin "2") (pinfunction "2_2") (pintype "bidirectional"))
    )
    (net (code "260") (name "Net-(IC14-TXP)") (class "Default")
      (node (ref "IC14") (pin "21") (pinfunction "TXP_21") (pintype "bidirectional"))
      (node (ref "R83") (pin "1") (pinfunction "1_1") (pintype "passive"))
      (node (ref "T1") (pin "1") (pinfunction "1_1") (pintype "bidirectional"))
    )
    (net (code "261") (name "Net-(IC14-VDDCR)") (class "Default")
      (node (ref "C97") (pin "2") (pinfunction "2_2") (pintype "passive"))
      (node (ref "C98") (pin "2") (pinfunction "2_2") (pintype "passive"))
      (node (ref "IC14") (pin "6") (pinfunction "VDDCR_6") (pintype "bidirectional"))
    )
    (net (code "262") (name "Net-(LED1-PadC)") (class "Default")
      (node (ref "LED1") (pin "C") (pinfunction "C_C") (pintype "passive"))
      (node (ref "R21") (pin "1") (pinfunction "1_1") (pintype "passive"))
    )
    (net (code "263") (name "Net-(LED2-PadC)") (class "Default")
      (node (ref "LED2") (pin "C") (pinfunction "C_C") (pintype "passive"))
      (node (ref "R22") (pin "1") (pinfunction "1_1") (pintype "passive"))
    )
    (net (code "264") (name "Net-(LED3-PadC)") (class "Default")
      (node (ref "LED3") (pin "C") (pinfunction "C_C") (pintype "passive"))
      (node (ref "R23") (pin "1") (pinfunction "1_1") (pintype "passive"))
    )
    (net (code "265") (name "Net-(LED4-PadC)") (class "Default")
      (node (ref "LED4") (pin "C") (pinfunction "C_C") (pintype "passive"))
      (node (ref "R39") (pin "1") (pinfunction "1_1") (pintype "passive"))
    )
    (net (code "266") (name "Net-(LED5-PadC)") (class "Default")
      (node (ref "LED5") (pin "C") (pinfunction "C_C") (pintype "passive"))
      (node (ref "R40") (pin "1") (pinfunction "1_1") (pintype "passive"))
    )
    (net (code "267") (name "Net-(LED6-PadC)") (class "Default")
      (node (ref "LED6") (pin "C") (pinfunction "C_C") (pintype "passive"))
      (node (ref "R41") (pin "1") (pinfunction "1_1") (pintype "passive"))
    )
    (net (code "268") (name "Net-(R15-Pad2)") (class "Default")
      (node (ref "R15") (pin "2") (pinfunction "2_2") (pintype "passive"))
      (node (ref "R17") (pin "2") (pinfunction "2_2") (pintype "passive"))
      (node (ref "R19") (pin "1") (pinfunction "1_1") (pintype "passive"))
    )
    (net (code "269") (name "Net-(R46-Pad2)") (class "Default")
      (node (ref "R46") (pin "2") (pinfunction "2_2") (pintype "passive"))
      (node (ref "X1") (pin "14") (pinfunction "14_14") (pintype "passive"))
    )
    (net (code "270") (name "Net-(R47-Pad2)") (class "Default")
      (node (ref "R47") (pin "2") (pinfunction "2_2") (pintype "passive"))
      (node (ref "X1") (pin "13") (pinfunction "13_13") (pintype "passive"))
    )
    (net (code "271") (name "Net-(T1C-K)") (class "Default")
      (node (ref "R88") (pin "2") (pinfunction "2_2") (pintype "passive"))
      (node (ref "T1") (pin "10") (pinfunction "K_10") (pintype "passive"))
    )
    (net (code "272") (name "Net-(T1D-K)") (class "Default")
      (node (ref "R87") (pin "2") (pinfunction "2_2") (pintype "passive"))
      (node (ref "T1") (pin "11") (pinfunction "K_11") (pintype "passive"))
    )
    (net (code "273") (name "Net-(U$2-+5V)") (class "Default")
      (node (ref "JP1") (pin "2") (pinfunction "2_2") (pintype "passive"))
      (node (ref "U$2") (pin "A1") (pinfunction "+5V_A1") (pintype "power_in"))
    )
    (net (code "274") (name "Net-(U$2-E0)") (class "Default")
      (node (ref "JP1") (pin "7") (pinfunction "7_7") (pintype "passive"))
      (node (ref "U$2") (pin "B4") (pinfunction "E0_B4") (pintype "bidirectional"))
    )
    (net (code "275") (name "Net-(U$2-E1)") (class "Default")
      (node (ref "JP1") (pin "9") (pinfunction "9_9") (pintype "passive"))
      (node (ref "U$2") (pin "B5") (pinfunction "E1_B5") (pintype "bidirectional"))
    )
    (net (code "276") (name "Net-(U$2-E2)") (class "Default")
      (node (ref "JP1") (pin "11") (pinfunction "11_11") (pintype "passive"))
      (node (ref "U$2") (pin "B6") (pinfunction "E2_B6") (pintype "bidirectional"))
    )
    (net (code "277") (name "Net-(U$2-E3)") (class "Default")
      (node (ref "JP1") (pin "13") (pinfunction "13_13") (pintype "passive"))
      (node (ref "U$2") (pin "B7") (pinfunction "E3_B7") (pintype "bidirectional"))
    )
    (net (code "278") (name "Net-(U$2-E4)") (class "Default")
      (node (ref "JP1") (pin "15") (pinfunction "15_15") (pintype "passive"))
      (node (ref "U$2") (pin "B8") (pinfunction "E4_B8") (pintype "bidirectional"))
    )
    (net (code "279") (name "Net-(U$2-E5)") (class "Default")
      (node (ref "JP1") (pin "17") (pinfunction "17_17") (pintype "passive"))
      (node (ref "U$2") (pin "B9") (pinfunction "E5_B9") (pintype "bidirectional"))
    )
    (net (code "280") (name "Net-(U$2-E6)") (class "Default")
      (node (ref "JP1") (pin "19") (pinfunction "19_19") (pintype "passive"))
      (node (ref "U$2") (pin "B10") (pinfunction "E6_B10") (pintype "bidirectional"))
    )
    (net (code "281") (name "Net-(U$2-E7)") (class "Default")
      (node (ref "JP1") (pin "20") (pinfunction "20_20") (pintype "passive"))
      (node (ref "U$2") (pin "A10") (pinfunction "E7_A10") (pintype "bidirectional"))
    )
    (net (code "282") (name "Net-(U$2-E8)") (class "Default")
      (node (ref "JP1") (pin "18") (pinfunction "18_18") (pintype "passive"))
      (node (ref "U$2") (pin "A9") (pinfunction "E8_A9") (pintype "bidirectional"))
    )
    (net (code "283") (name "Net-(U$2-E9)") (class "Default")
      (node (ref "JP1") (pin "16") (pinfunction "16_16") (pintype "passive"))
      (node (ref "U$2") (pin "A8") (pinfunction "E9_A8") (pintype "bidirectional"))
    )
    (net (code "284") (name "Net-(U$2-E10)") (class "Default")
      (node (ref "JP1") (pin "14") (pinfunction "14_14") (pintype "passive"))
      (node (ref "U$2") (pin "A7") (pinfunction "E10_A7") (pintype "bidirectional"))
    )
    (net (code "285") (name "Net-(U$2-E11)") (class "Default")
      (node (ref "JP1") (pin "12") (pinfunction "12_12") (pintype "passive"))
      (node (ref "U$2") (pin "A6") (pinfunction "E11_A6") (pintype "bidirectional"))
    )
    (net (code "286") (name "Net-(U$2-E12)") (class "Default")
      (node (ref "JP1") (pin "10") (pinfunction "10_10") (pintype "passive"))
      (node (ref "U$2") (pin "A5") (pinfunction "E12_A5") (pintype "bidirectional"))
    )
    (net (code "287") (name "Net-(U$4A-D)") (class "Default")
      (node (ref "R29") (pin "1") (pinfunction "1_1") (pintype "passive"))
      (node (ref "U$4") (pin "3") (pinfunction "D_3") (pintype "passive"))
    )
    (net (code "288") (name "Net-(U$4B-D)") (class "Default")
      (node (ref "R33") (pin "1") (pinfunction "1_1") (pintype "passive"))
      (node (ref "U$4") (pin "6") (pinfunction "D_6") (pintype "passive"))
    )
    (net (code "289") (name "Net-(U$15-Pad1)") (class "Default")
      (node (ref "U$15") (pin "1") (pinfunction "1_1") (pintype "passive"))
      (node (ref "U$16") (pin "1") (pinfunction "1_1") (pintype "passive"))
    )
    (net (code "290") (name "Net-(U$15-Pad2)") (class "Default")
      (node (ref "U$15") (pin "2") (pinfunction "2_2") (pintype "passive"))
      (node (ref "U$16") (pin "2") (pinfunction "2_2") (pintype "passive"))
    )
    (net (code "291") (name "Net-(U$15-Pad3)") (class "Default")
      (node (ref "U$15") (pin "3") (pinfunction "3_3") (pintype "passive"))
      (node (ref "U$16") (pin "3") (pinfunction "3_3") (pintype "passive"))
    )
    (net (code "292") (name "Net-(U$15-Pad4)") (class "Default")
      (node (ref "U$15") (pin "4") (pinfunction "4_4") (pintype "passive"))
      (node (ref "U$16") (pin "4") (pinfunction "4_4") (pintype "passive"))
    )
    (net (code "293") (name "Net-(U$15-Pad5)") (class "Default")
      (node (ref "U$15") (pin "5") (pinfunction "5_5") (pintype "passive"))
      (node (ref "U$16") (pin "5") (pinfunction "5_5") (pintype "passive"))
    )
    (net (code "294") (name "Net-(U$15-Pad6)") (class "Default")
      (node (ref "U$15") (pin "6") (pinfunction "6_6") (pintype "passive"))
      (node (ref "U$16") (pin "6") (pinfunction "6_6") (pintype "passive"))
    )
    (net (code "295") (name "Net-(U$15-Pad7)") (class "Default")
      (node (ref "U$15") (pin "7") (pinfunction "7_7") (pintype "passive"))
      (node (ref "U$16") (pin "7") (pinfunction "7_7") (pintype "passive"))
    )
    (net (code "296") (name "Net-(U$15-Pad8)") (class "Default")
      (node (ref "U$15") (pin "8") (pinfunction "8_8") (pintype "passive"))
      (node (ref "U$16") (pin "8") (pinfunction "8_8") (pintype "passive"))
    )
    (net (code "297") (name "Net-(U$15-Pad9)") (class "Default")
      (node (ref "U$15") (pin "9") (pinfunction "9_9") (pintype "passive"))
      (node (ref "U$16") (pin "9") (pinfunction "9_9") (pintype "passive"))
    )
    (net (code "298") (name "Net-(U$15-Pad10)") (class "Default")
      (node (ref "U$15") (pin "10") (pinfunction "10_10") (pintype "passive"))
      (node (ref "U$16") (pin "10") (pinfunction "10_10") (pintype "passive"))
    )
    (net (code "299") (name "PE") (class "Default")
      (node (ref "C50") (pin "1") (pinfunction "1_1") (pintype "passive"))
      (node (ref "R45") (pin "1") (pinfunction "1_1") (pintype "passive"))
      (node (ref "T1") (pin "8") (pinfunction "8_8") (pintype "bidirectional"))
      (node (ref "T1") (pin "Z1") (pinfunction "SHIELD_Z1") (pintype "passive"))
      (node (ref "T1") (pin "Z2") (pinfunction "SHIELD_Z2") (pintype "passive"))
      (node (ref "USB2") (pin "P$5") (pinfunction "SHIELD_P$5") (pintype "passive"))
      (node (ref "USB2") (pin "P$6") (pinfunction "SHIELD_P$6") (pintype "passive"))
    )
    (net (code "300") (name "unconnected-(CONN1-BUSACK-PadA26)") (class "Default")
      (node (ref "CONN1") (pin "A26") (pinfunction "BUSACK_A26") (pintype "bidirectional"))
    )
    (net (code "301") (name "unconnected-(CONN1-BUSREQ-PadA19)") (class "Default")
      (node (ref "CONN1") (pin "A19") (pinfunction "BUSREQ_A19") (pintype "bidirectional"))
    )
    (net (code "302") (name "unconnected-(CONN1-HALT-PadB15)") (class "Default")
      (node (ref "CONN1") (pin "B15") (pinfunction "HALT_B15") (pintype "bidirectional"))
    )
    (net (code "303") (name "unconnected-(CONN1-NC-PadB28)") (class "Default")
      (node (ref "CONN1") (pin "B28") (pinfunction "NC_B28") (pintype "bidirectional"))
    )
    (net (code "304") (name "unconnected-(CONN1-U-PadA18)") (class "Default")
      (node (ref "CONN1") (pin "A18") (pinfunction "U_A18") (pintype "bidirectional"))
    )
    (net (code "305") (name "unconnected-(CONN1-V-PadA17)") (class "Default")
      (node (ref "CONN1") (pin "A17") (pinfunction "V_A17") (pintype "bidirectional"))
    )
    (net (code "306") (name "unconnected-(CONN1-VIDEO-PadA15)") (class "Default")
      (node (ref "CONN1") (pin "A15") (pinfunction "VIDEO_A15") (pintype "bidirectional"))
    )
    (net (code "307") (name "unconnected-(CONN1-WAIT-PadB21)") (class "Default")
      (node (ref "CONN1") (pin "B21") (pinfunction "WAIT_B21") (pintype "bidirectional"))
    )
    (net (code "308") (name "unconnected-(CONN1-YL-PadA16)") (class "Default")
      (node (ref "CONN1") (pin "A16") (pinfunction "YL_A16") (pintype "bidirectional"))
    )
    (net (code "309") (name "unconnected-(IC2-__CLK3-Pad25)") (class "Default")
      (node (ref "IC2") (pin "25") (pinfunction "__CLK3_25") (pintype "input"))
    )
    (net (code "310") (name "unconnected-(IC2-__CLK4-Pad91)") (class "Default")
      (node (ref "IC2") (pin "91") (pinfunction "__CLK4_91") (pintype "input"))
    )
    (net (code "311") (name "unconnected-(IC2-__CLK5-Pad90)") (class "Default")
      (node (ref "IC2") (pin "90") (pinfunction "__CLK5_90") (pintype "input"))
    )
    (net (code "312") (name "unconnected-(IC2-__CLK6-Pad89)") (class "Default")
      (node (ref "IC2") (pin "89") (pinfunction "__CLK6_89") (pintype "input"))
    )
    (net (code "313") (name "unconnected-(IC2-__CLK7-Pad88)") (class "Default")
      (node (ref "IC2") (pin "88") (pinfunction "__CLK7_88") (pintype "input"))
    )
    (net (code "314") (name "unconnected-(IC14-XTAL2-Pad4)") (class "Default")
      (node (ref "IC14") (pin "4") (pinfunction "XTAL2_4") (pintype "bidirectional"))
    )
    (net (code "315") (name "unconnected-(J1-Pad6)") (class "Default")
      (node (ref "J1") (pin "6") (pinfunction "6_6") (pintype "passive"))
    )
    (net (code "316") (name "unconnected-(J1-Pad7)") (class "Default")
      (node (ref "J1") (pin "7") (pinfunction "7_7") (pintype "passive"))
    )
    (net (code "317") (name "unconnected-(J1-Pad8)") (class "Default")
      (node (ref "J1") (pin "8") (pinfunction "8_8") (pintype "passive"))
    )
    (net (code "318") (name "unconnected-(JP1-Pad5)") (class "Default")
      (node (ref "JP1") (pin "5") (pinfunction "5_5") (pintype "passive"))
    )
    (net (code "319") (name "unconnected-(JP1-Pad6)") (class "Default")
      (node (ref "JP1") (pin "6") (pinfunction "6_6") (pintype "passive"))
    )
    (net (code "320") (name "unconnected-(U$6-PA3-Pad6)") (class "Default")
      (node (ref "U$6") (pin "6") (pinfunction "PA3_6") (pintype "passive"))
    )
    (net (code "321") (name "unconnected-(U$6-PA4-Pad1)") (class "Default")
      (node (ref "U$6") (pin "1") (pinfunction "PA4_1") (pintype "passive"))
    )
    (net (code "322") (name "unconnected-(U$6-PA5-Pad4)") (class "Default")
      (node (ref "U$6") (pin "4") (pinfunction "PA5_4") (pintype "passive"))
    )
    (net (code "323") (name "unconnected-(U$8-+5V-PadA1)") (class "Default")
      (node (ref "U$8") (pin "A1") (pinfunction "+5V_A1") (pintype "power_in"))
    )
    (net (code "324") (name "unconnected-(U$9-RSH-Pad11)") (class "Default")
      (node (ref "U$9") (pin "11") (pinfunction "RSH_11") (pintype "bidirectional"))
    )
    (net (code "325") (name "unconnected-(U$9-TSH-Pad10)") (class "Default")
      (node (ref "U$9") (pin "10") (pinfunction "TSH_10") (pintype "bidirectional"))
    )
    (net (code "326") (name "unconnected-(U$10-E12-PadA5)") (class "Default")
      (node (ref "U$10") (pin "A5") (pinfunction "E12_A5") (pintype "bidirectional"))
    )
    (net (code "327") (name "unconnected-(U$11-PA3-Pad6)") (class "Default")
      (node (ref "U$11") (pin "6") (pinfunction "PA3_6") (pintype "passive"))
    )
    (net (code "328") (name "unconnected-(U$11-PA4-Pad1)") (class "Default")
      (node (ref "U$11") (pin "1") (pinfunction "PA4_1") (pintype "passive"))
    )
    (net (code "329") (name "unconnected-(U$11-PA5-Pad4)") (class "Default")
      (node (ref "U$11") (pin "4") (pinfunction "PA5_4") (pintype "passive"))
    )
    (net (code "330") (name "unconnected-(U1-CLK-Pad20)") (class "Default")
      (node (ref "U1") (pin "20") (pinfunction "CLK_20") (pintype "bidirectional"))
    )
    (net (code "331") (name "unconnected-(U1-CMD-Pad19)") (class "Default")
      (node (ref "U1") (pin "19") (pinfunction "CMD_19") (pintype "bidirectional"))
    )
    (net (code "332") (name "unconnected-(U1-NC-Pad32)") (class "Default")
      (node (ref "U1") (pin "32") (pinfunction "NC_32") (pintype "bidirectional"))
    )
    (net (code "333") (name "unconnected-(U1-SD1-Pad22)") (class "Default")
      (node (ref "U1") (pin "22") (pinfunction "SD1_22") (pintype "bidirectional"))
    )
    (net (code "334") (name "unconnected-(U1-SD2-Pad17)") (class "Default")
      (node (ref "U1") (pin "17") (pinfunction "SD2_17") (pintype "bidirectional"))
    )
    (net (code "335") (name "unconnected-(U1-SD3-Pad18)") (class "Default")
      (node (ref "U1") (pin "18") (pinfunction "SD3_18") (pintype "bidirectional"))
    )
    (net (code "336") (name "unconnected-(U1-SDO-Pad21)") (class "Default")
      (node (ref "U1") (pin "21") (pinfunction "SDO_21") (pintype "bidirectional"))
    )
    (net (code "337") (name "unconnected-(U1-SENSOR_VN-Pad5)") (class "Default")
      (node (ref "U1") (pin "5") (pinfunction "SENSOR_VN_5") (pintype "input"))
    )
    (net (code "338") (name "unconnected-(U1-SENSOR_VP-Pad4)") (class "Default")
      (node (ref "U1") (pin "4") (pinfunction "SENSOR_VP_4") (pintype "input"))
    )
    (net (code "339") (name "unconnected-(USB1B-USBID-PadP4)") (class "Default")
      (node (ref "USB1") (pin "P4") (pinfunction "USBID_P4") (pintype "bidirectional"))
    )
    (net (code "340") (name "unconnected-(USB1B-VUSB-PadP1)") (class "Default")
      (node (ref "USB1") (pin "P1") (pinfunction "VUSB_P1") (pintype "bidirectional"))
    )
    (net (code "341") (name "unconnected-(X1-Pad4)") (class "Default")
      (node (ref "X1") (pin "4") (pinfunction "4_4") (pintype "passive"))
    )
    (net (code "342") (name "unconnected-(X1-Pad9)") (class "Default")
      (node (ref "X1") (pin "9") (pinfunction "9_9") (pintype "passive"))
    )
    (net (code "343") (name "unconnected-(X1-Pad11)") (class "Default")
      (node (ref "X1") (pin "11") (pinfunction "11_11") (pintype "passive"))
    )
    (net (code "344") (name "unconnected-(X1-Pad12)") (class "Default")
      (node (ref "X1") (pin "12") (pinfunction "12_12") (pintype "passive"))
    )
    (net (code "345") (name "unconnected-(X1-Pad15)") (class "Default")
      (node (ref "X1") (pin "15") (pinfunction "15_15") (pintype "passive"))
    )
  )
)
